# foxBMS_BMS-Extension.net
KiCad netlist of a schematic drawn in EAGLE
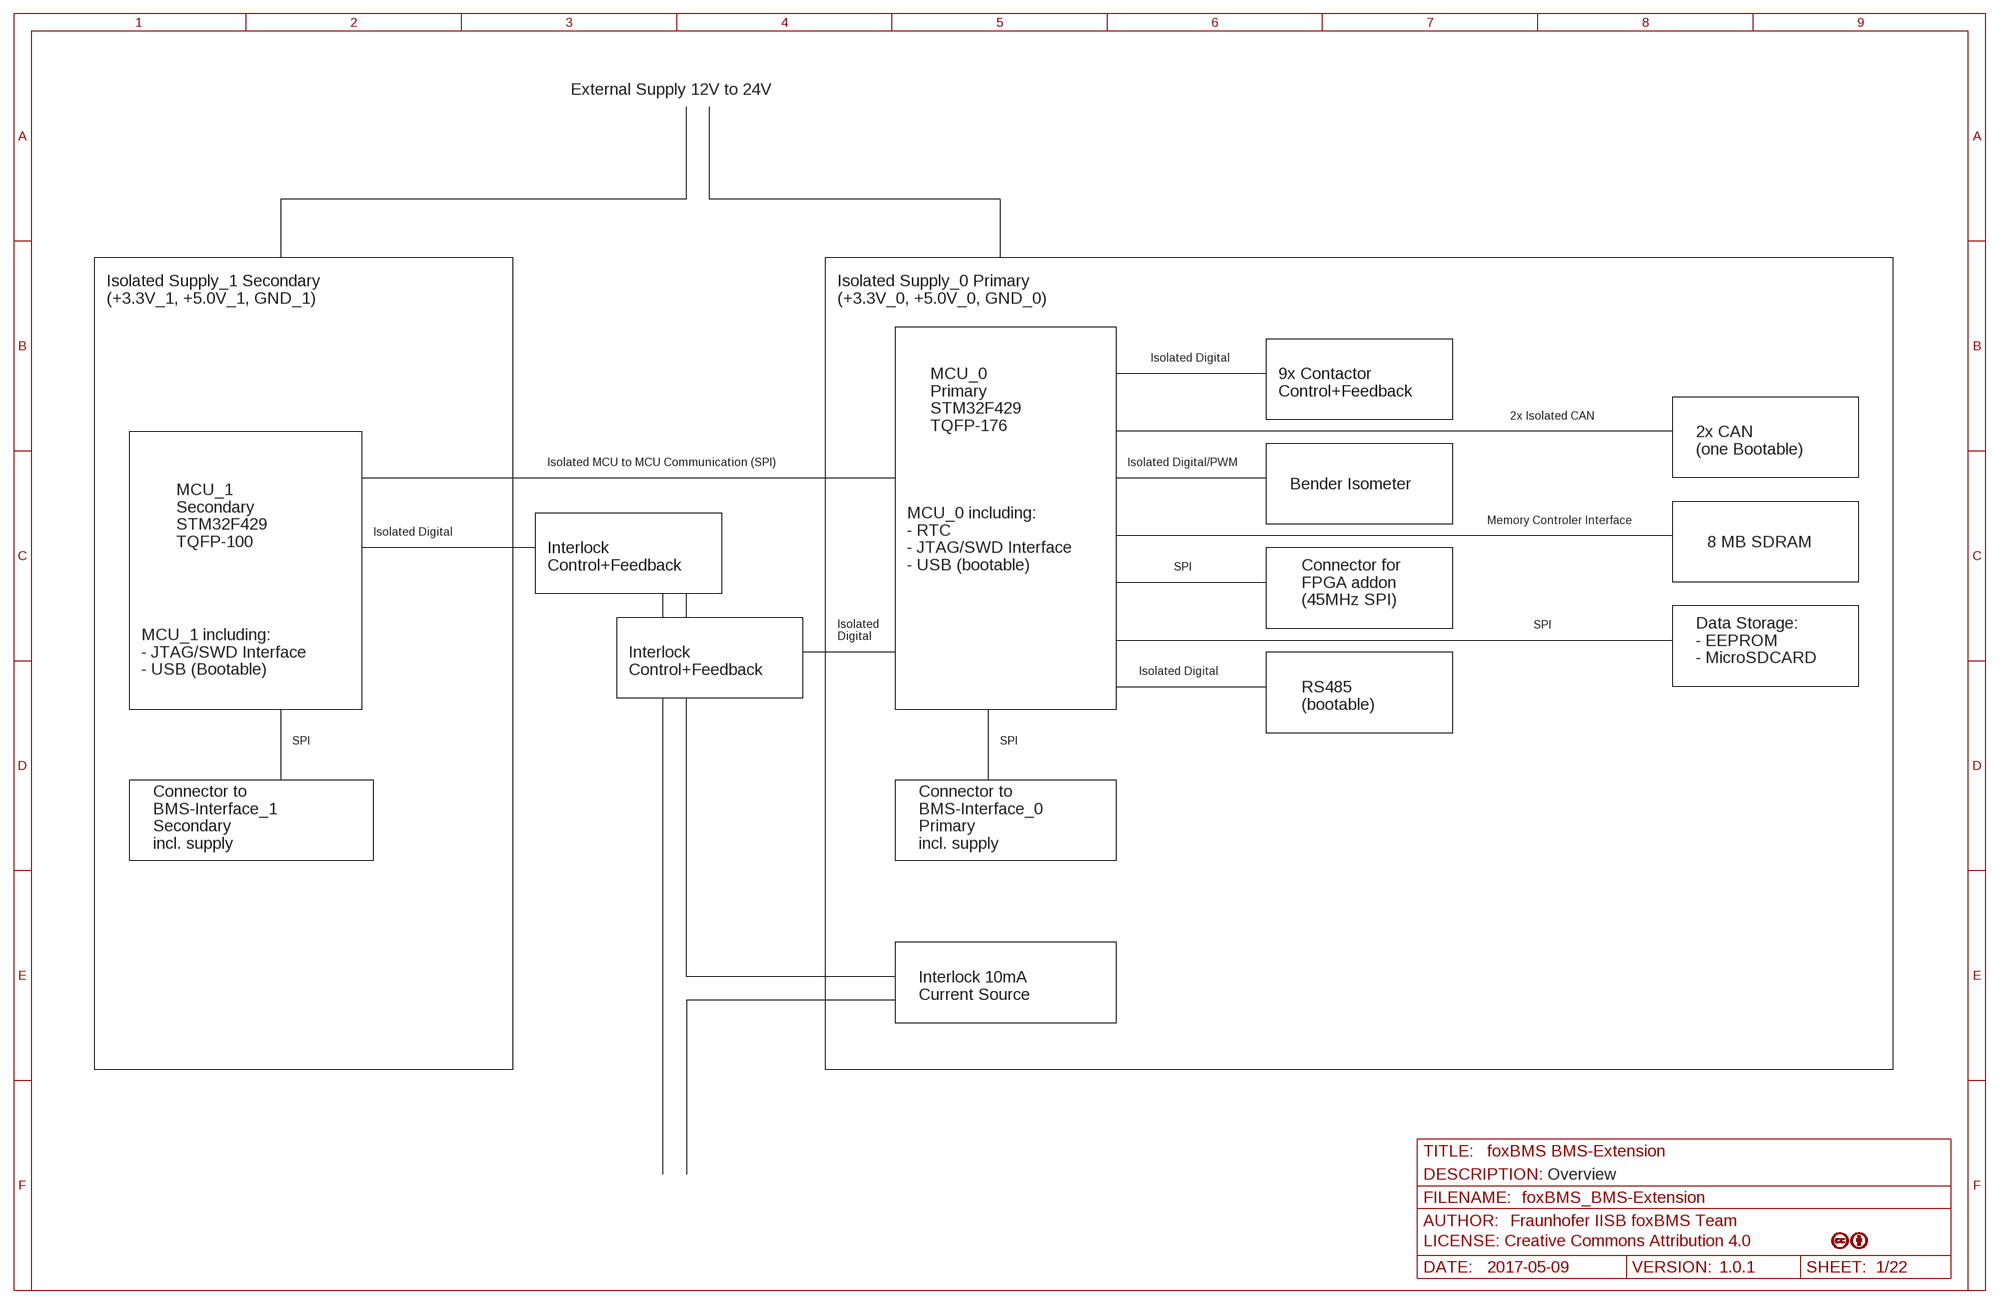
[diagram p0: schematic, sheet 1]
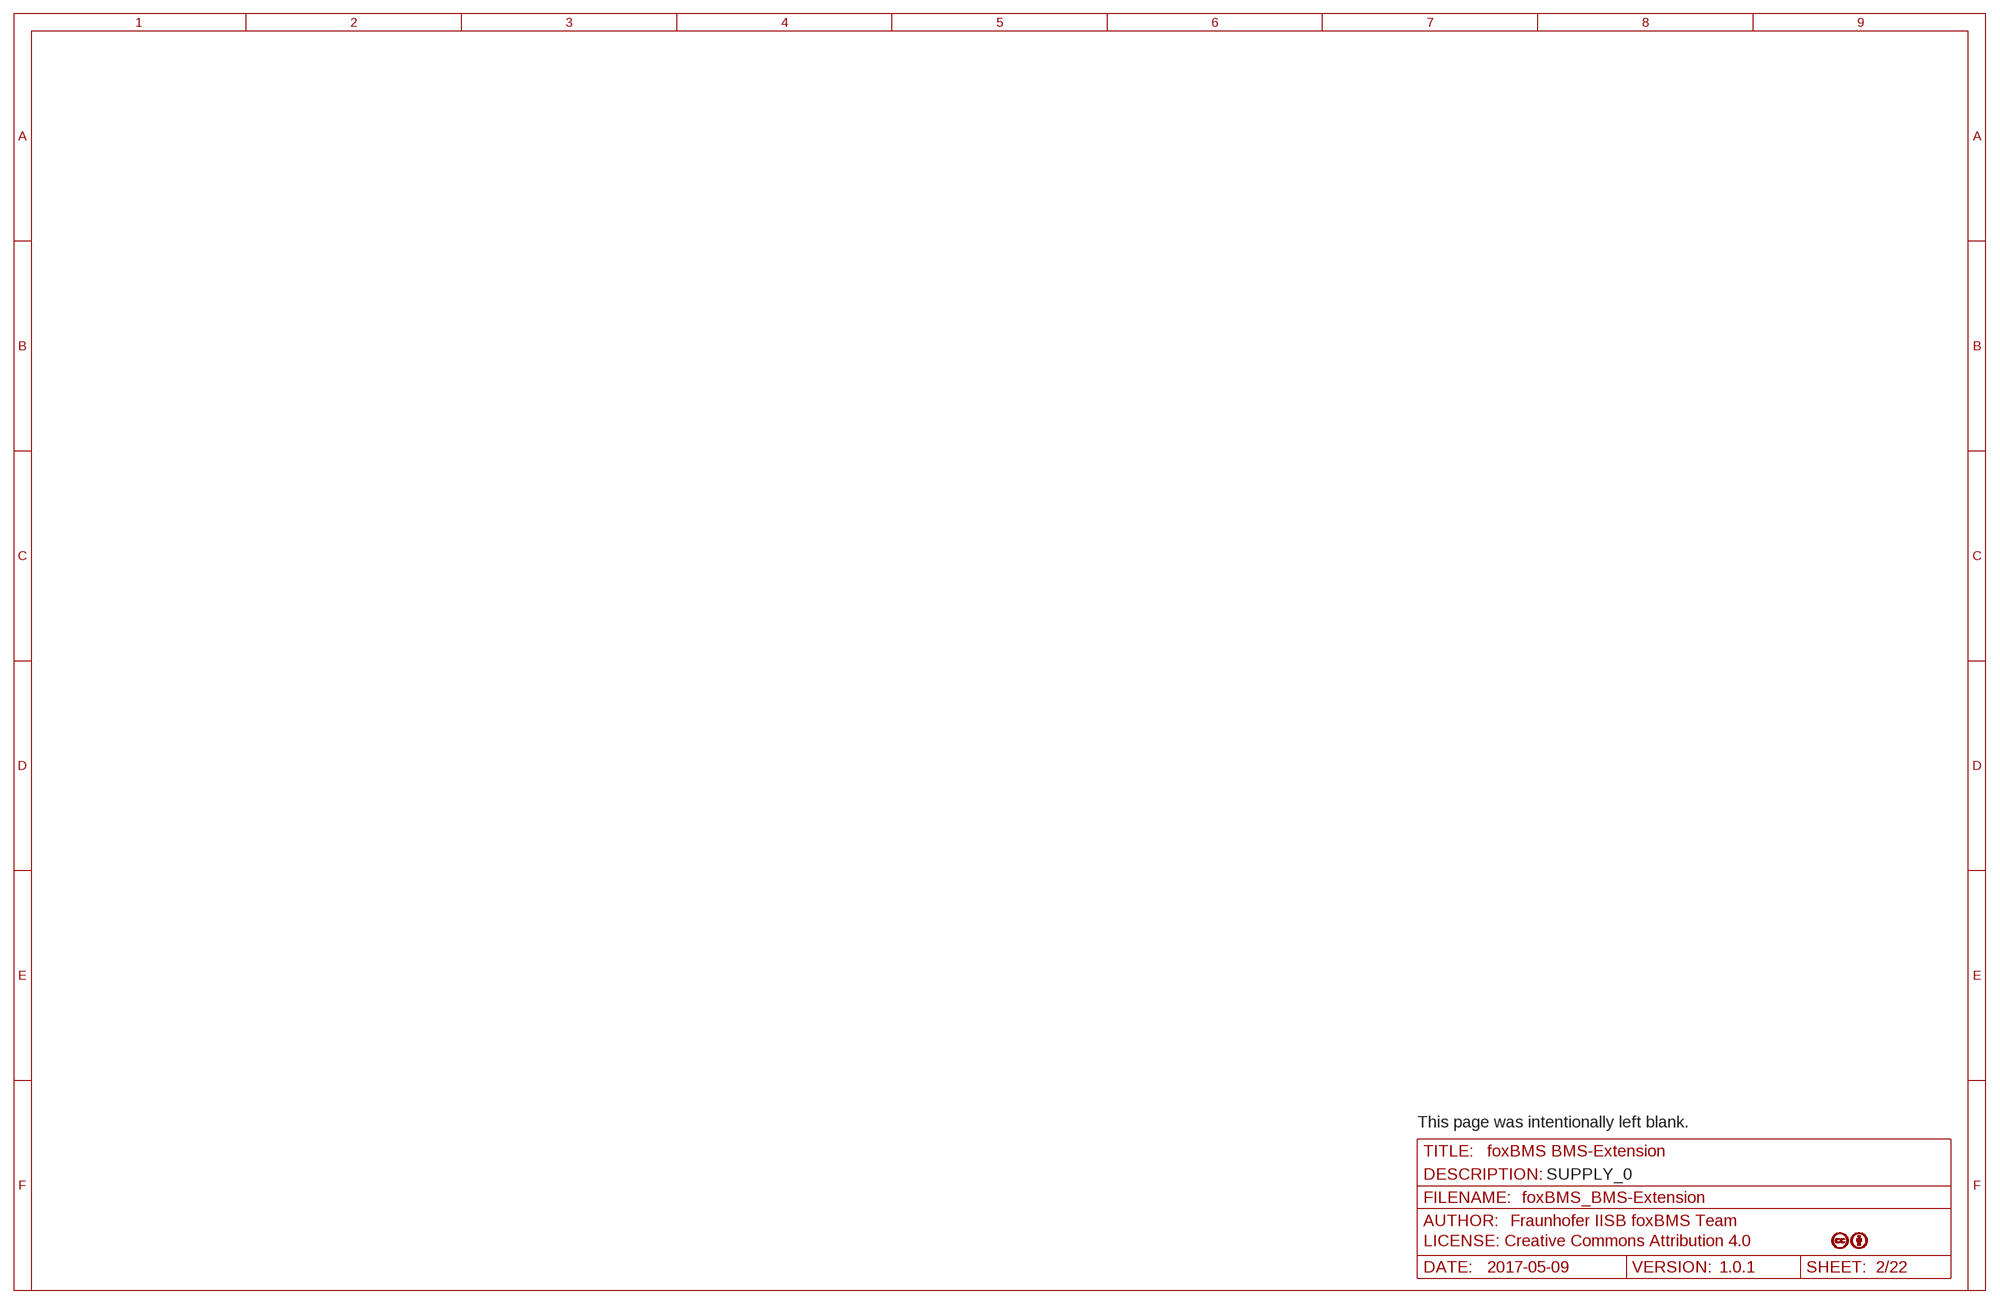
[diagram p1: schematic, sheet 2]
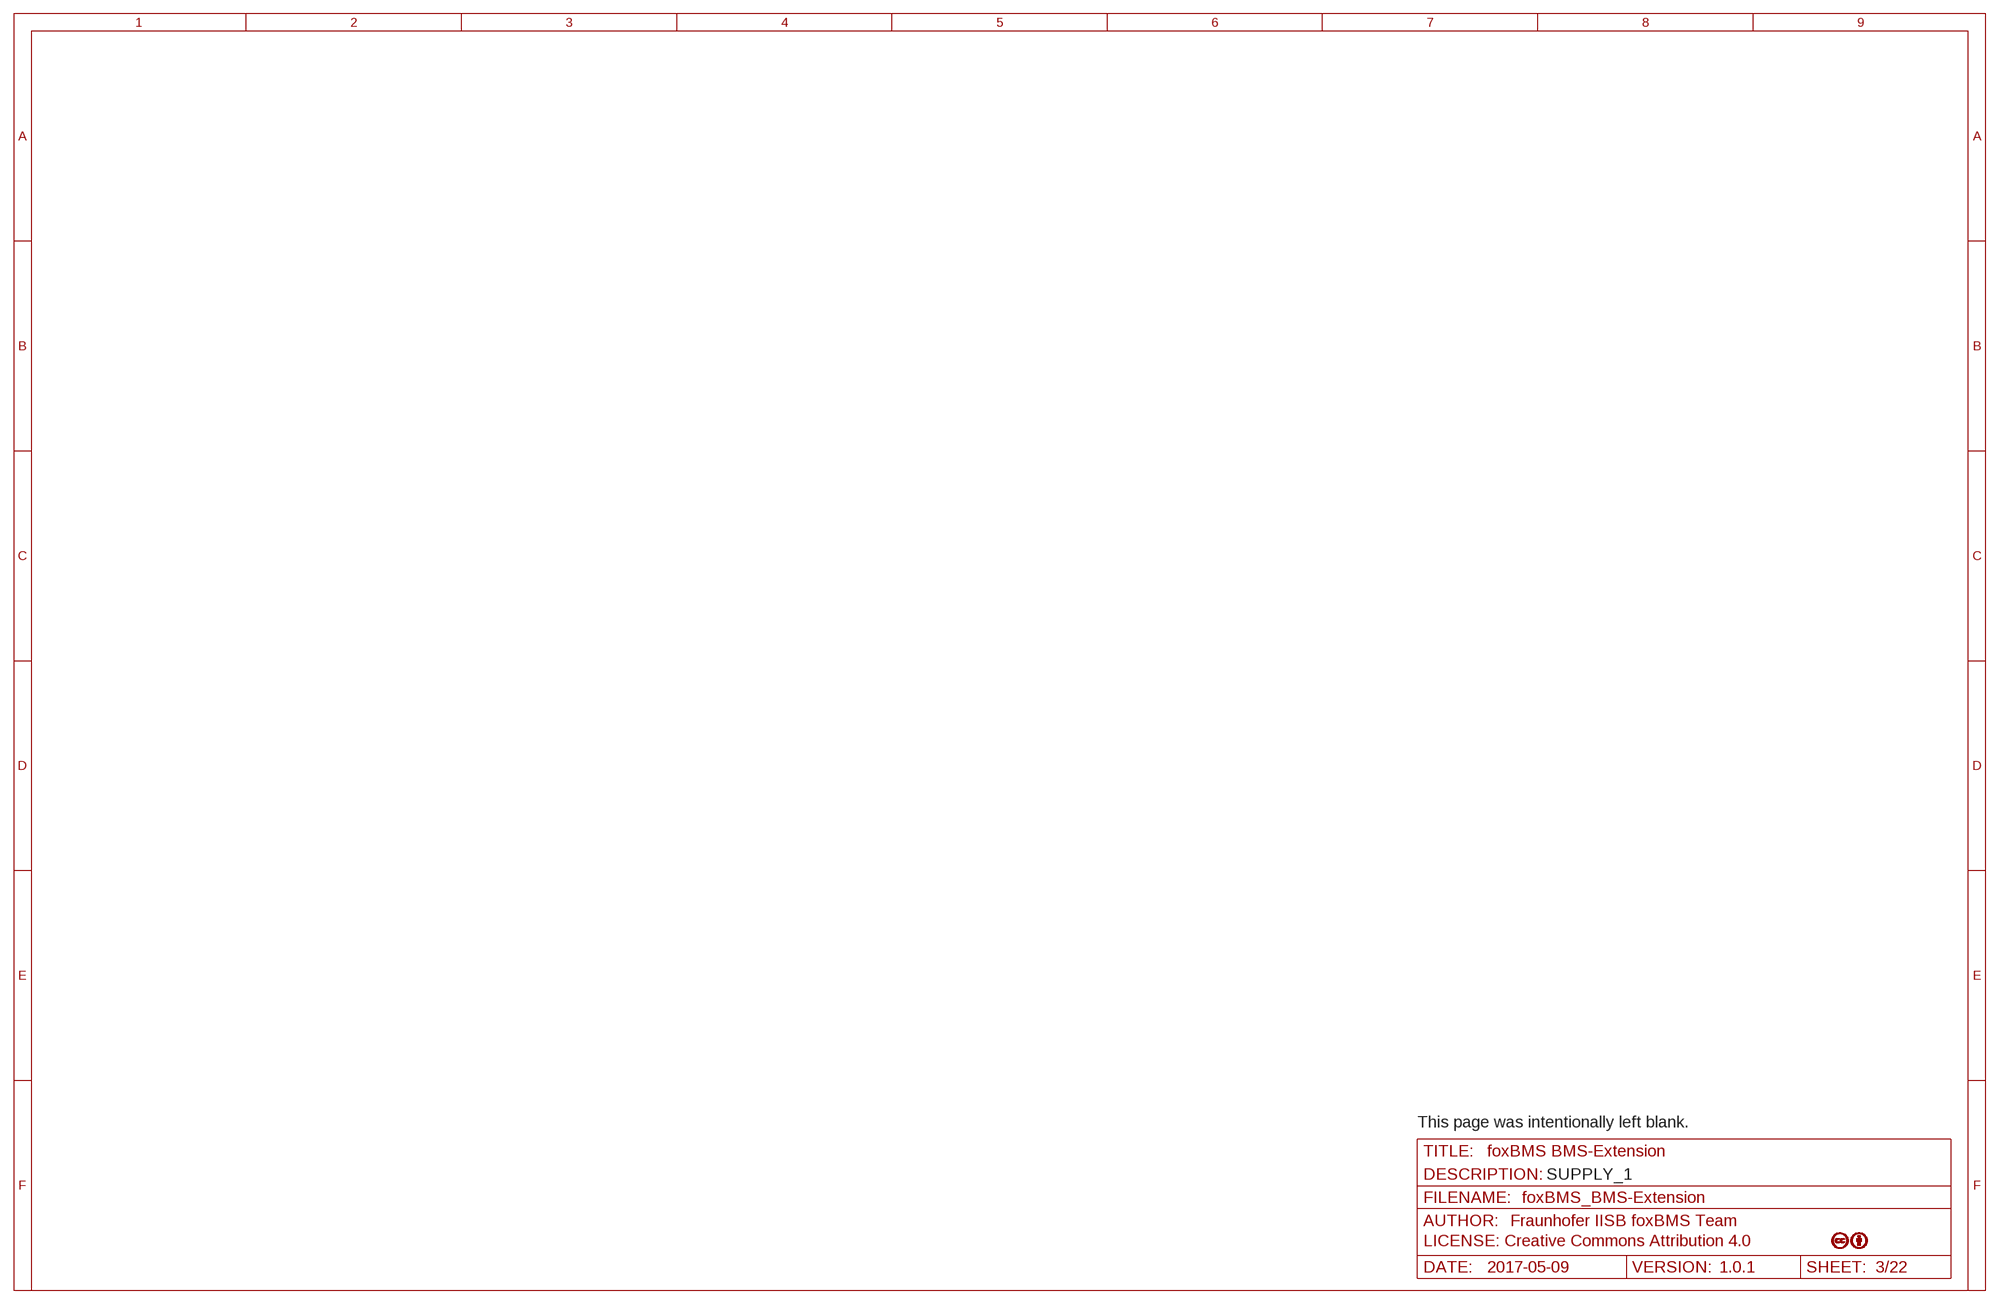
[diagram p2: schematic, sheet 3]
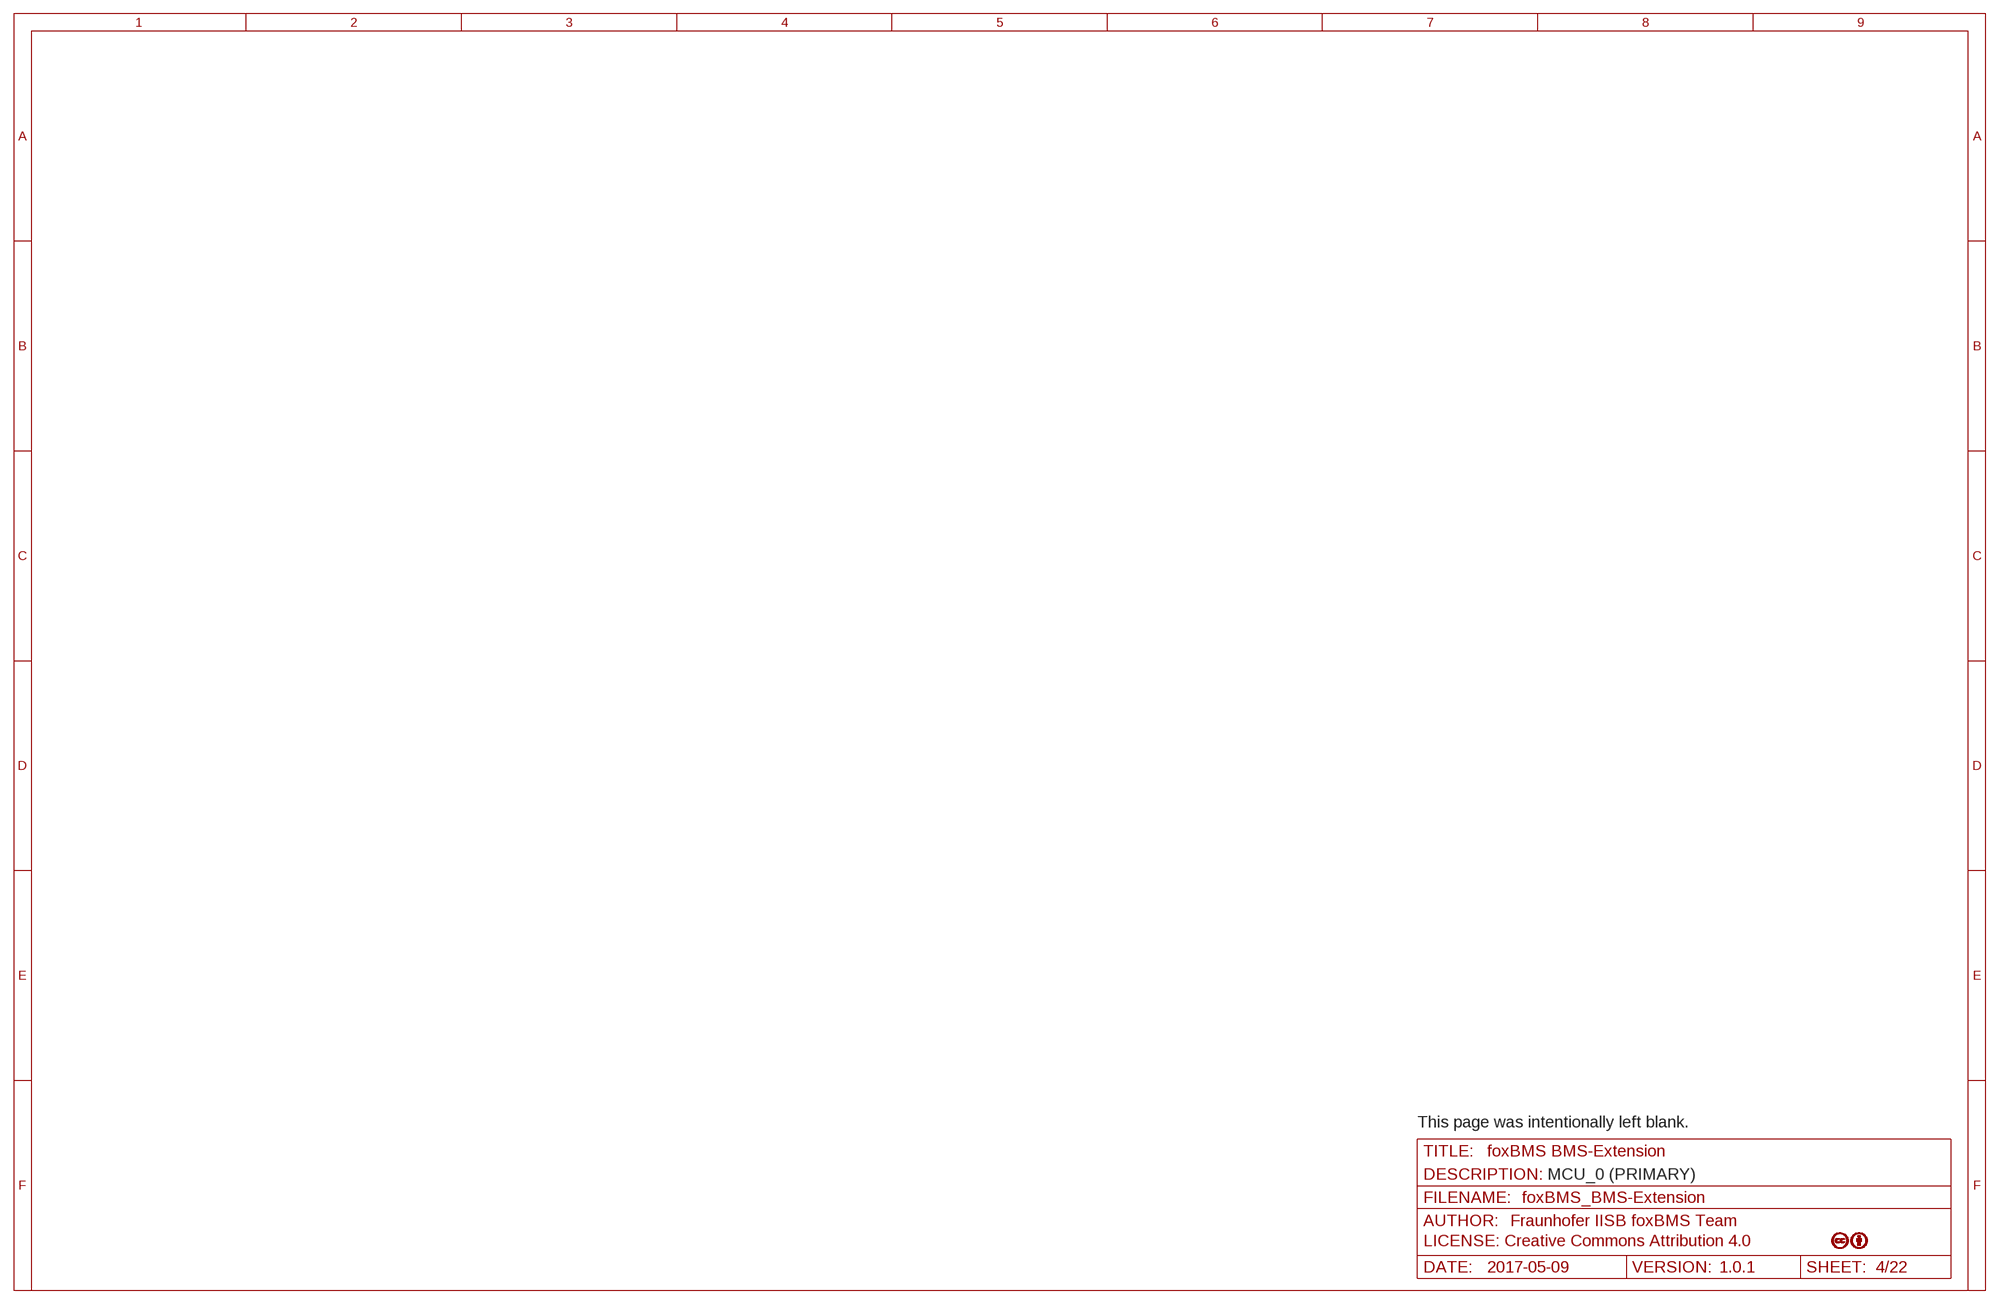
[diagram p3: schematic, sheet 4]
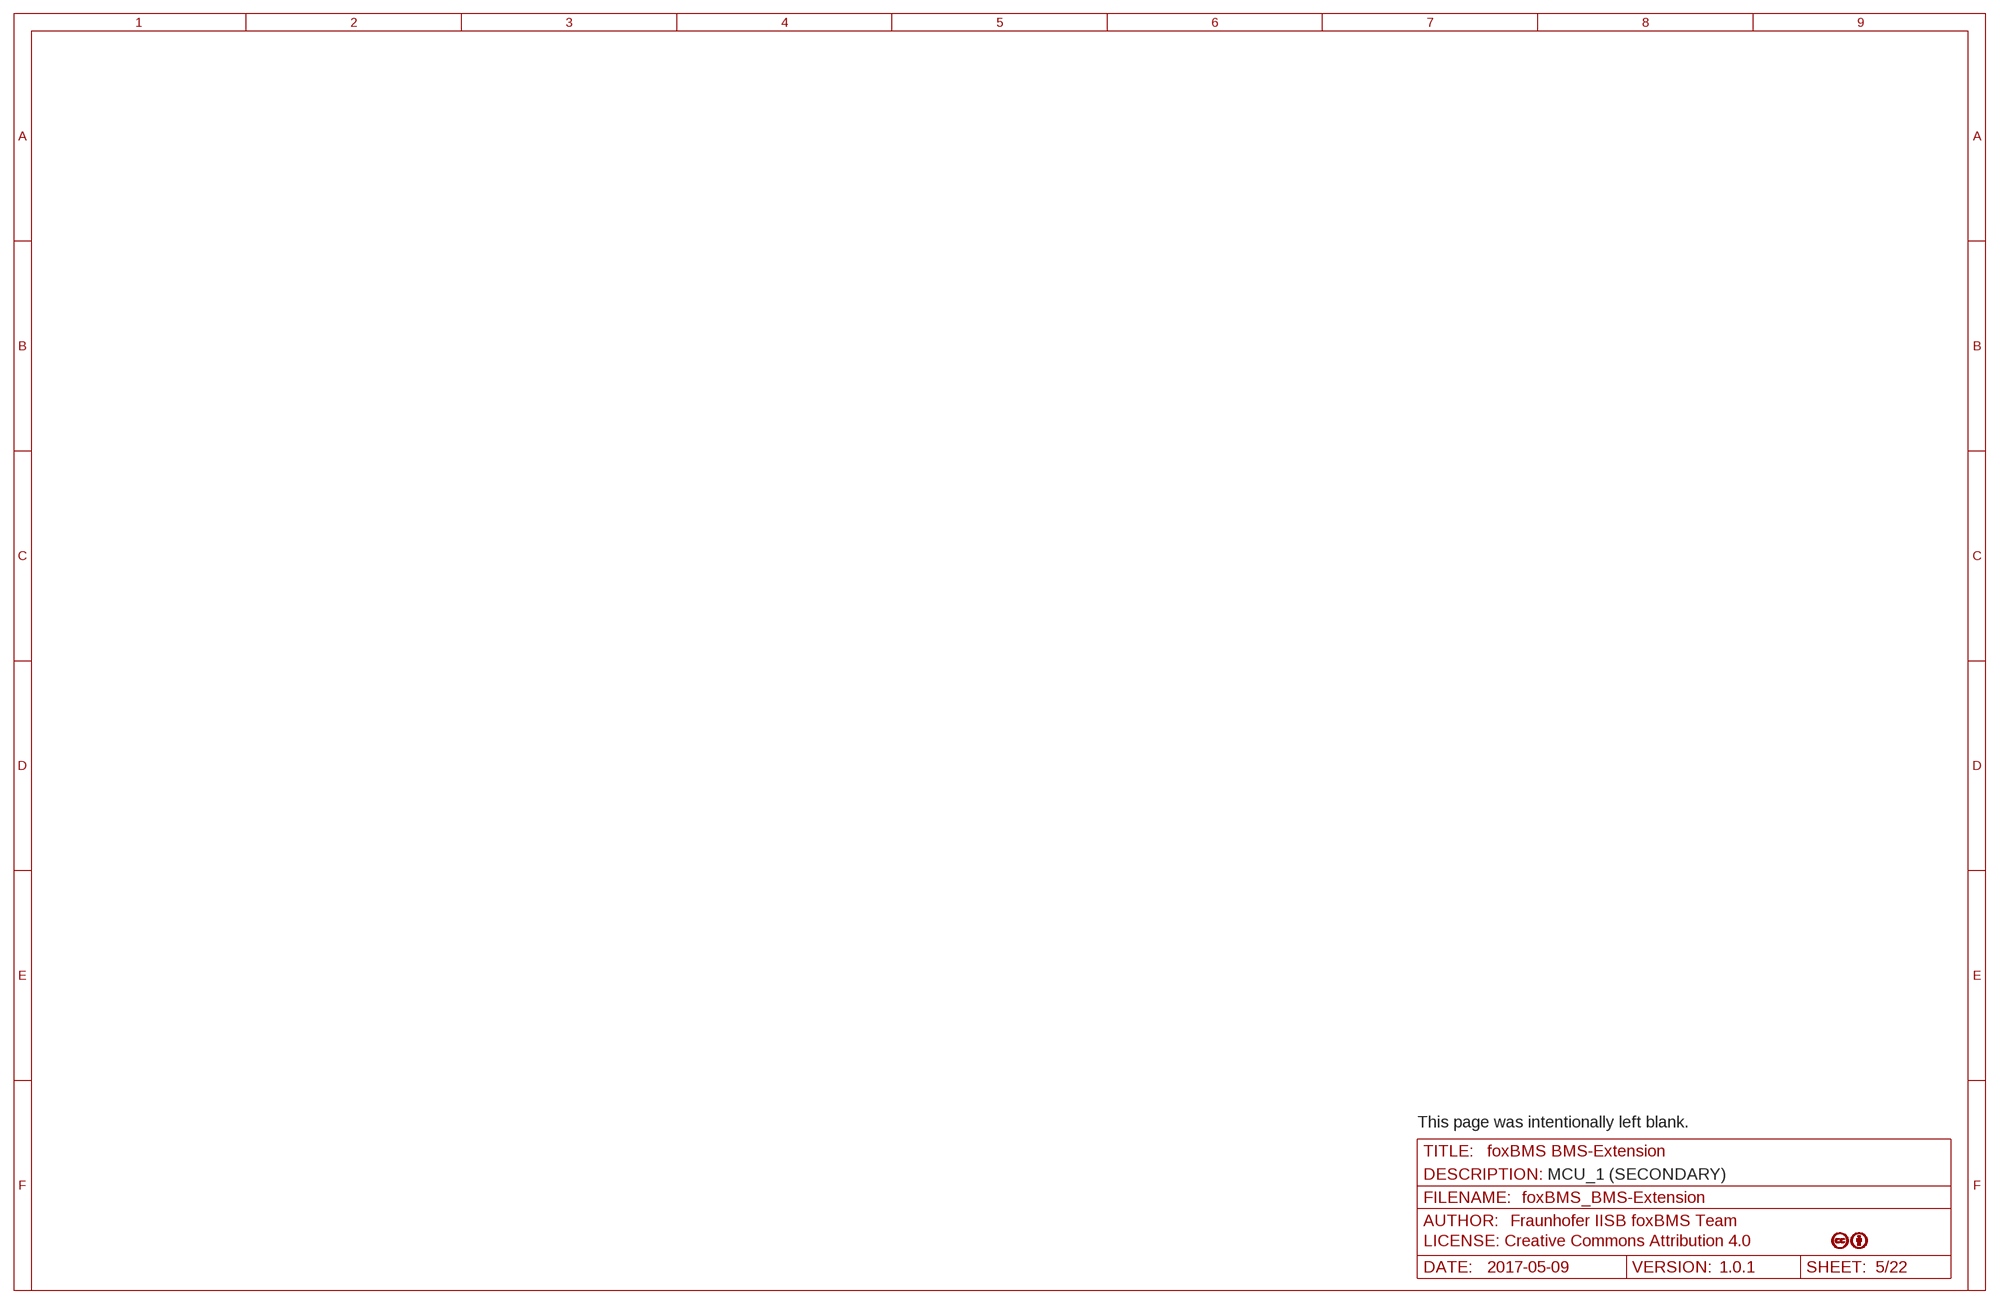
[diagram p4: schematic, sheet 5]
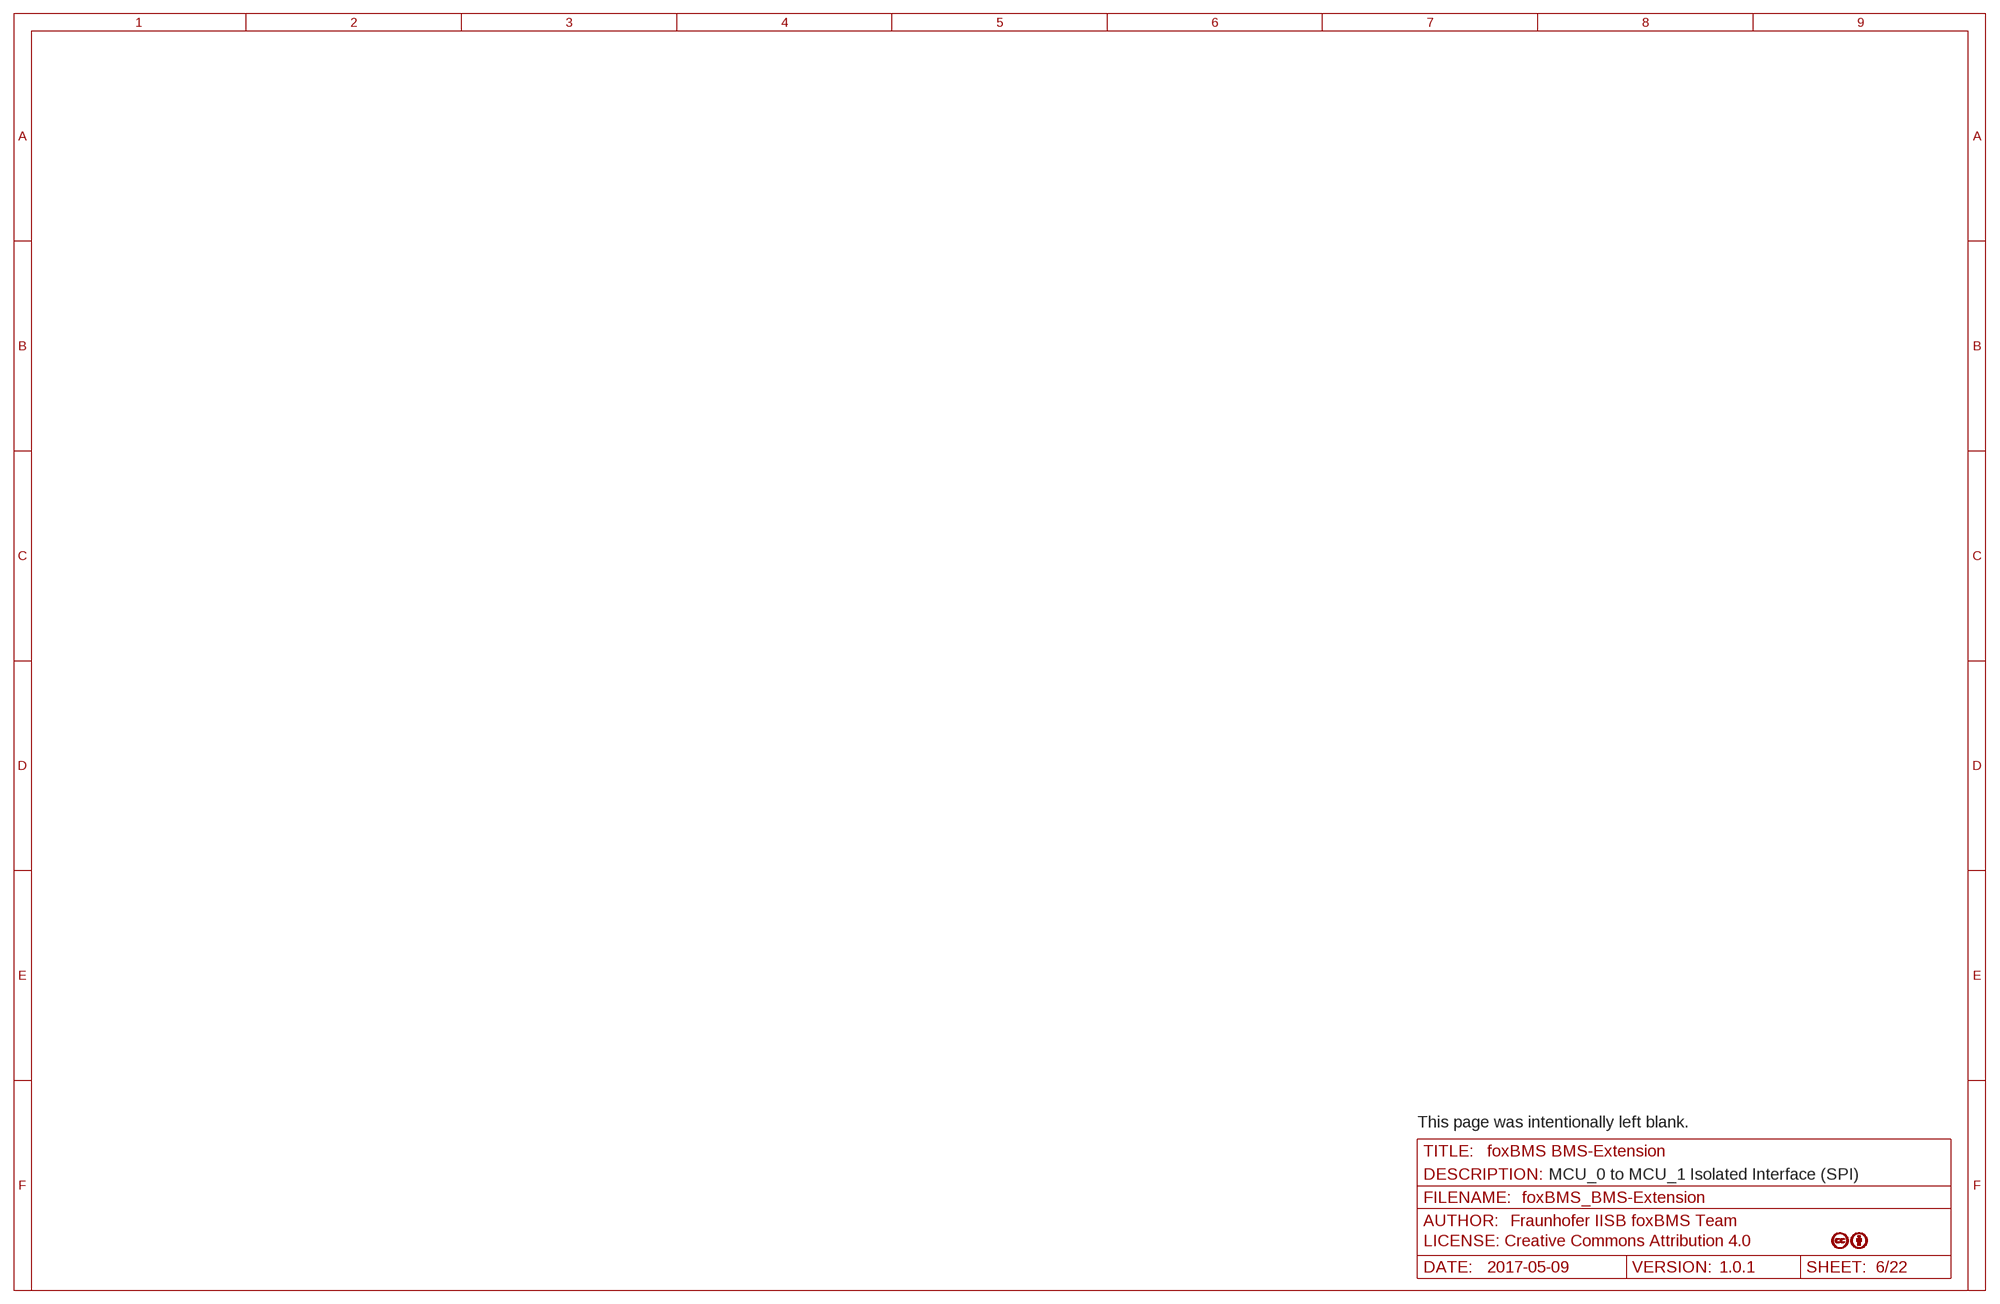
[diagram p5: schematic, sheet 6]
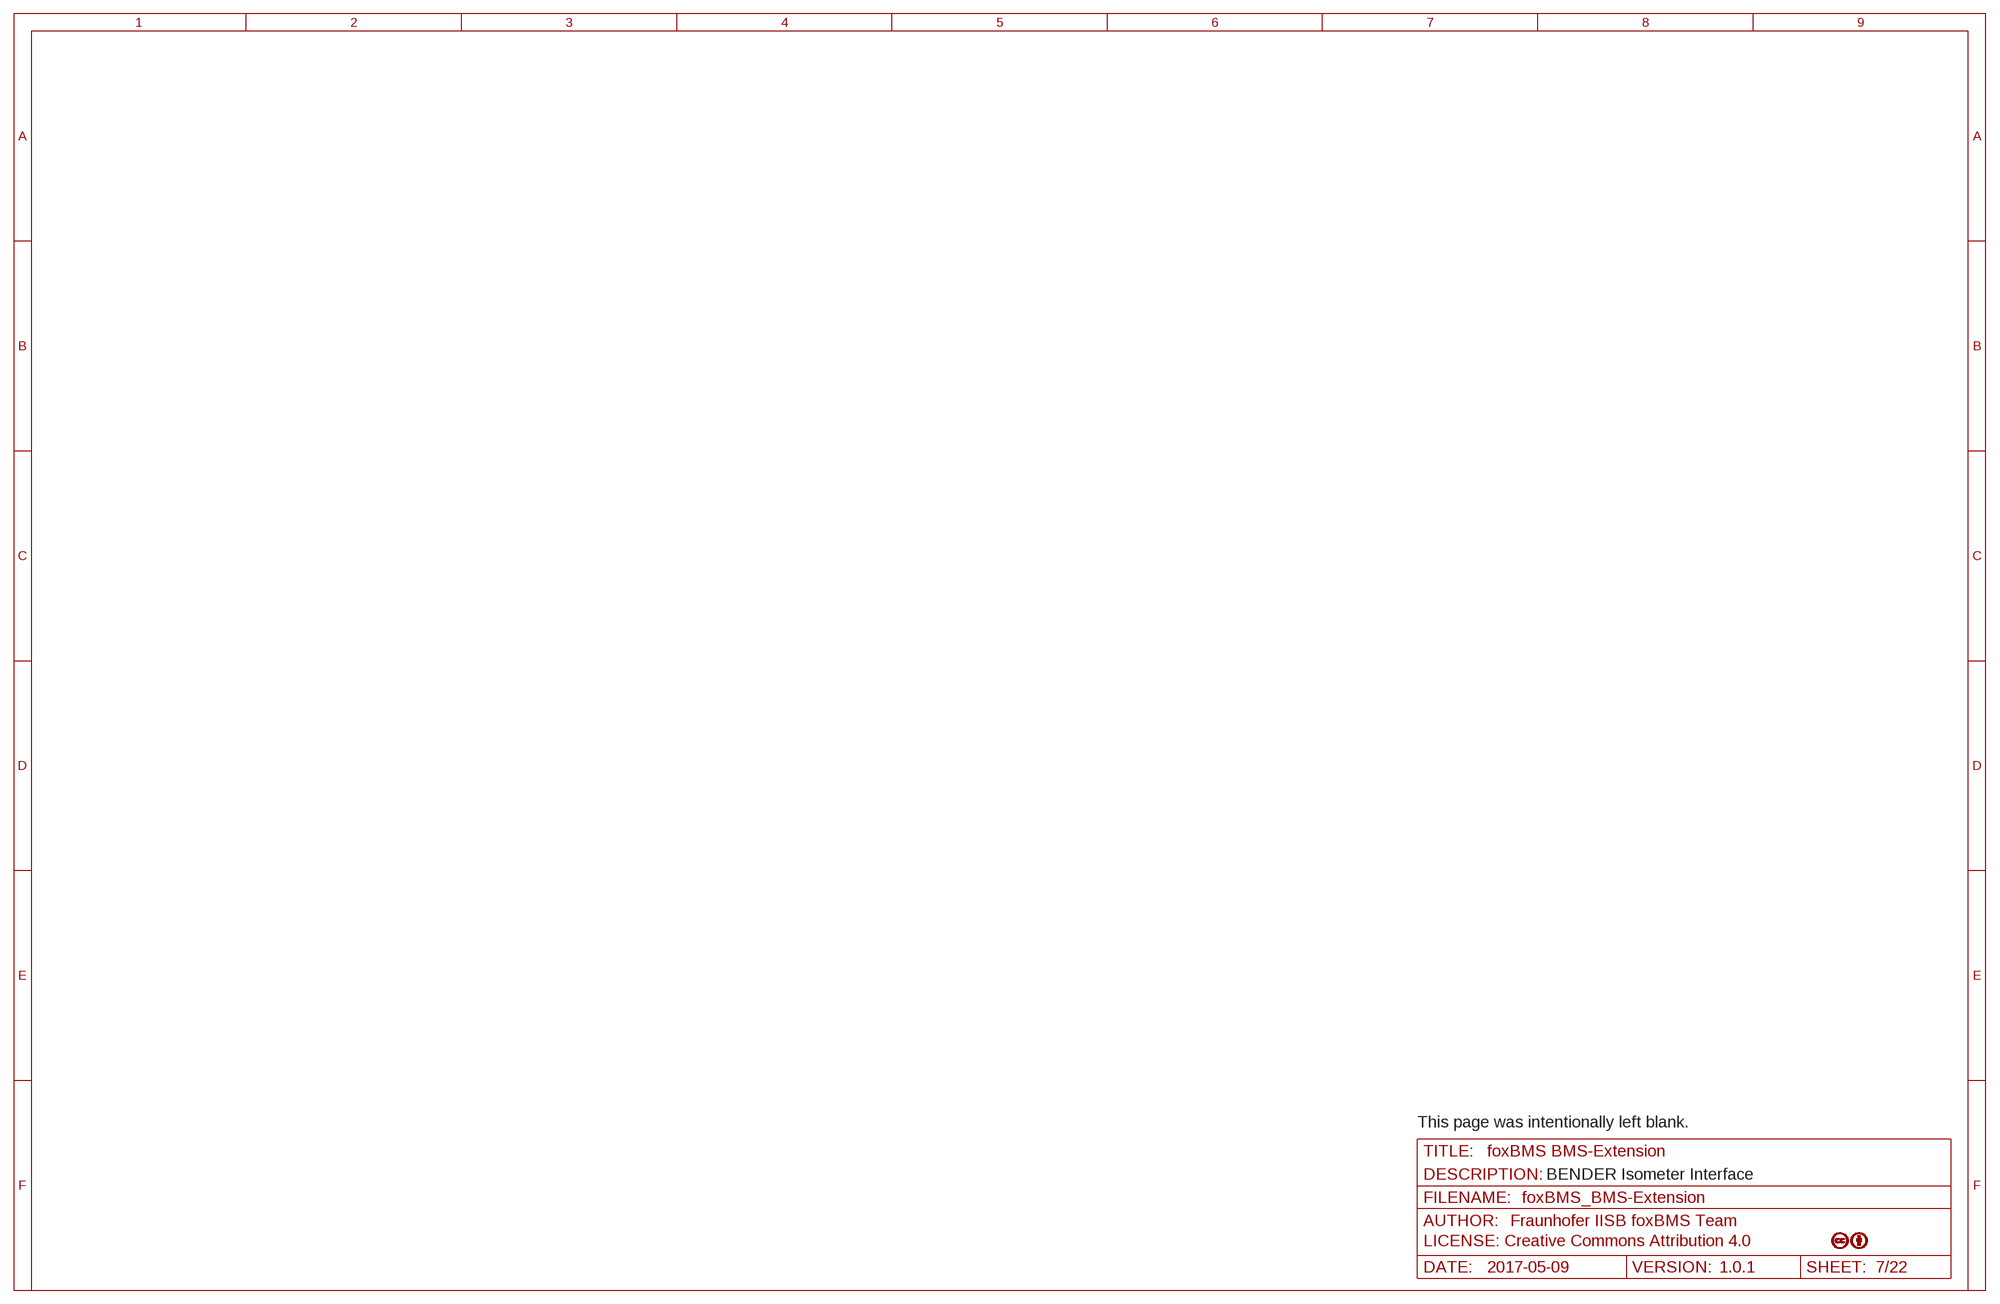
[diagram p6: schematic, sheet 7]
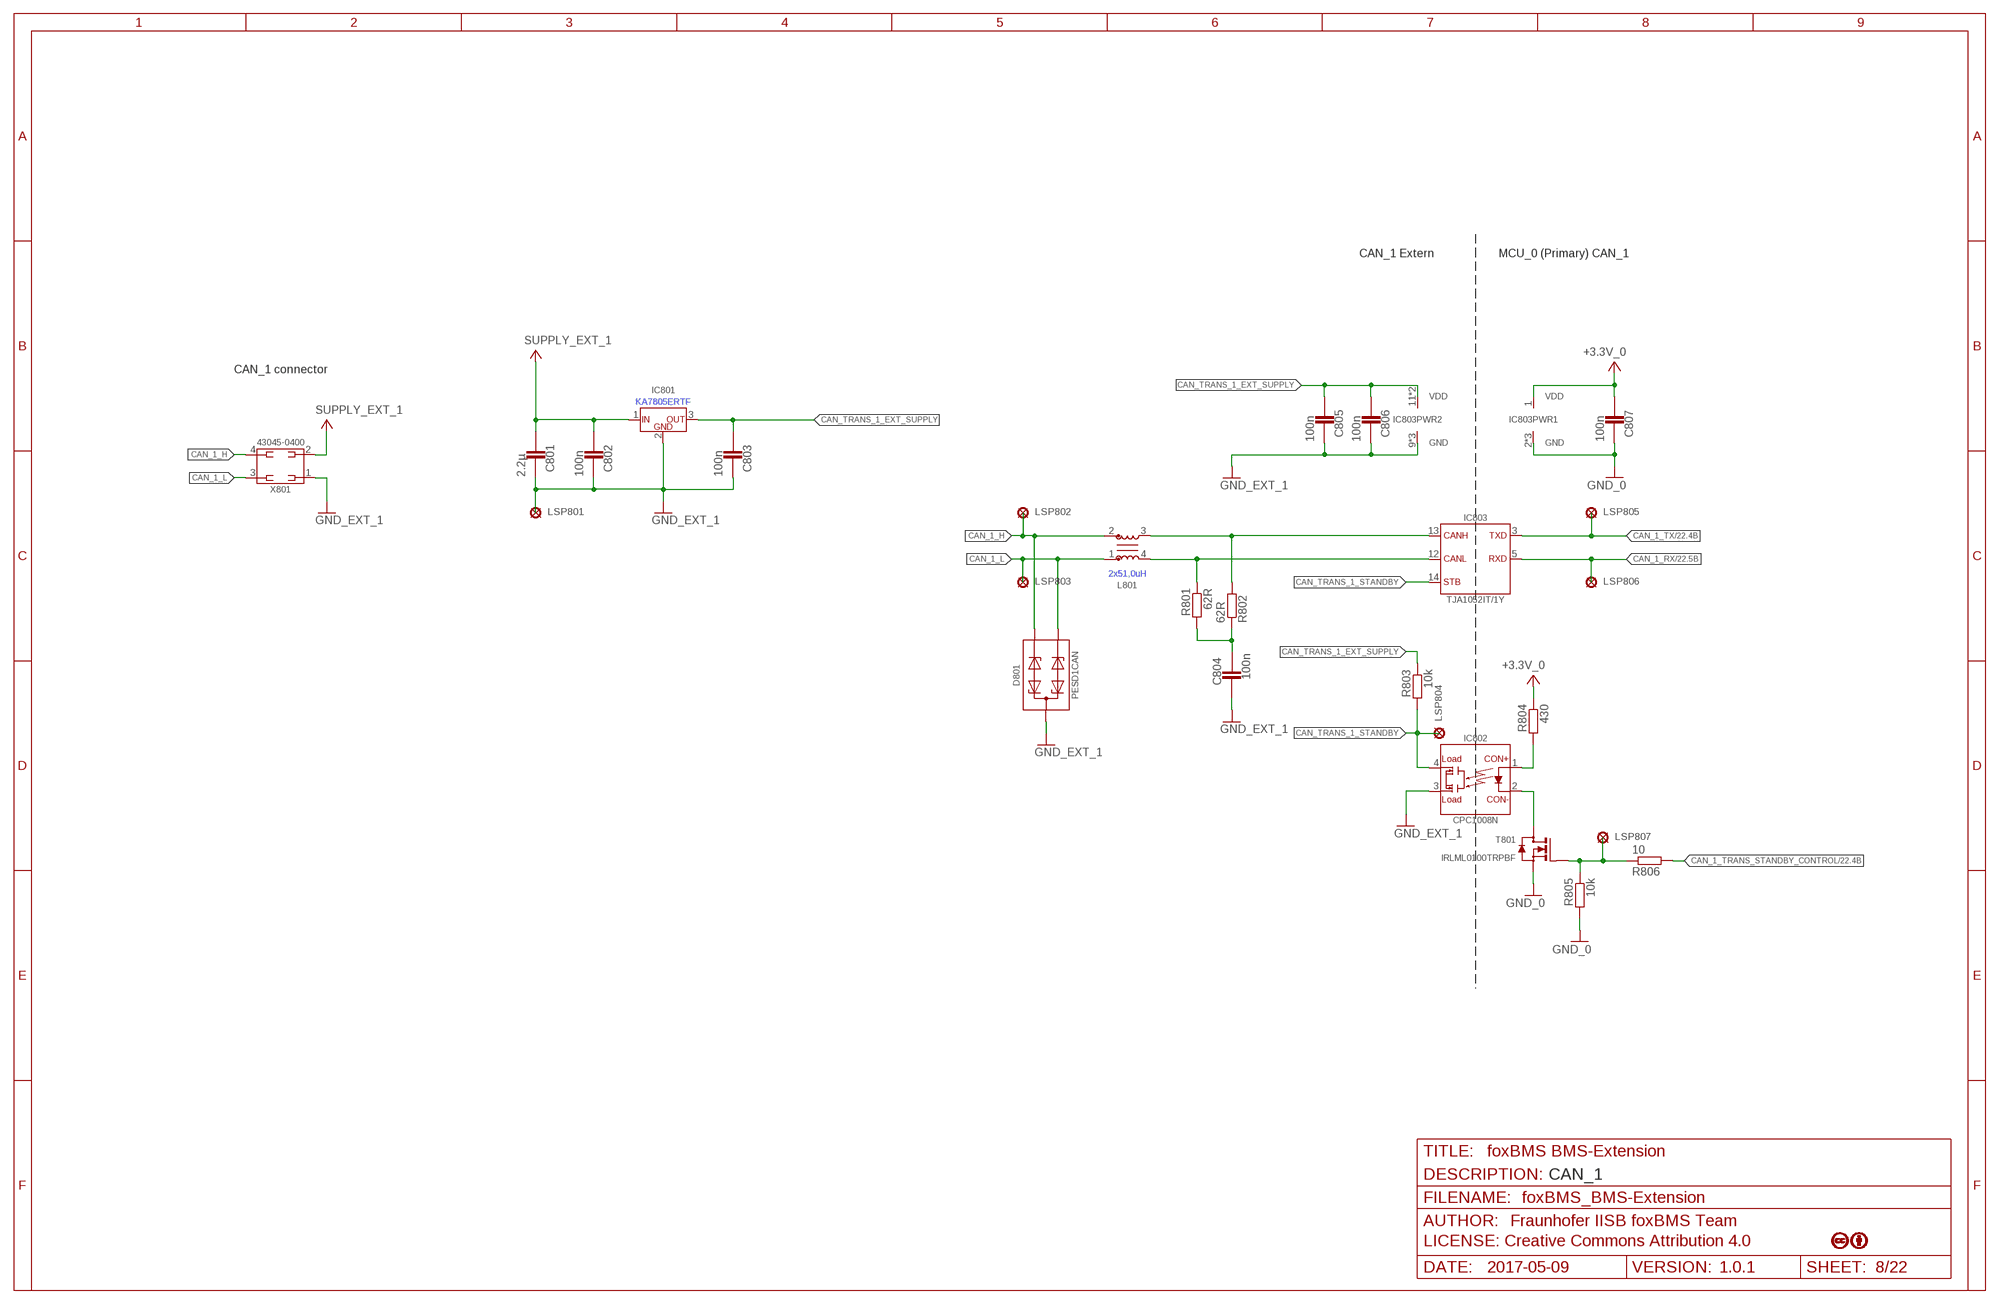
[diagram p7: schematic, sheet 8]
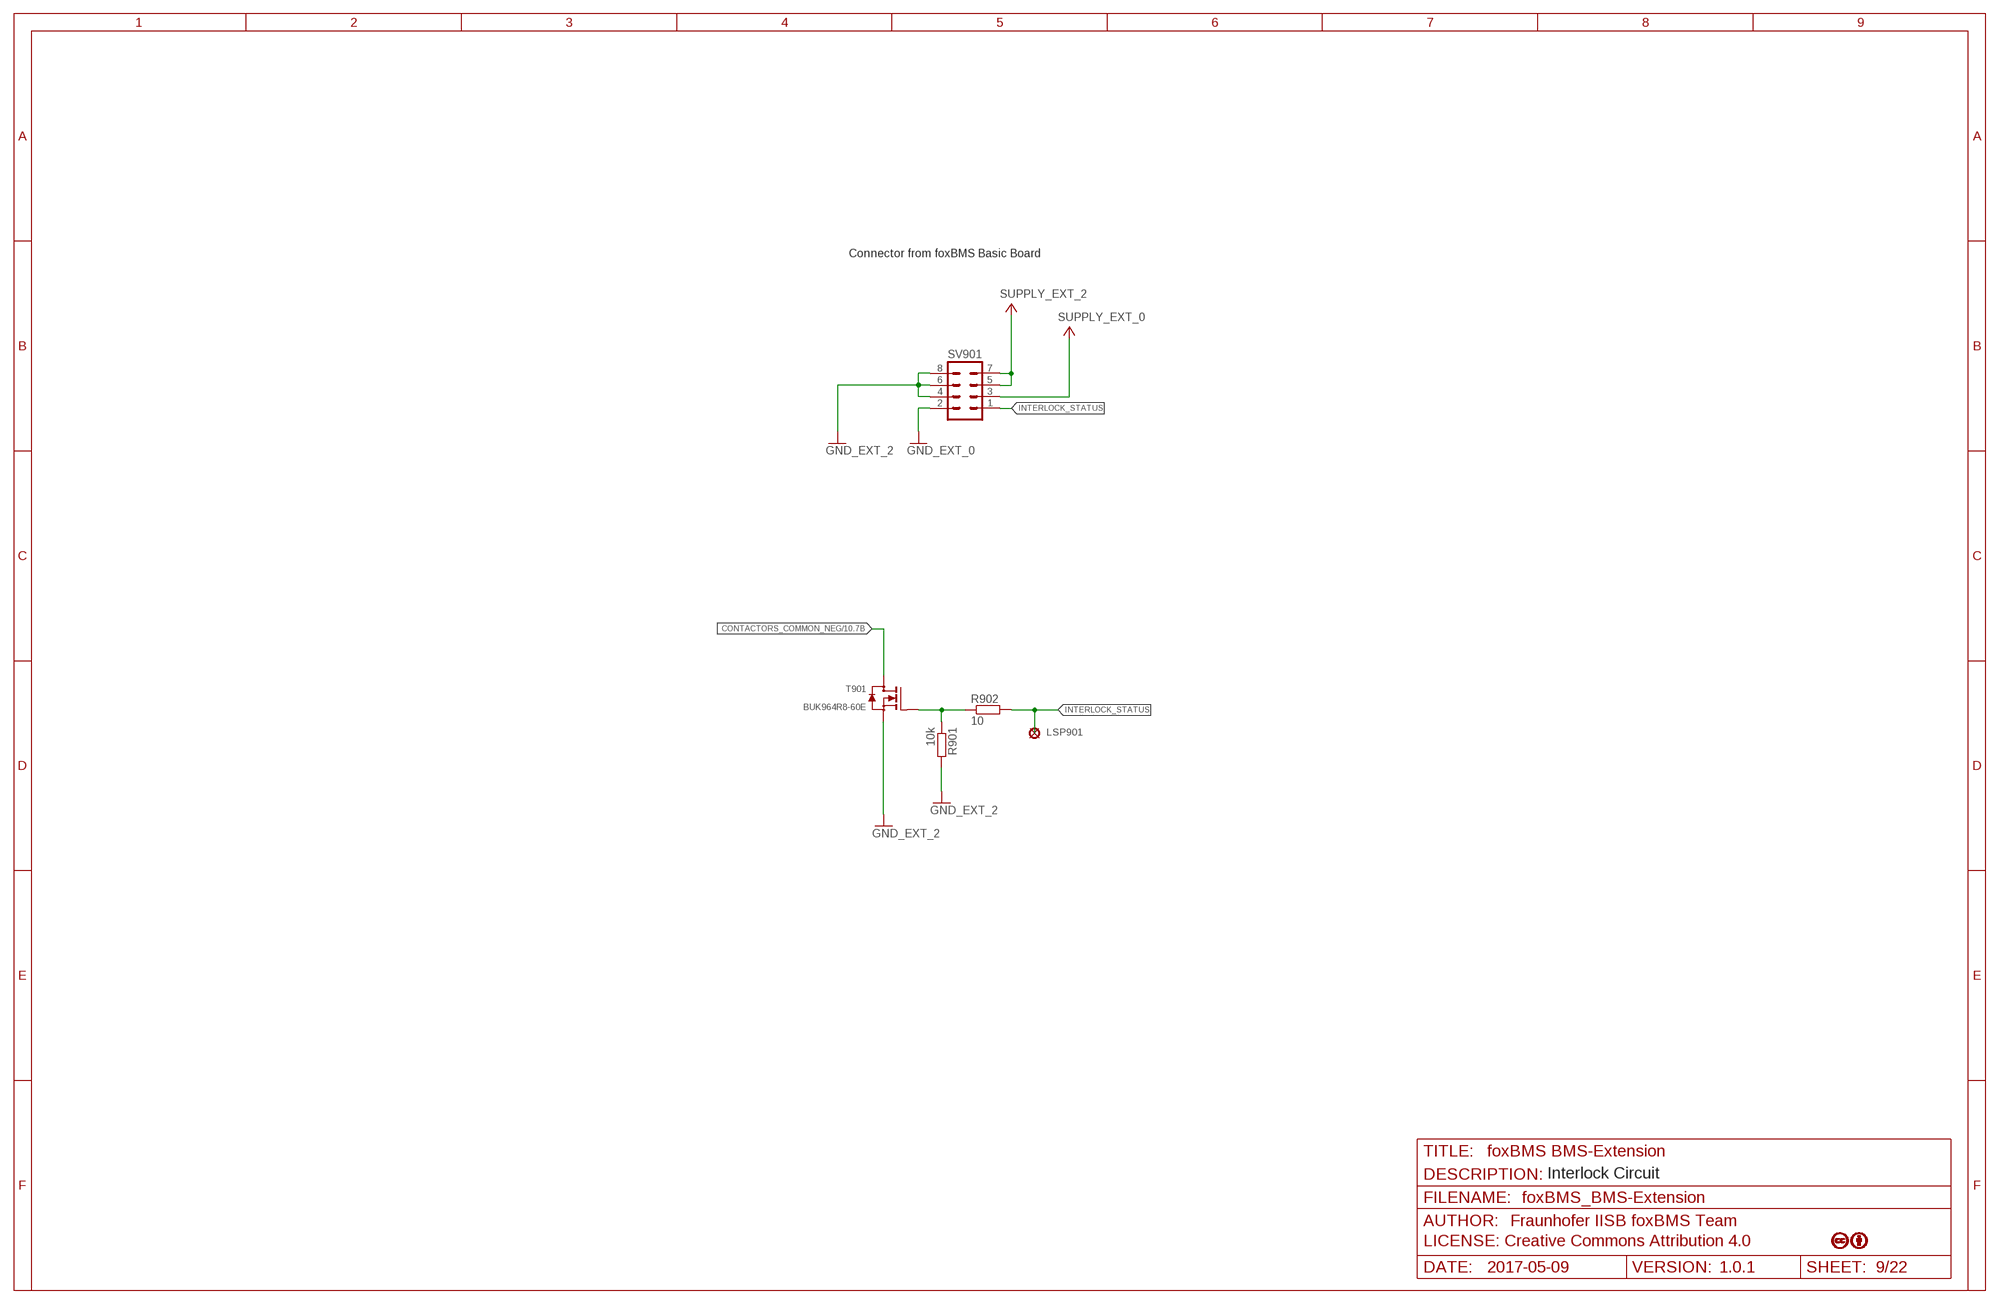
[diagram p8: schematic, sheet 9]
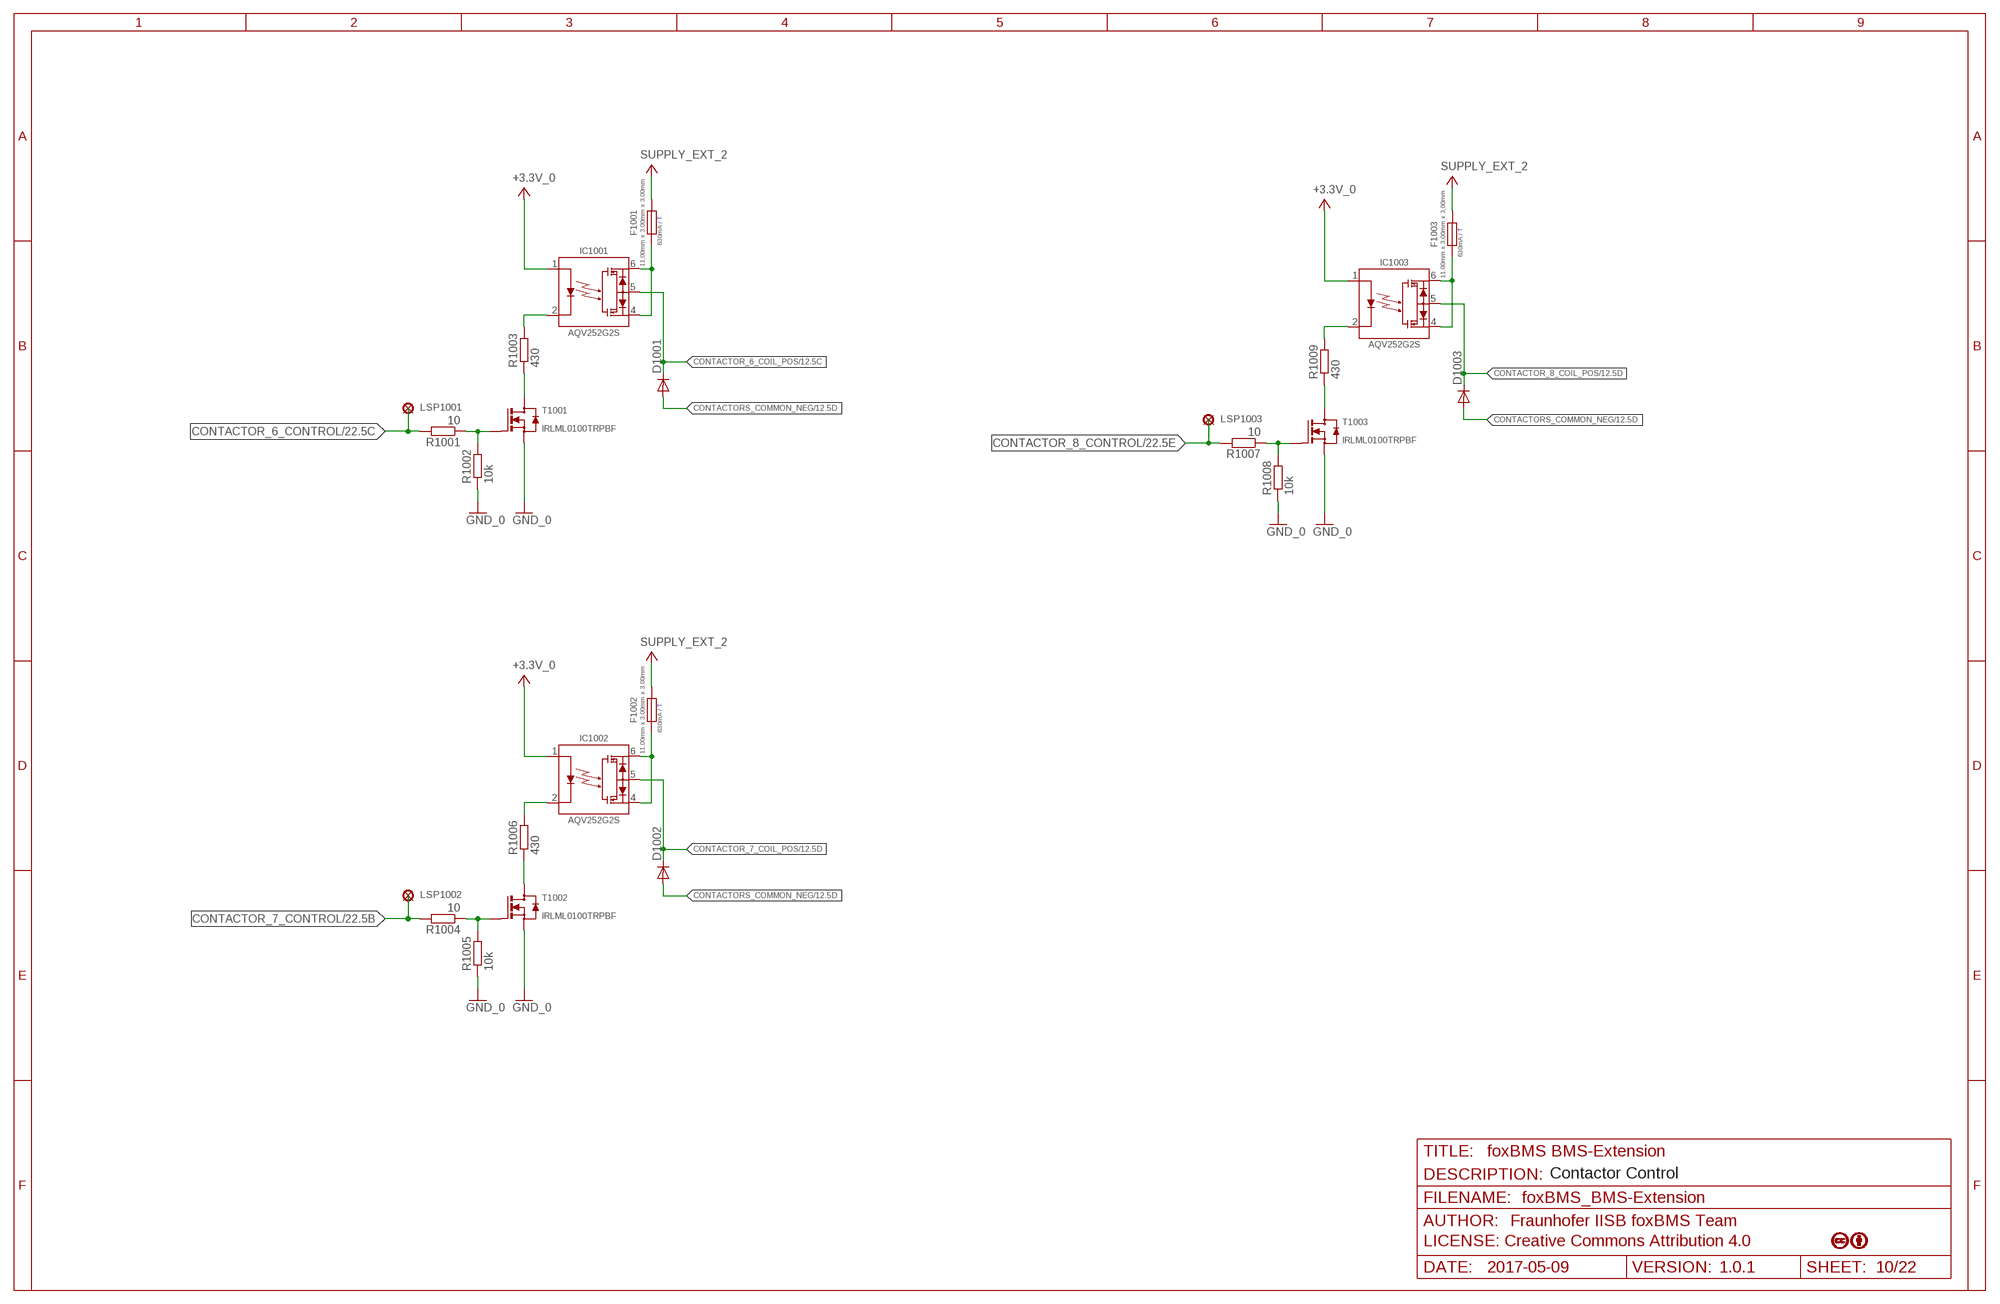
[diagram p9: schematic, sheet 10]
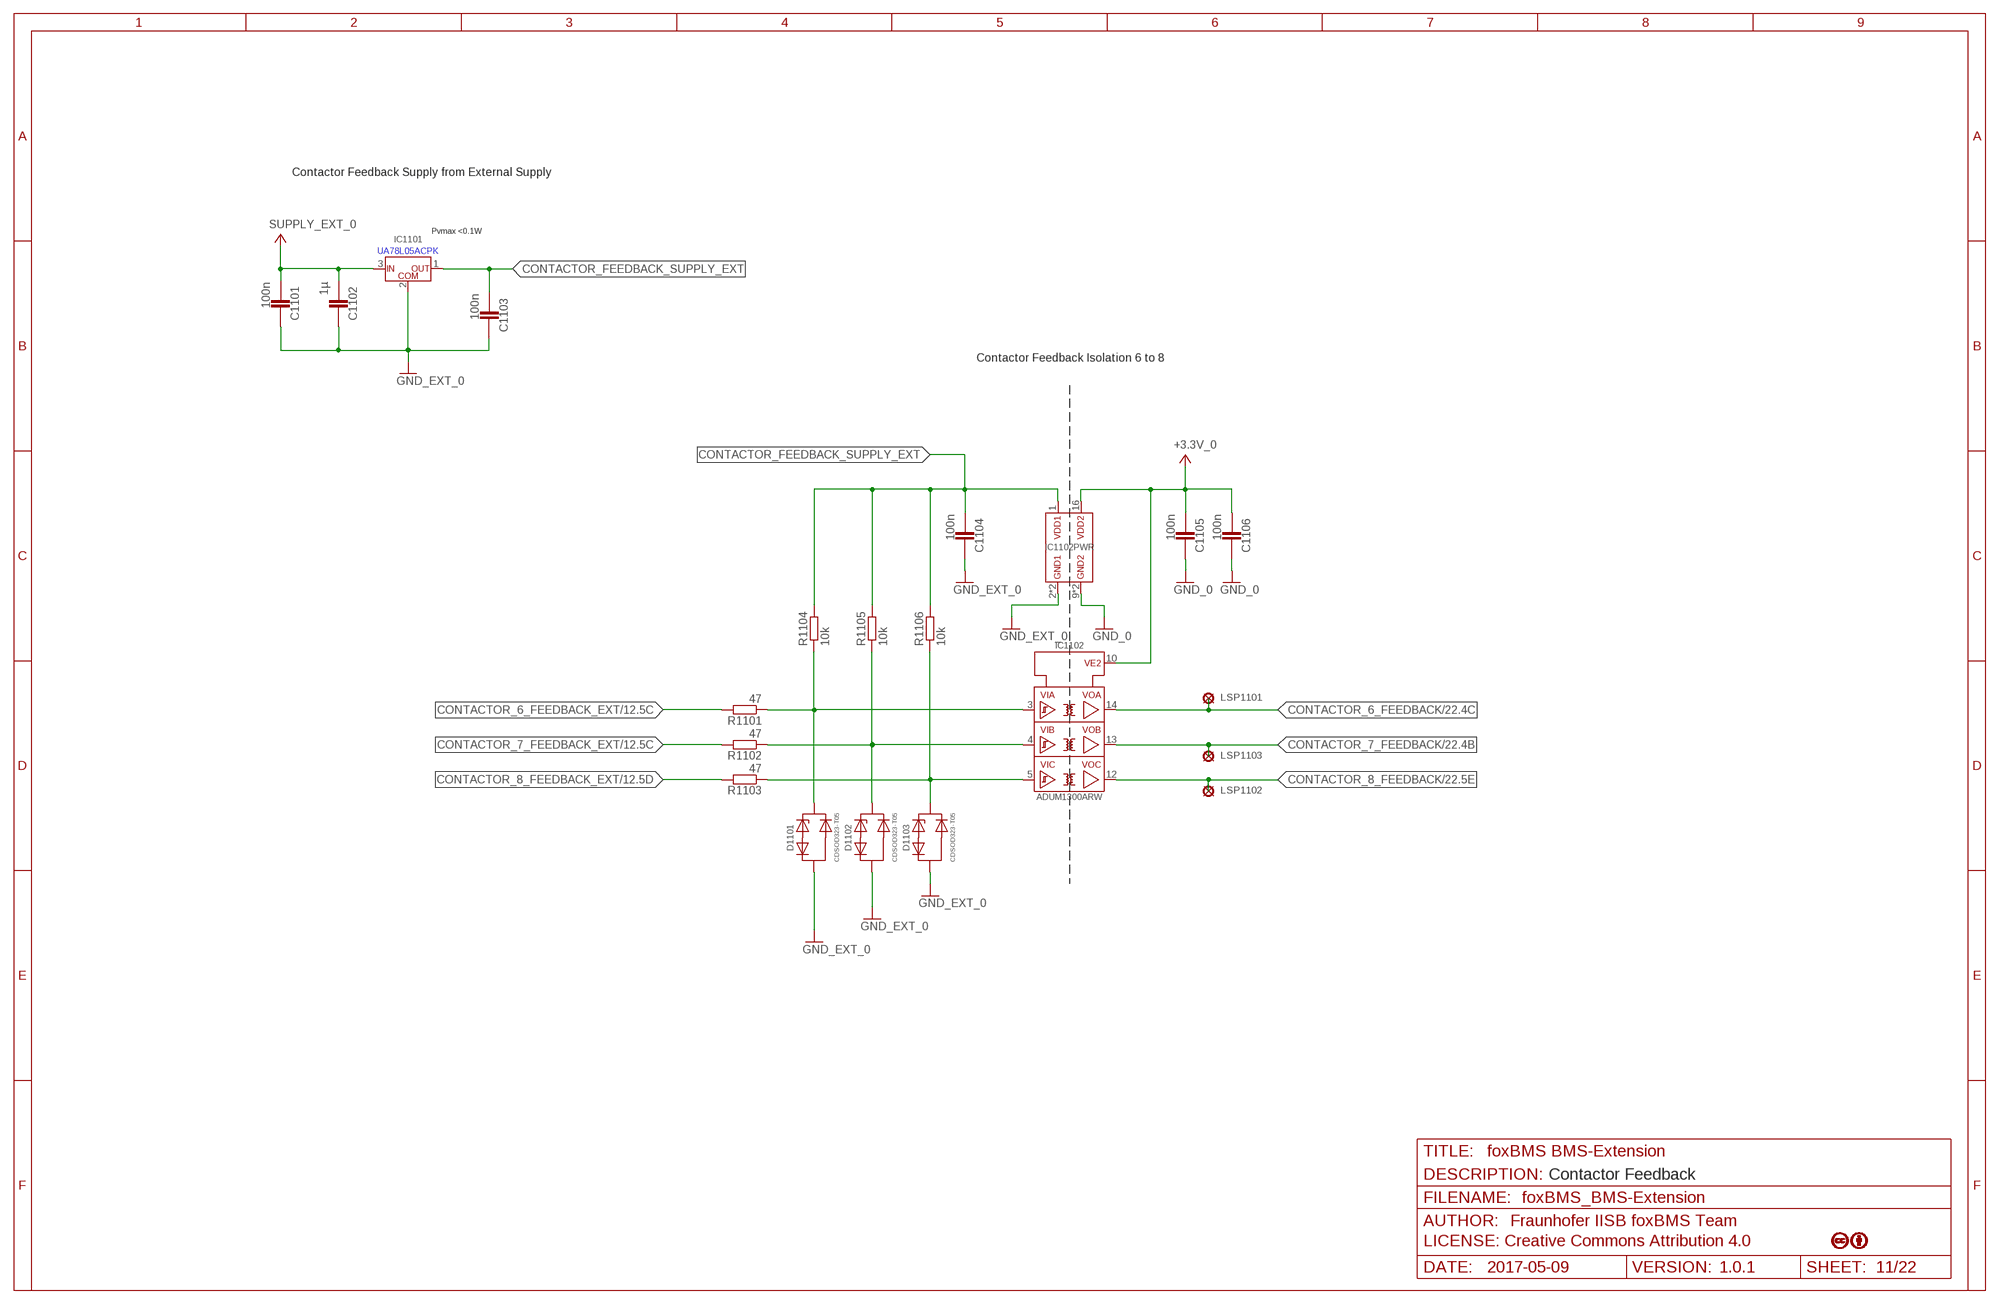
[diagram p10: schematic, sheet 11]
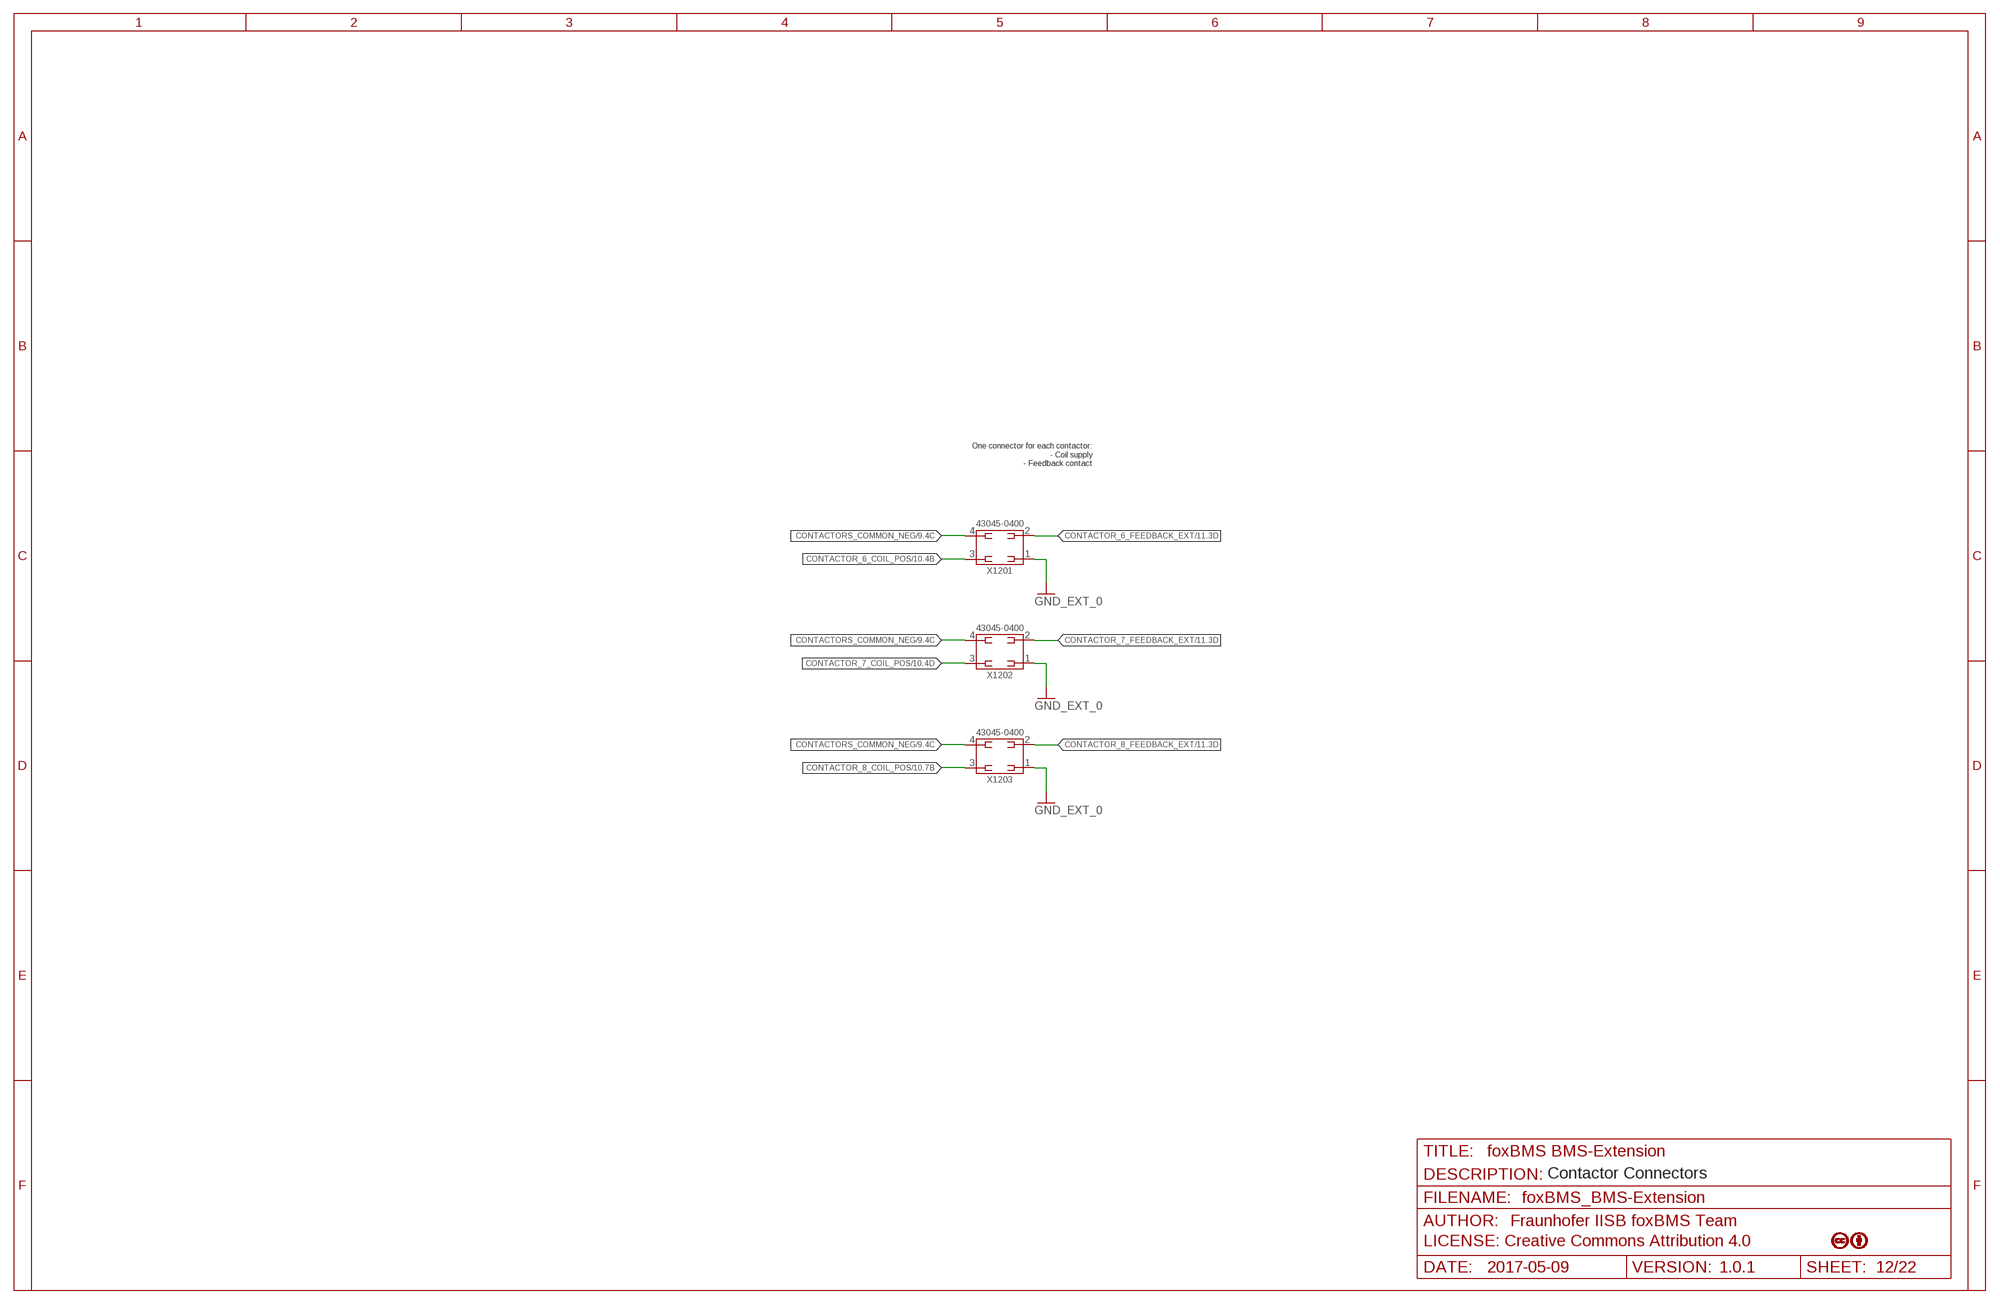
[diagram p11: schematic, sheet 12]
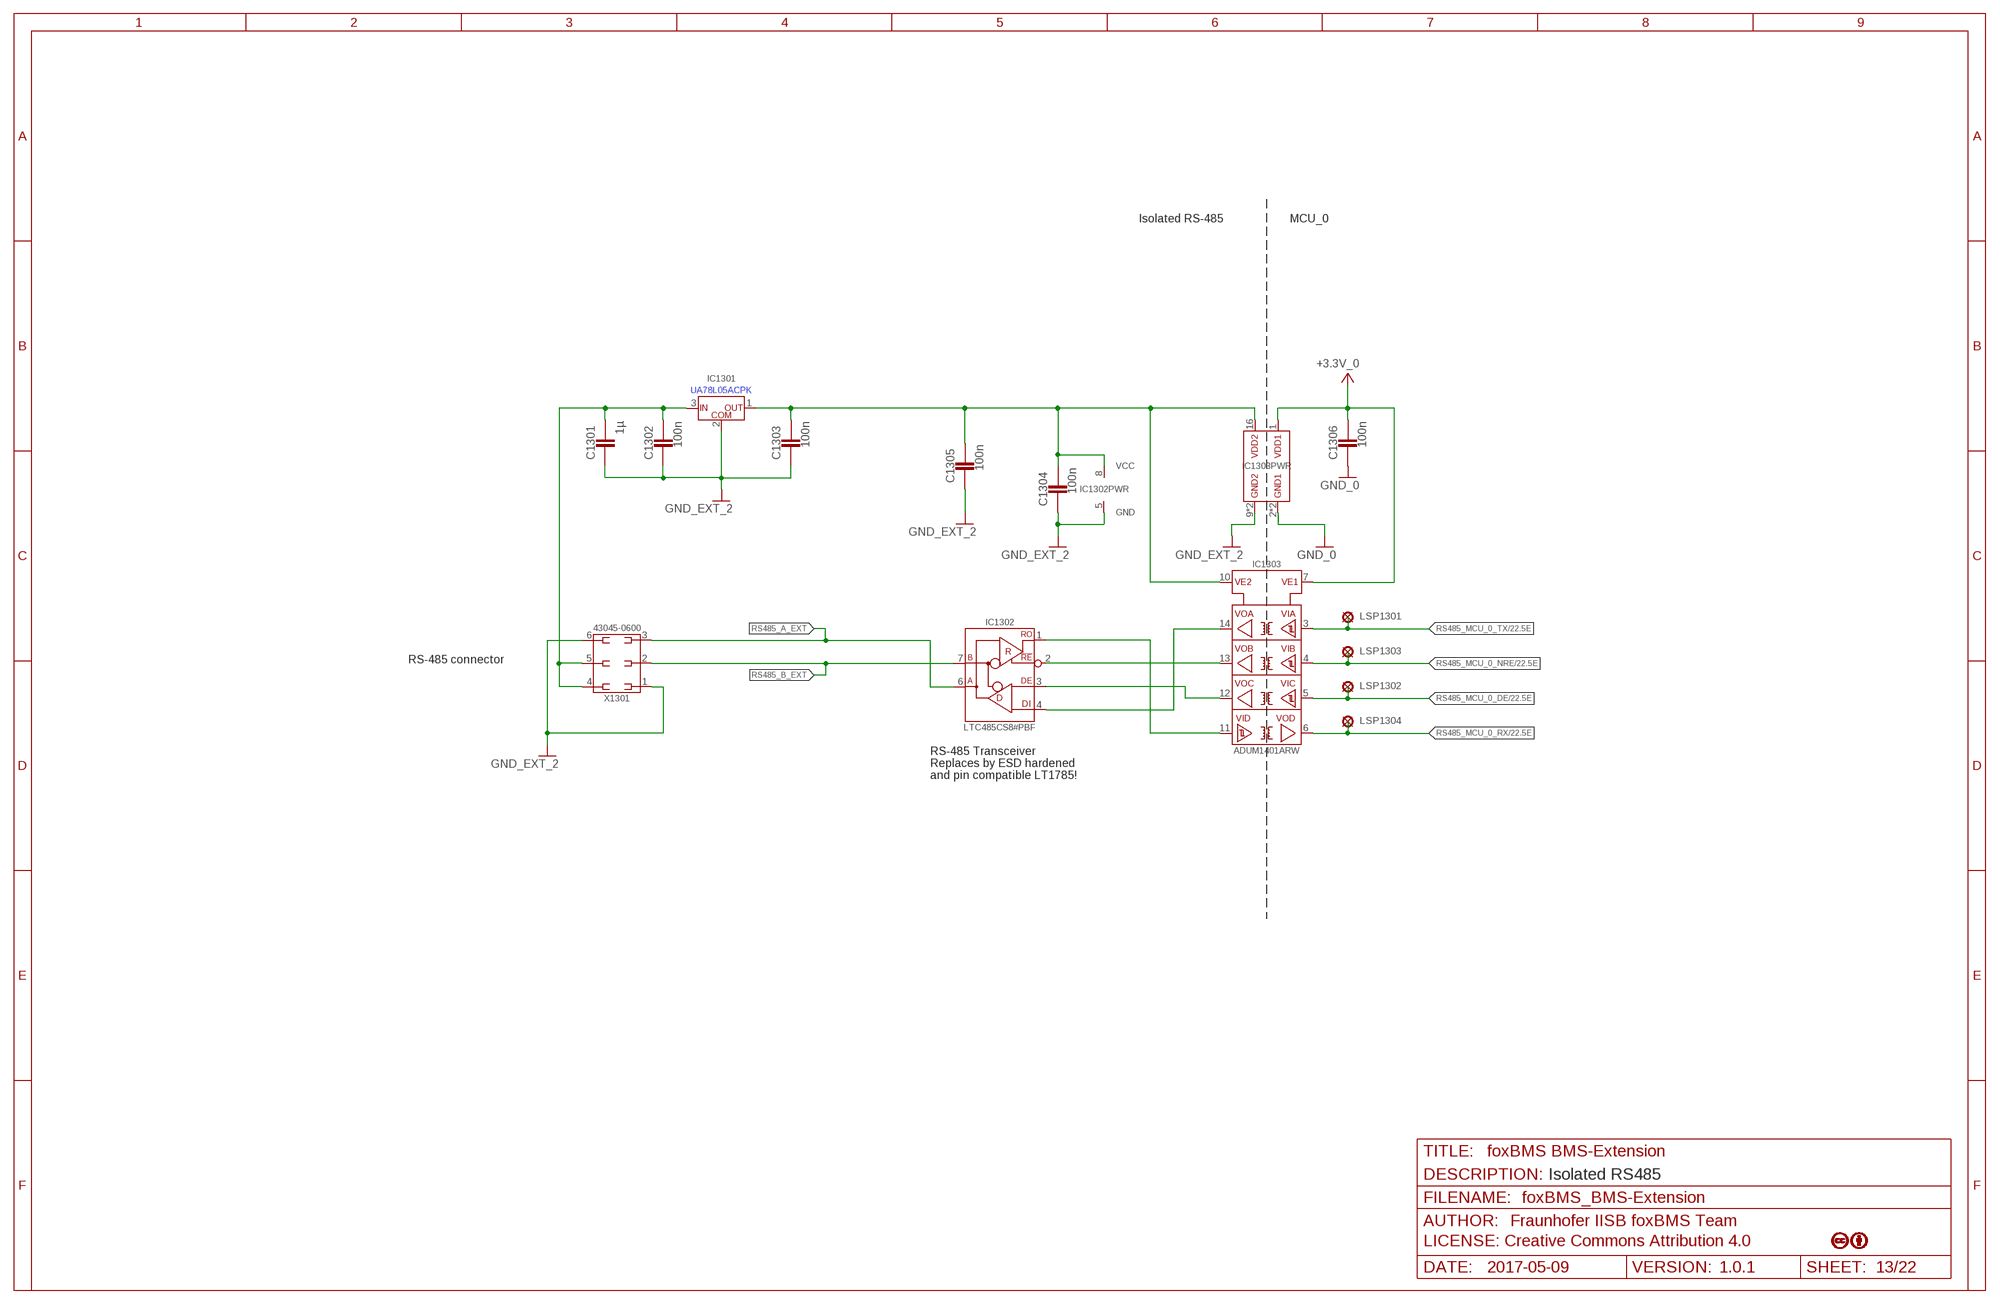
[diagram p12: schematic, sheet 13]
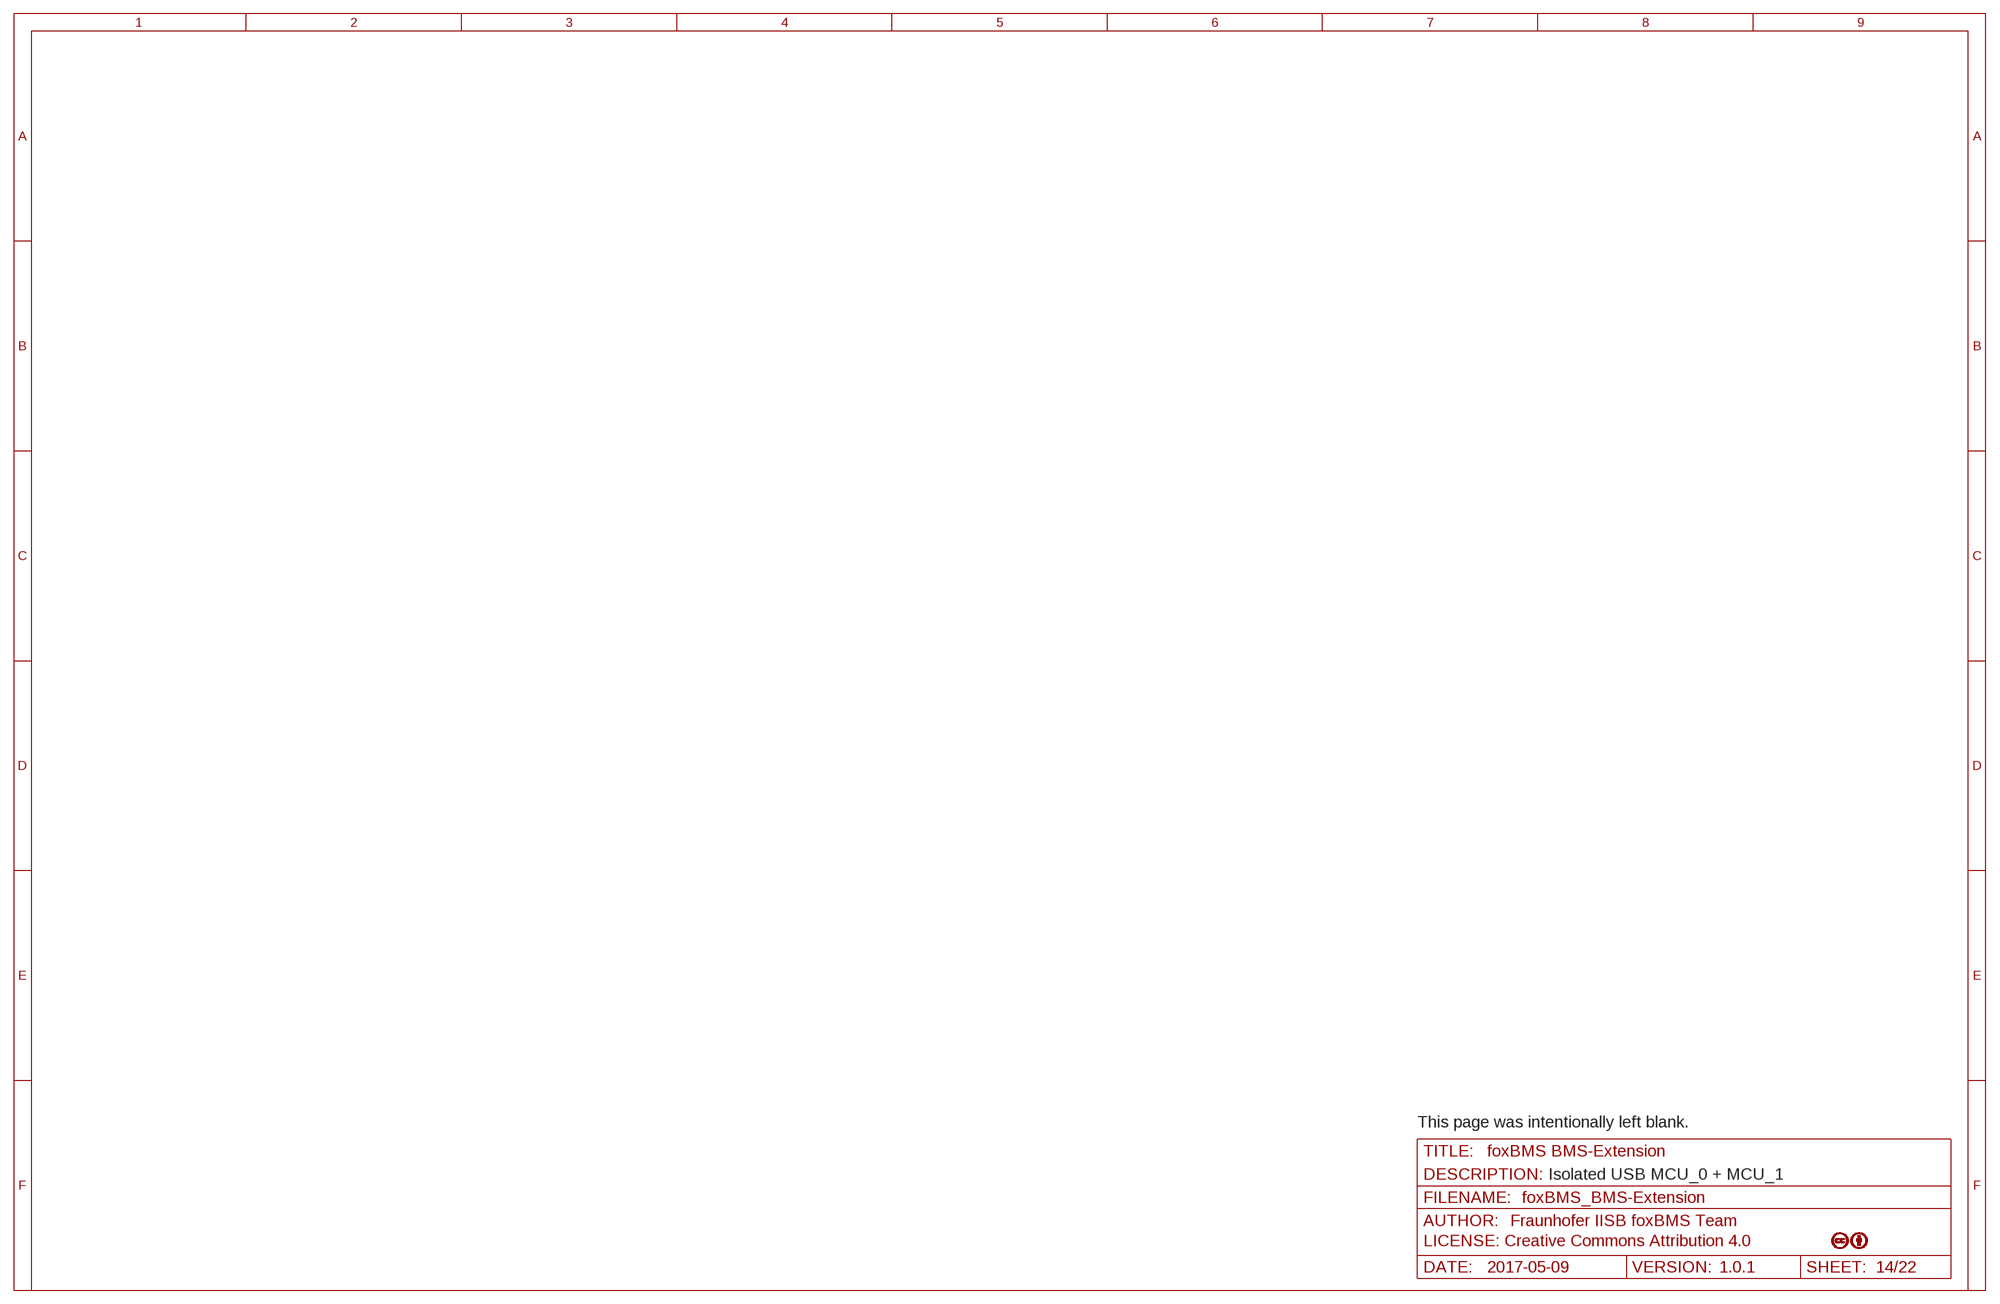
[diagram p13: schematic, sheet 14]
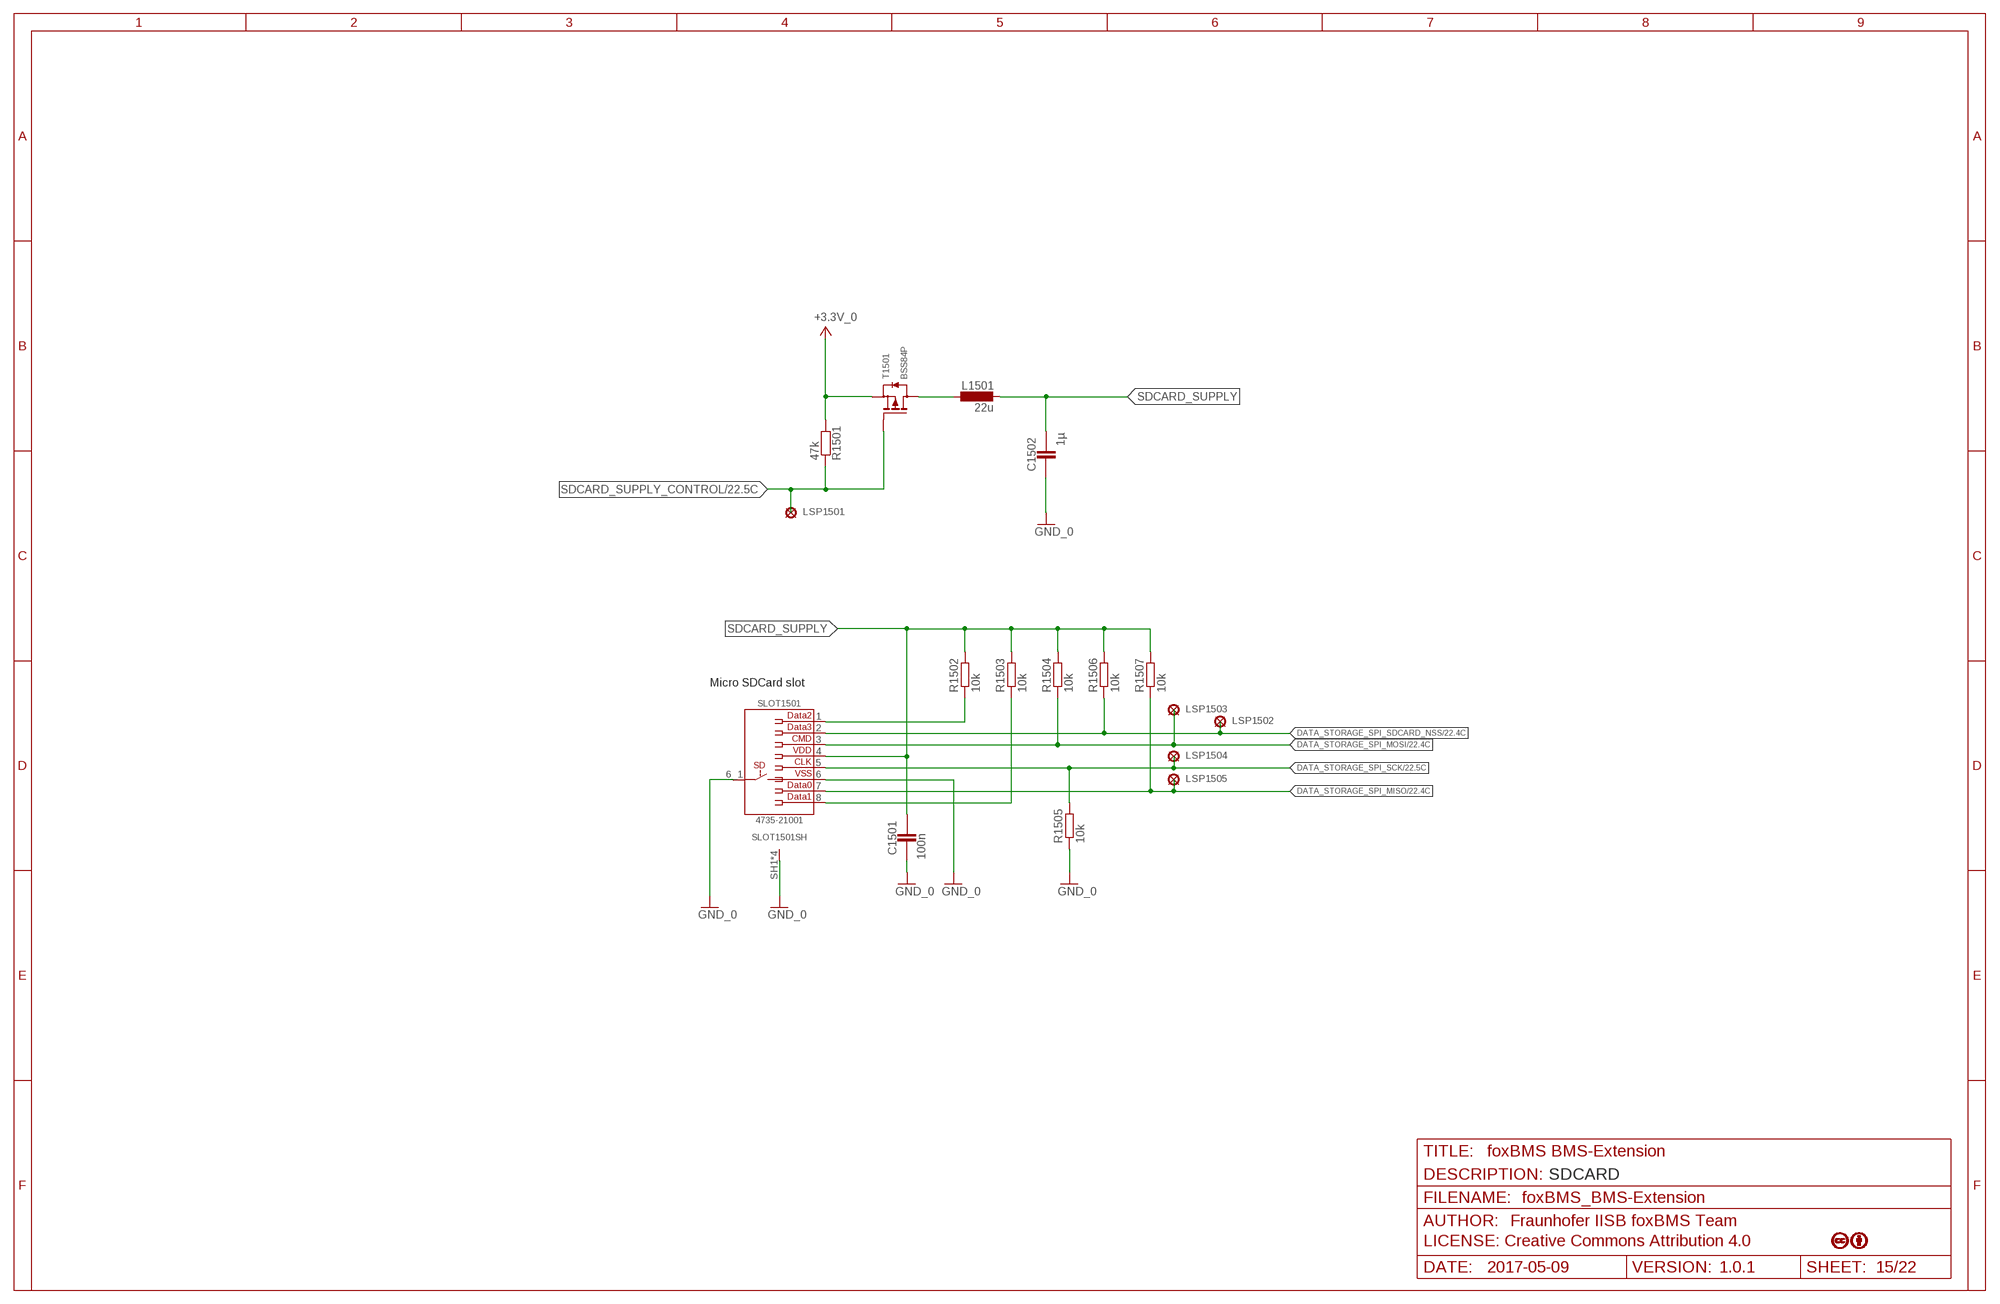
[diagram p14: schematic, sheet 15]
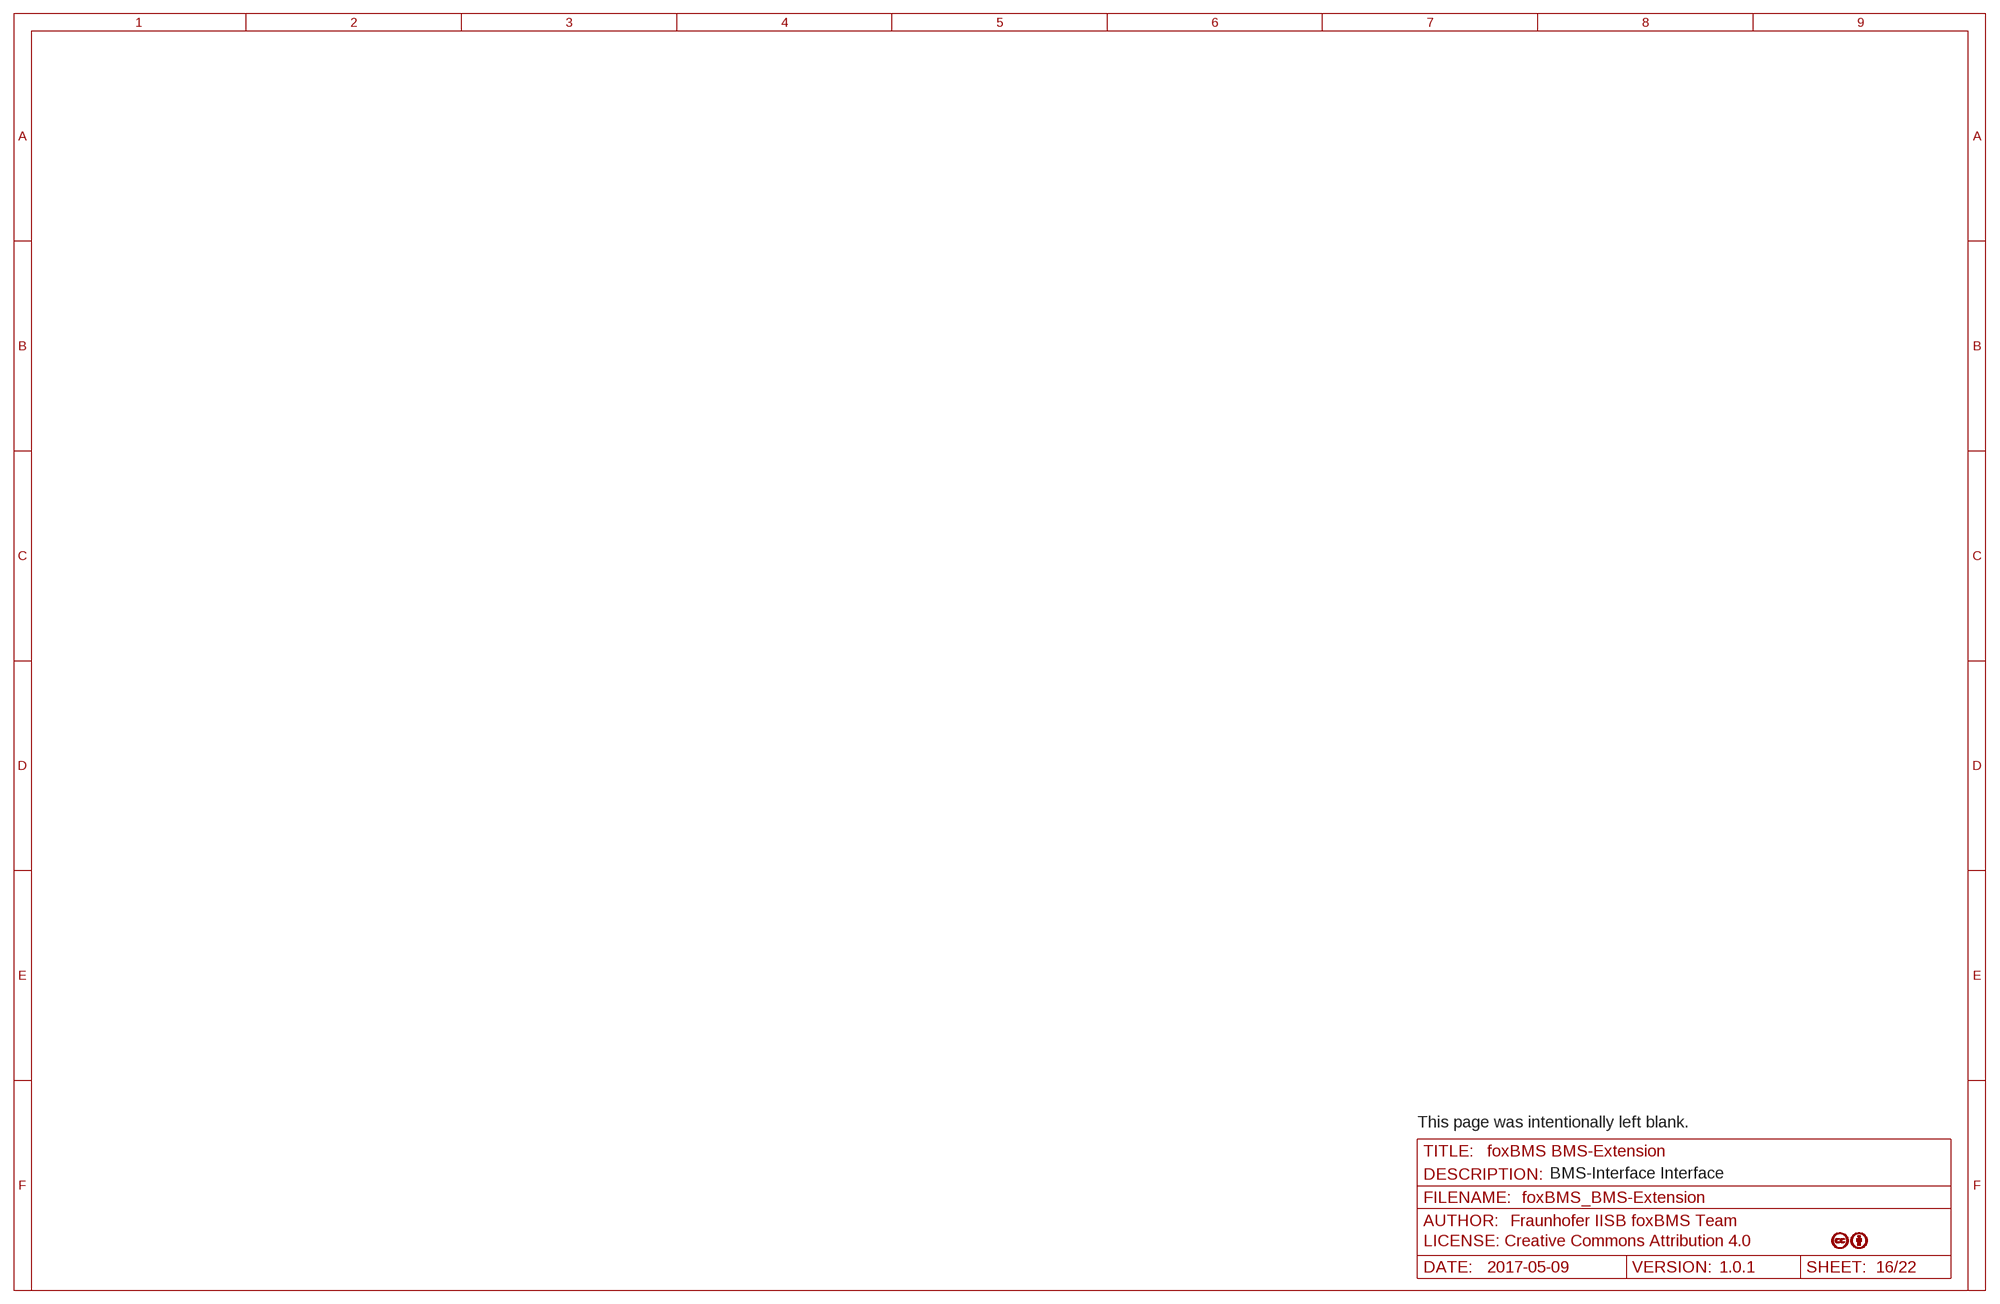
[diagram p15: schematic, sheet 16]
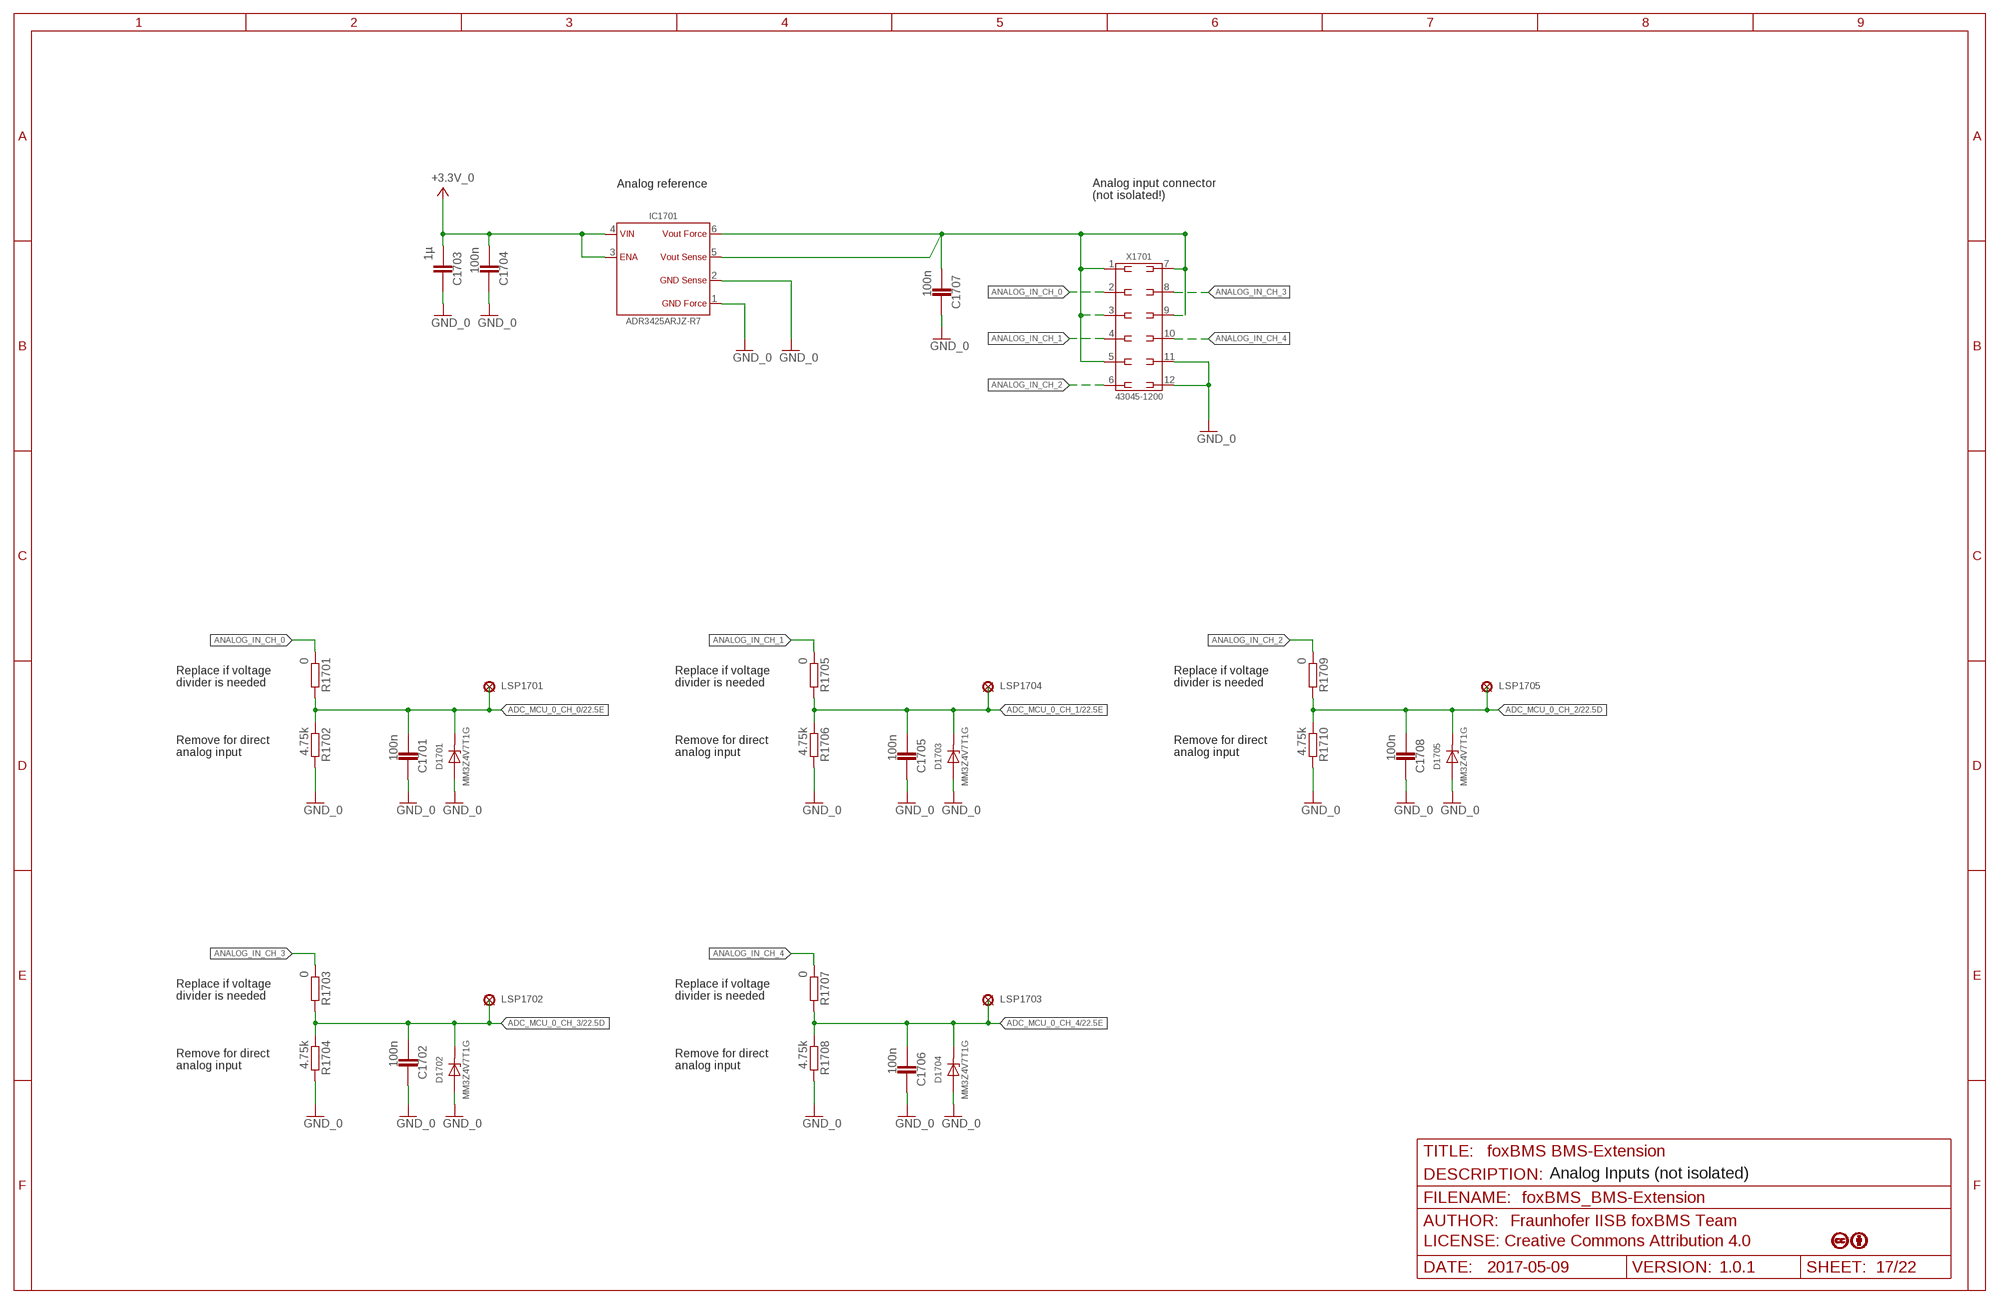
[diagram p16: schematic, sheet 17]
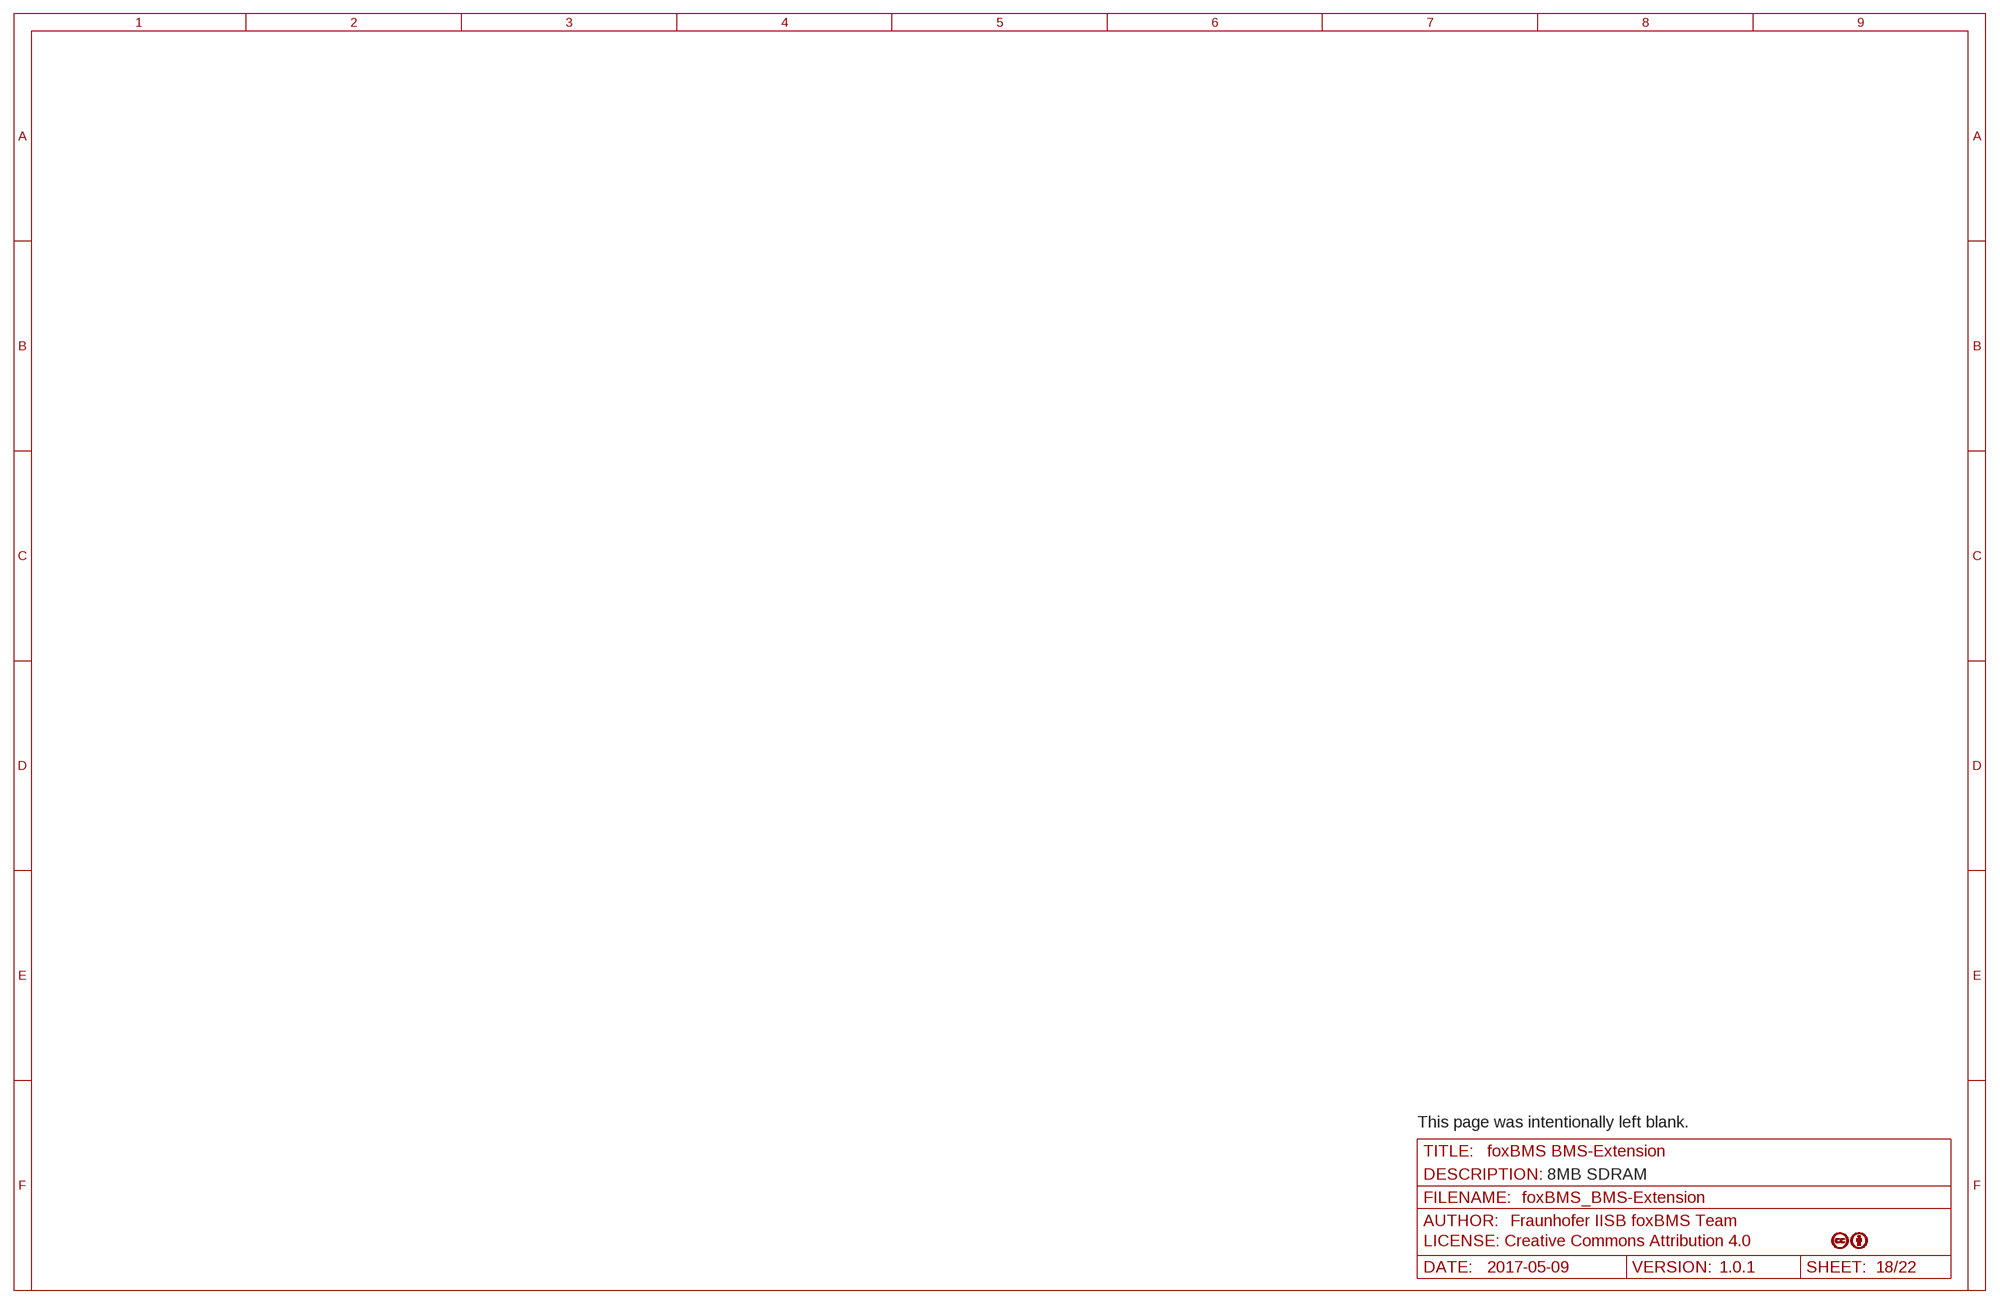
[diagram p17: schematic, sheet 18]
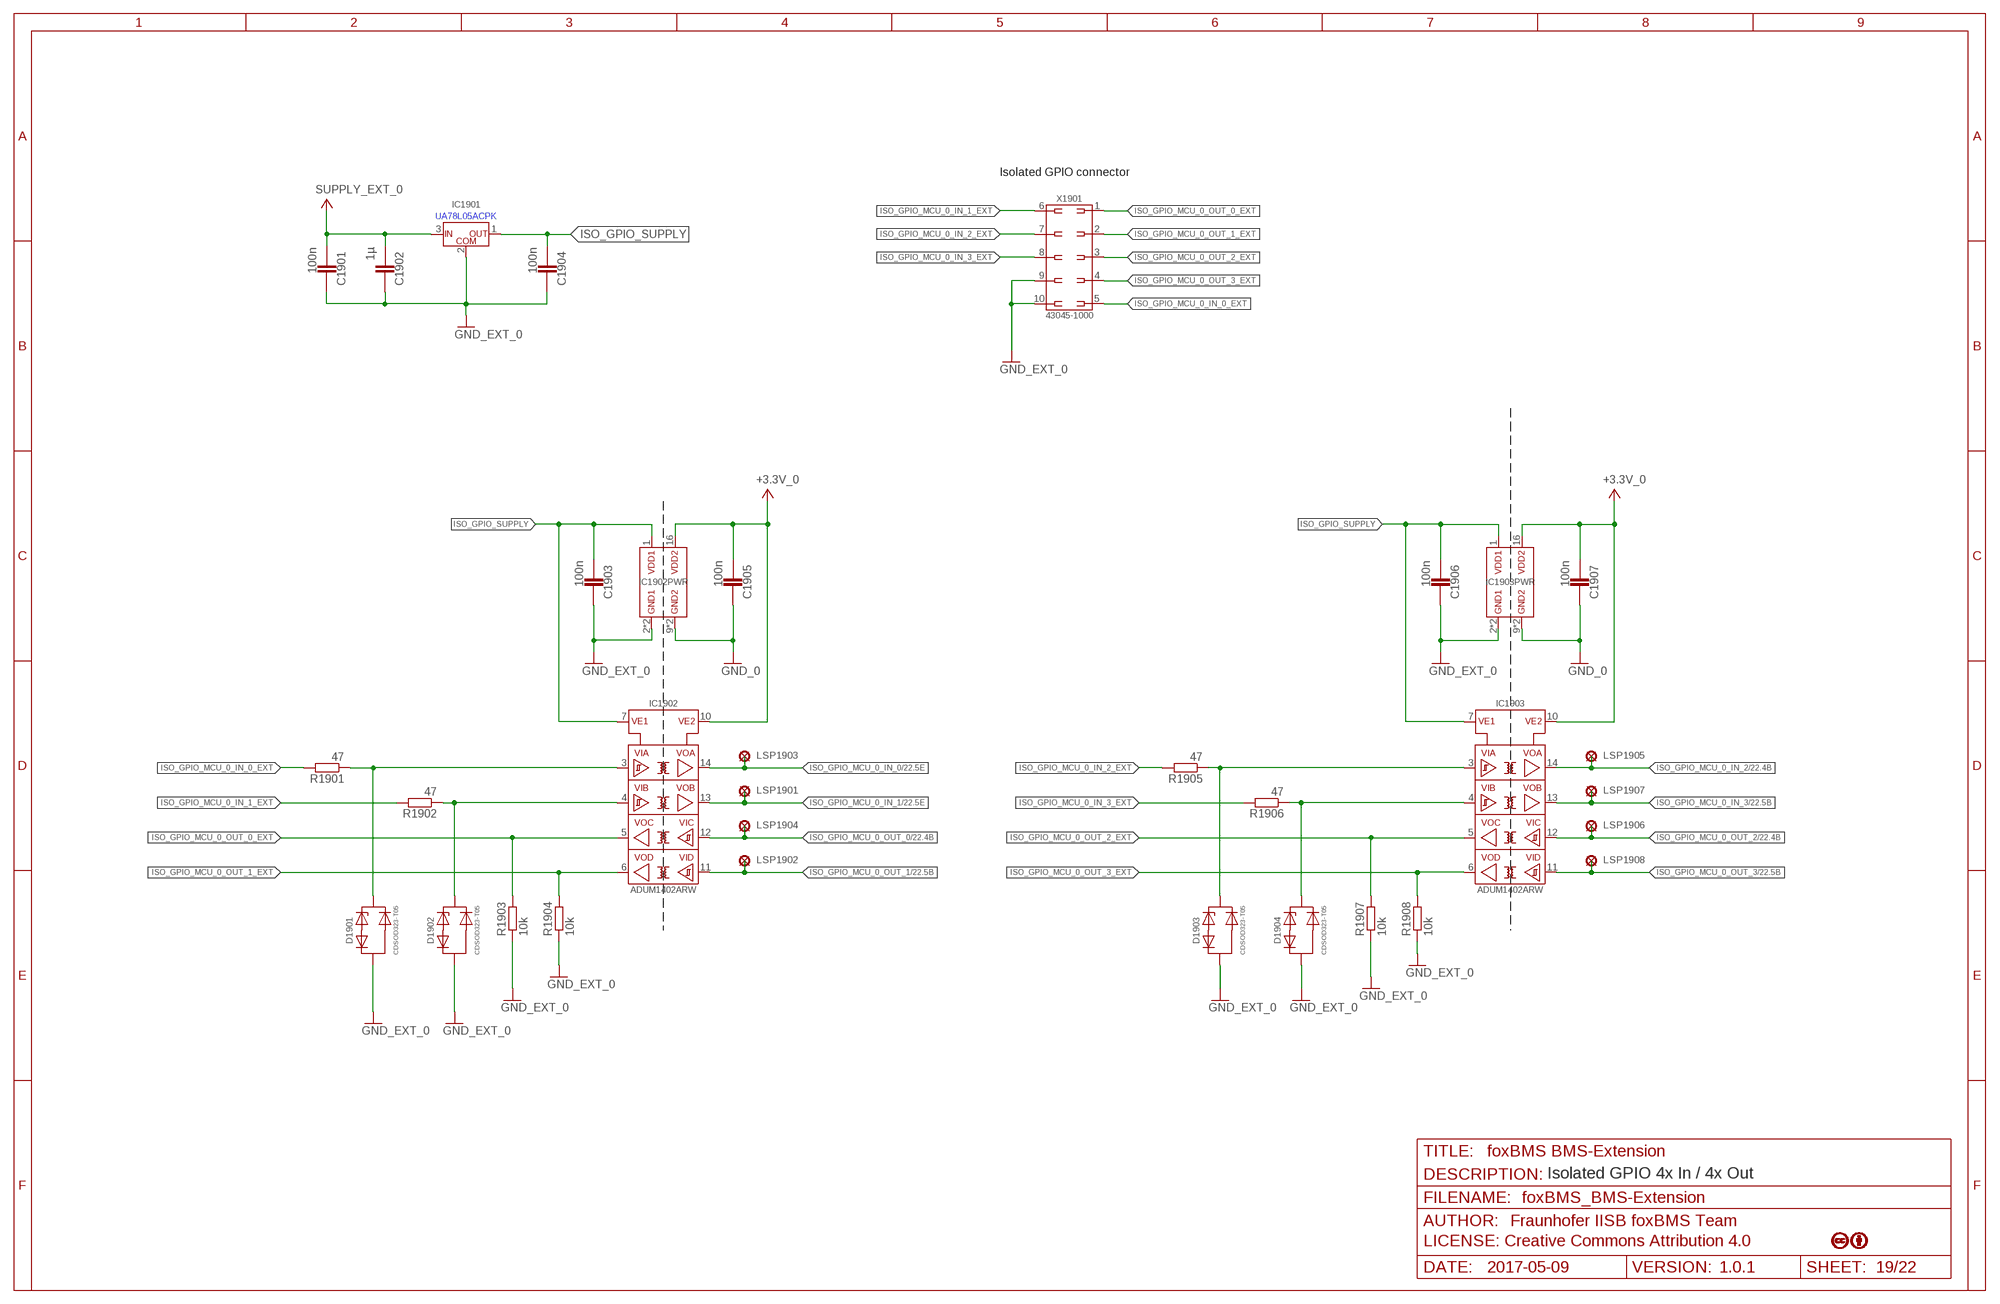
[diagram p18: schematic, sheet 19]
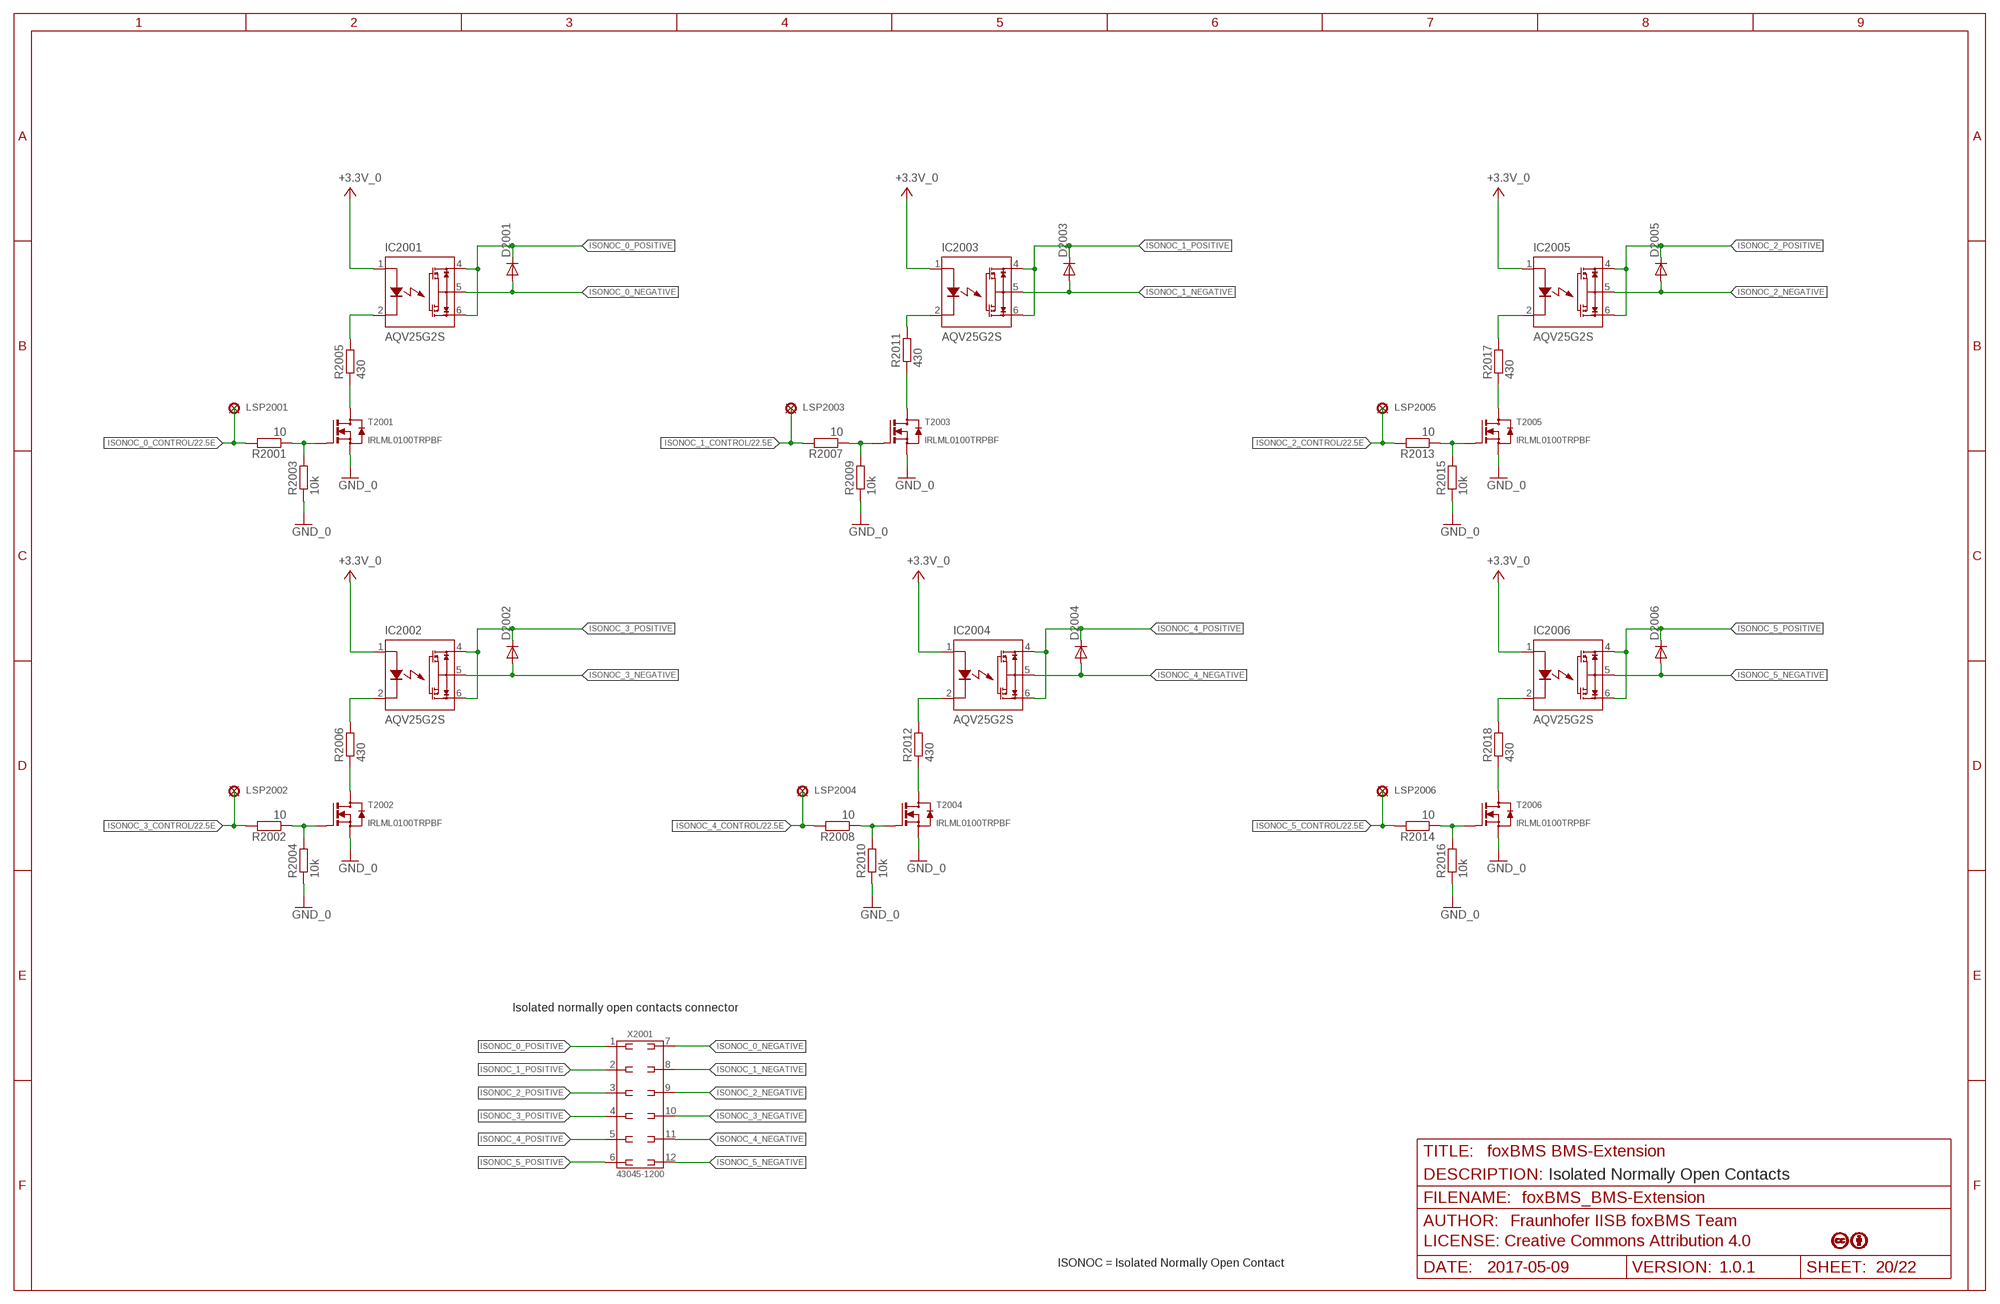
[diagram p19: schematic, sheet 20]
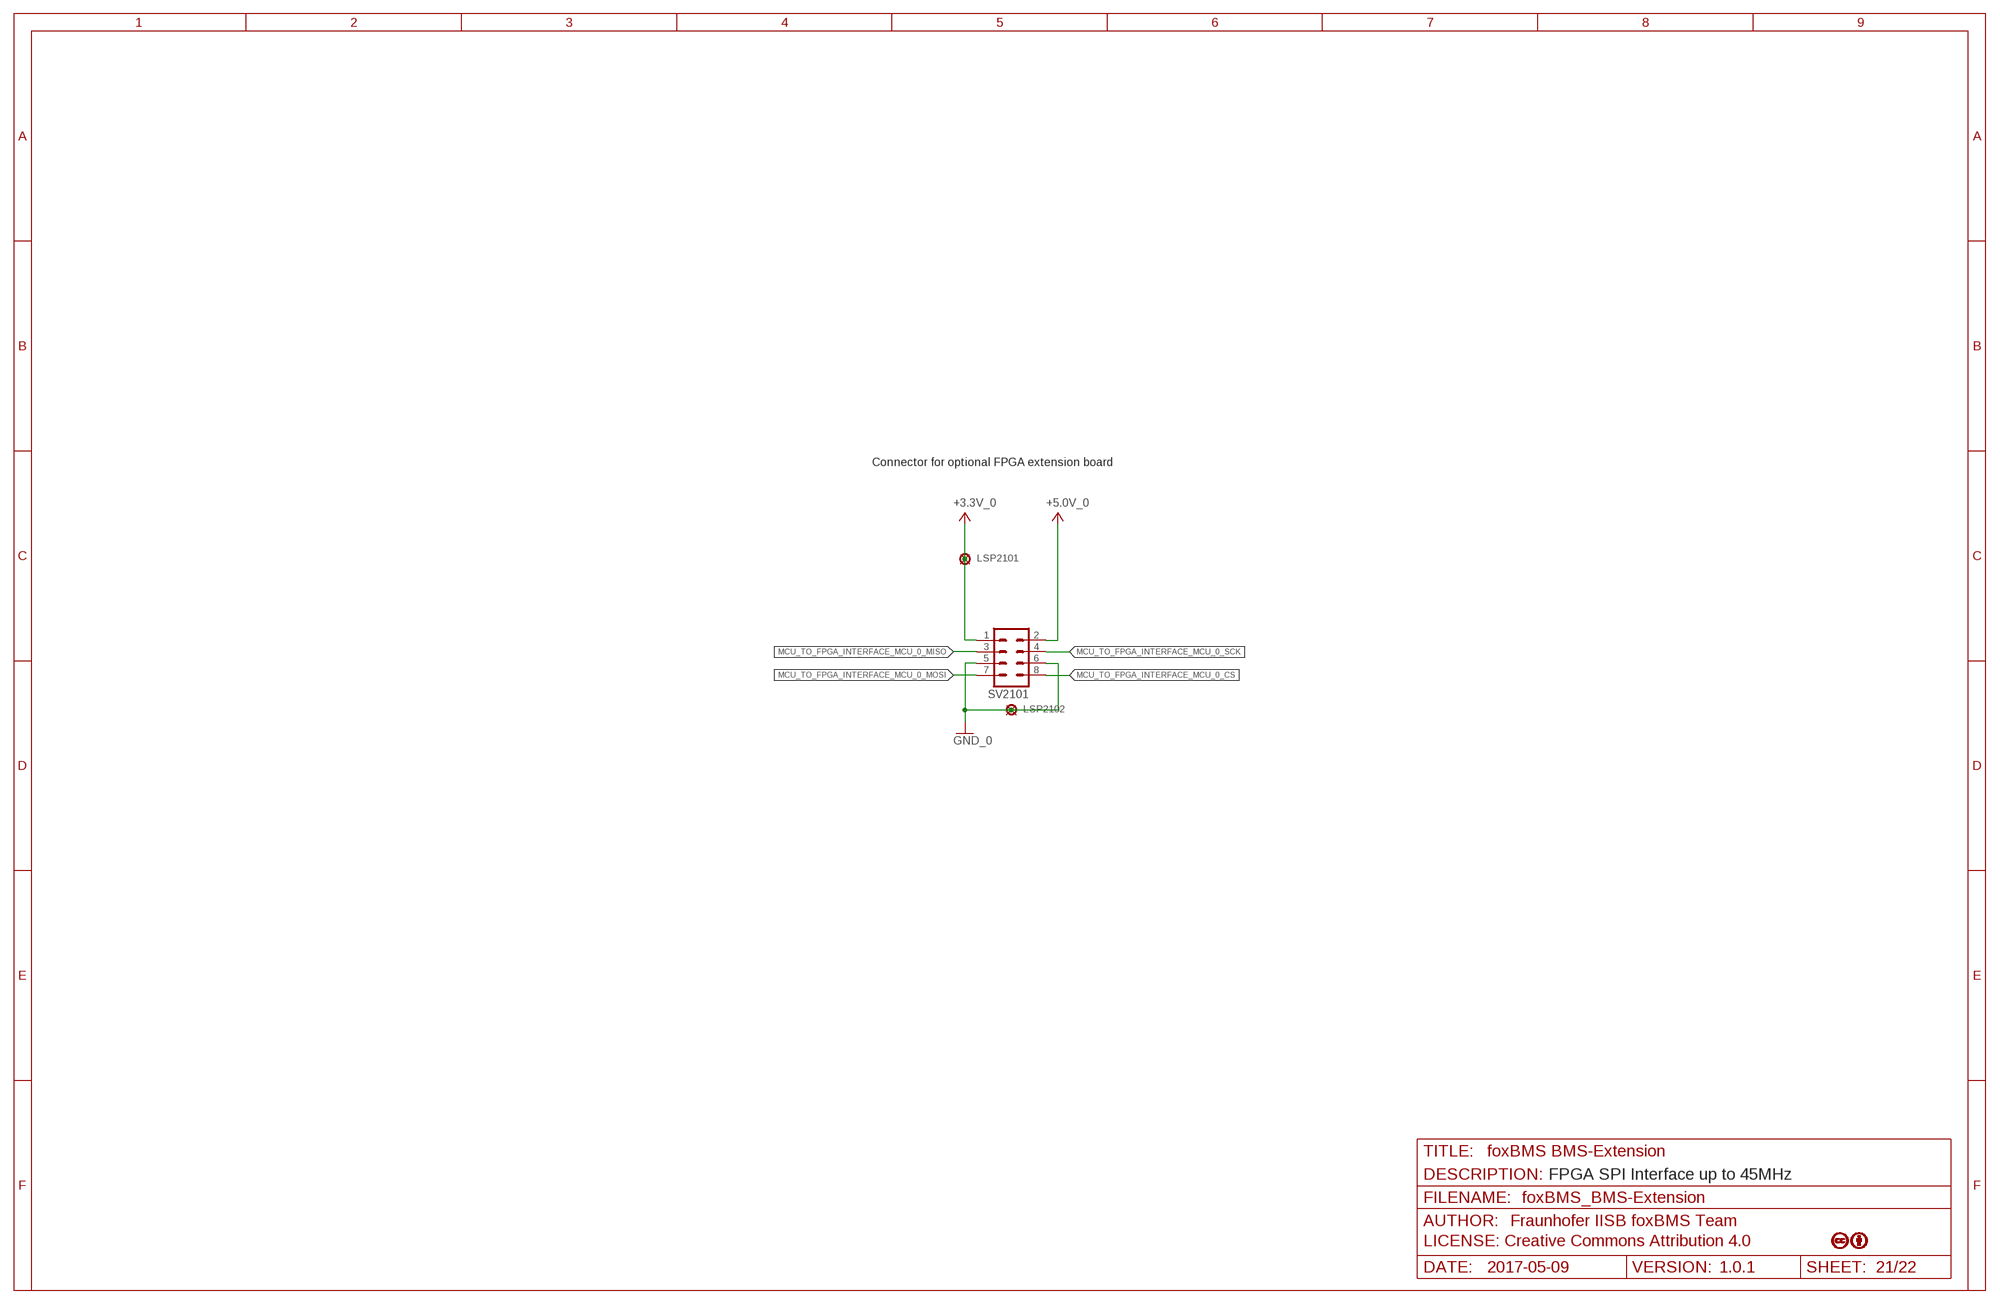
[diagram p20: schematic, sheet 21]
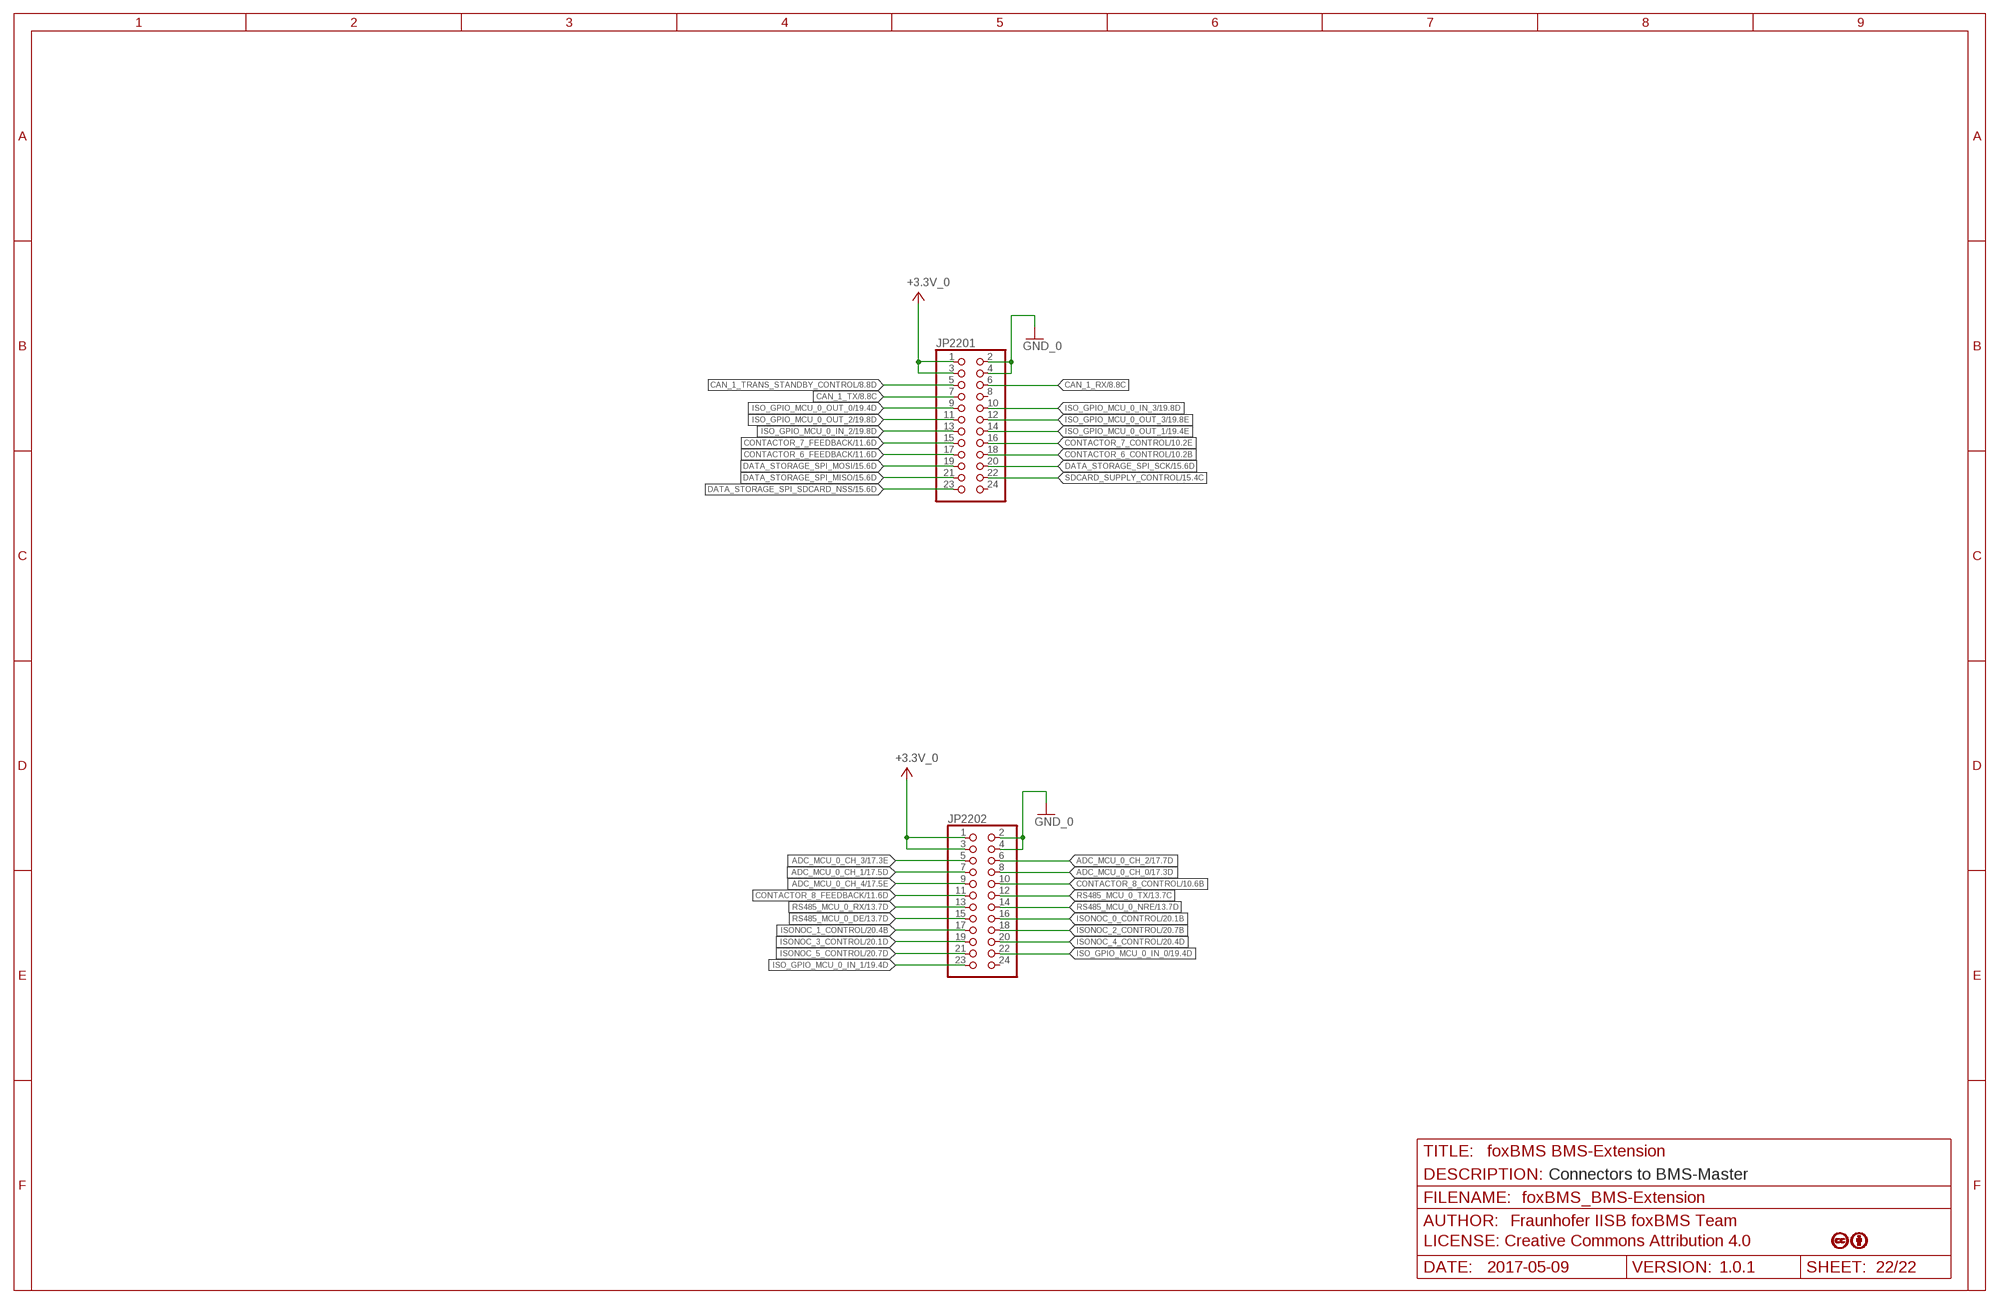
[diagram p21: schematic, sheet 22]

(export (version "E")
  (design (tool "Eeschema 10.0.6"))
  (components
    (comp (ref "C1701")
      (value "100n")
      (footprint "eagle-import:0603")
      (libsource (lib "eagle-import") (part "C0603_X7R_"))
    )
    (comp (ref "C1702")
      (value "100n")
      (footprint "eagle-import:0603")
      (libsource (lib "eagle-import") (part "C0603_X7R_"))
    )
    (comp (ref "C1703")
      (value "1µ")
      (footprint "eagle-import:0603")
      (libsource (lib "eagle-import") (part "C0603_X7R_"))
    )
    (comp (ref "C1704")
      (value "100n")
      (footprint "eagle-import:0603")
      (libsource (lib "eagle-import") (part "C0603_X7R_"))
    )
    (comp (ref "C1705")
      (value "100n")
      (footprint "eagle-import:0603")
      (libsource (lib "eagle-import") (part "C0603_X7R_"))
    )
    (comp (ref "C1706")
      (value "100n")
      (footprint "eagle-import:0603")
      (libsource (lib "eagle-import") (part "C0603_X7R_"))
    )
    (comp (ref "C1707")
      (value "100n")
      (footprint "eagle-import:0603")
      (libsource (lib "eagle-import") (part "C0603_X7R_"))
    )
    (comp (ref "C1708")
      (value "100n")
      (footprint "eagle-import:0603")
      (libsource (lib "eagle-import") (part "C0603_X7R_"))
    )
    (comp (ref "D1701")
      (value "MM3Z3V3ST1G")
      (footprint "eagle-import:D_SMD_SOD323_(SC-76)_R_ON_REV01")
      (fields
        (field (name "PDF-LOCAL") "file:///C:\\Eagle-Datasheet\\Dioden\\MM3ZxxxT1-D_OnSemiconductor.pdf")
      )
      (libsource (lib "eagle-import") (part "MM3Z?T1G4V7"))
    )
    (comp (ref "D1702")
      (value "MM3Z3V3ST1G")
      (footprint "eagle-import:D_SMD_SOD323_(SC-76)_R_ON_REV01")
      (fields
        (field (name "PDF-LOCAL") "file:///C:\\Eagle-Datasheet\\Dioden\\MM3ZxxxT1-D_OnSemiconductor.pdf")
      )
      (libsource (lib "eagle-import") (part "MM3Z?T1G4V7"))
    )
    (comp (ref "D1703")
      (value "MM3Z3V3ST1G")
      (footprint "eagle-import:D_SMD_SOD323_(SC-76)_R_ON_REV01")
      (fields
        (field (name "PDF-LOCAL") "file:///C:\\Eagle-Datasheet\\Dioden\\MM3ZxxxT1-D_OnSemiconductor.pdf")
      )
      (libsource (lib "eagle-import") (part "MM3Z?T1G4V7"))
    )
    (comp (ref "D1704")
      (value "MM3Z3V3ST1G")
      (footprint "eagle-import:D_SMD_SOD323_(SC-76)_R_ON_REV01")
      (fields
        (field (name "PDF-LOCAL") "file:///C:\\Eagle-Datasheet\\Dioden\\MM3ZxxxT1-D_OnSemiconductor.pdf")
      )
      (libsource (lib "eagle-import") (part "MM3Z?T1G4V7"))
    )
    (comp (ref "D1705")
      (value "MM3Z3V3ST1G")
      (footprint "eagle-import:D_SMD_SOD323_(SC-76)_R_ON_REV01")
      (fields
        (field (name "PDF-LOCAL") "file:///C:\\Eagle-Datasheet\\Dioden\\MM3ZxxxT1-D_OnSemiconductor.pdf")
      )
      (libsource (lib "eagle-import") (part "MM3Z?T1G4V7"))
    )
    (comp (ref "IC1701")
      (value "ADR3425ARJZ")
      (footprint "eagle-import:IC_SMD_SOT23-6_(MO-178-AB)_R_AD_REV01")
      (fields
        (field (name "PDF-LOCAL") "file:///C:\\Eagle-Datasheet\\Referenzen\\ADR3412_ADR3420_ADR3425_ADR3430_ADR3433_ADR3440_ADR3450_Analog_Devices.pdf")
      )
      (libsource (lib "eagle-import") (part "ADR3425ARJZ"))
    )
    (comp (ref "LSP1701")
      (value "PAD_2.0X1.5MM")
      (footprint "eagle-import:PAD2.0X1.5MM")
      (libsource (lib "eagle-import") (part "PAD_2.0X1.5MM"))
    )
    (comp (ref "LSP1702")
      (value "PAD_2.0X1.5MM")
      (footprint "eagle-import:PAD2.0X1.5MM")
      (libsource (lib "eagle-import") (part "PAD_2.0X1.5MM"))
    )
    (comp (ref "LSP1703")
      (value "PAD_2.0X1.5MM")
      (footprint "eagle-import:PAD2.0X1.5MM")
      (libsource (lib "eagle-import") (part "PAD_2.0X1.5MM"))
    )
    (comp (ref "LSP1704")
      (value "PAD_2.0X1.5MM")
      (footprint "eagle-import:PAD2.0X1.5MM")
      (libsource (lib "eagle-import") (part "PAD_2.0X1.5MM"))
    )
    (comp (ref "LSP1705")
      (value "PAD_2.0X1.5MM")
      (footprint "eagle-import:PAD2.0X1.5MM")
      (libsource (lib "eagle-import") (part "PAD_2.0X1.5MM"))
    )
    (comp (ref "R1701")
      (value "0")
      (footprint "eagle-import:0603")
      (libsource (lib "eagle-import") (part "R0603_MET_"))
    )
    (comp (ref "R1702")
      (value "4.75k")
      (footprint "eagle-import:0603")
      (libsource (lib "eagle-import") (part "R0603_MET_"))
    )
    (comp (ref "R1703")
      (value "0")
      (footprint "eagle-import:0603")
      (libsource (lib "eagle-import") (part "R0603_MET_"))
    )
    (comp (ref "R1704")
      (value "4.75k")
      (footprint "eagle-import:0603")
      (libsource (lib "eagle-import") (part "R0603_MET_"))
    )
    (comp (ref "R1705")
      (value "0")
      (footprint "eagle-import:0603")
      (libsource (lib "eagle-import") (part "R0603_MET_"))
    )
    (comp (ref "R1706")
      (value "4.75k")
      (footprint "eagle-import:0603")
      (libsource (lib "eagle-import") (part "R0603_MET_"))
    )
    (comp (ref "R1707")
      (value "0")
      (footprint "eagle-import:0603")
      (libsource (lib "eagle-import") (part "R0603_MET_"))
    )
    (comp (ref "R1708")
      (value "4.75k")
      (footprint "eagle-import:0603")
      (libsource (lib "eagle-import") (part "R0603_MET_"))
    )
    (comp (ref "R1709")
      (value "0")
      (footprint "eagle-import:0603")
      (libsource (lib "eagle-import") (part "R0603_MET_"))
    )
    (comp (ref "R1710")
      (value "4.75k")
      (footprint "eagle-import:0603")
      (libsource (lib "eagle-import") (part "R0603_MET_"))
    )
    (comp (ref "X1701")
      (value "43045-1200_MOLEX_12PIN")
      (footprint "eagle-import:X_TH_MOLEX_43045-1200_R_REV01")
      (fields (field (name "PDF-LOCAL") "file:///C:\\Eagle-Datasheet\\Steckverbindung\\430451200_Molex.pdf"))
      (libsource (lib "eagle-import") (part "43045-12?_MOLEX_12PIN00"))
    )
    (comp (ref "C1101")
      (value "100n")
      (footprint "eagle-import:0603")
      (libsource (lib "eagle-import") (part "C0603_X7R_"))
    )
    (comp (ref "C1102")
      (value "1µ")
      (footprint "eagle-import:0603")
      (libsource (lib "eagle-import") (part "C0603_X7R_"))
    )
    (comp (ref "C1103")
      (value "100n")
      (footprint "eagle-import:0603")
      (libsource (lib "eagle-import") (part "C0603_X7R_"))
    )
    (comp (ref "C1104")
      (value "100n")
      (footprint "eagle-import:0603")
      (libsource (lib "eagle-import") (part "C0603_X7R_"))
    )
    (comp (ref "C1105")
      (value "100n")
      (footprint "eagle-import:0603")
      (libsource (lib "eagle-import") (part "C0603_X7R_"))
    )
    (comp (ref "C1106")
      (value "100n")
      (footprint "eagle-import:0603")
      (libsource (lib "eagle-import") (part "C0603_X7R_"))
    )
    (comp (ref "D1101")
      (value "CDSOD323-T05")
      (footprint "eagle-import:D_SMD_SOD323_(SC-76)_R_BOURNS_REV01")
      (libsource (lib "eagle-import") (part "CDSOD323-T?05"))
    )
    (comp (ref "D1102")
      (value "CDSOD323-T05")
      (footprint "eagle-import:D_SMD_SOD323_(SC-76)_R_BOURNS_REV01")
      (libsource (lib "eagle-import") (part "CDSOD323-T?05"))
    )
    (comp (ref "D1103")
      (value "CDSOD323-T05")
      (footprint "eagle-import:D_SMD_SOD323_(SC-76)_R_BOURNS_REV01")
      (libsource (lib "eagle-import") (part "CDSOD323-T?05"))
    )
    (comp (ref "IC1101")
      (value "UA78L05ACPK")
      (footprint "eagle-import:IC_SMD_SOT-89_(SC-62_TO-243)_(R-PSSO-F3)_R_TI_REV01")
      (fields
        (field (name "PDF-LOCAL") "file:///C:\\Eagle-Datasheet\\Spannungsregler\\UA78L00_Texas_Instruments.pdf")
      )
      (libsource (lib "eagle-import") (part "UA78L?PK05AC"))
    )
    (comp (ref "IC1102")
      (value "ADUM1300ARW")
      (footprint "eagle-import:IC_SMD_SOIC-16_(JEDEC_MS-013-AA)_R_ANALOG_REV01")
      (fields
        (field (name "PDF-LOCAL") "file:///C:\\Eagle-Datasheet\\Schnittstellen-IC\\ADuM1300_1301_Linear.pdf")
      )
      (libsource (lib "eagle-import") (part "ADUM1300ARW"))
    )
    (comp (ref "LSP1101")
      (value "PAD_2.0X1.5MM")
      (footprint "eagle-import:PAD2.0X1.5MM")
      (libsource (lib "eagle-import") (part "PAD_2.0X1.5MM"))
    )
    (comp (ref "LSP1102")
      (value "PAD_2.0X1.5MM")
      (footprint "eagle-import:PAD2.0X1.5MM")
      (libsource (lib "eagle-import") (part "PAD_2.0X1.5MM"))
    )
    (comp (ref "LSP1103")
      (value "PAD_2.0X1.5MM")
      (footprint "eagle-import:PAD2.0X1.5MM")
      (libsource (lib "eagle-import") (part "PAD_2.0X1.5MM"))
    )
    (comp (ref "R1101")
      (value "47")
      (footprint "eagle-import:0603")
      (libsource (lib "eagle-import") (part "R0603_MET_"))
    )
    (comp (ref "R1102")
      (value "47")
      (footprint "eagle-import:0603")
      (libsource (lib "eagle-import") (part "R0603_MET_"))
    )
    (comp (ref "R1103")
      (value "47")
      (footprint "eagle-import:0603")
      (libsource (lib "eagle-import") (part "R0603_MET_"))
    )
    (comp (ref "R1104")
      (value "10k")
      (footprint "eagle-import:0603")
      (libsource (lib "eagle-import") (part "R0603_MET_"))
    )
    (comp (ref "R1105")
      (value "10k")
      (footprint "eagle-import:0603")
      (libsource (lib "eagle-import") (part "R0603_MET_"))
    )
    (comp (ref "R1106")
      (value "10k")
      (footprint "eagle-import:0603")
      (libsource (lib "eagle-import") (part "R0603_MET_"))
    )
    (comp (ref "C1301")
      (value "1µ")
      (footprint "eagle-import:0603")
      (libsource (lib "eagle-import") (part "C0603_X7R_"))
    )
    (comp (ref "C1302")
      (value "100n")
      (footprint "eagle-import:0603")
      (libsource (lib "eagle-import") (part "C0603_X7R_"))
    )
    (comp (ref "C1303")
      (value "100n")
      (footprint "eagle-import:0603")
      (libsource (lib "eagle-import") (part "C0603_X7R_"))
    )
    (comp (ref "C1304")
      (value "100n")
      (footprint "eagle-import:0603")
      (libsource (lib "eagle-import") (part "C0603_X7R_"))
    )
    (comp (ref "C1305")
      (value "100n")
      (footprint "eagle-import:0603")
      (libsource (lib "eagle-import") (part "C0603_X7R_"))
    )
    (comp (ref "C1306")
      (value "100n")
      (footprint "eagle-import:0603")
      (libsource (lib "eagle-import") (part "C0603_X7R_"))
    )
    (comp (ref "IC1301")
      (value "UA78L05ACPK")
      (footprint "eagle-import:IC_SMD_SOT-89_(SC-62_TO-243)_(R-PSSO-F3)_R_TI_REV01")
      (fields
        (field (name "PDF-LOCAL") "file:///C:\\Eagle-Datasheet\\Spannungsregler\\UA78L00_Texas_Instruments.pdf")
      )
      (libsource (lib "eagle-import") (part "UA78L?PK05AC"))
    )
    (comp (ref "IC1302")
      (value "LTC485CS8#PBF")
      (footprint "eagle-import:IC_SMD_SOIC-8_(S8_REV_G)_R_LINEAR_REV01")
      (fields (field (name "PDF-LOCAL") "file:///C:\\Eagle-Datasheet\\Schnittstellen-IC\\LTC485_Linear.pdf"))
      (libsource (lib "eagle-import") (part "LTC485S8#PBFC"))
    )
    (comp (ref "IC1303")
      (value "ADUM1401ARW")
      (footprint "eagle-import:IC_SMD_SOIC-16_(JEDEC_MS-013-AA)_R_ANALOG_REV01")
      (fields
        (field (name "PDF-LOCAL") "file:///C:\\Eagle-Datasheet\\Schnittstellen-IC\\ADuM1400_1401_1402_Linear.pdf")
      )
      (libsource (lib "eagle-import") (part "ADUM1401ARW"))
    )
    (comp (ref "LSP1301")
      (value "PAD_2.0X1.5MM")
      (footprint "eagle-import:PAD2.0X1.5MM")
      (libsource (lib "eagle-import") (part "PAD_2.0X1.5MM"))
    )
    (comp (ref "LSP1302")
      (value "PAD_2.0X1.5MM")
      (footprint "eagle-import:PAD2.0X1.5MM")
      (libsource (lib "eagle-import") (part "PAD_2.0X1.5MM"))
    )
    (comp (ref "LSP1303")
      (value "PAD_2.0X1.5MM")
      (footprint "eagle-import:PAD2.0X1.5MM")
      (libsource (lib "eagle-import") (part "PAD_2.0X1.5MM"))
    )
    (comp (ref "LSP1304")
      (value "PAD_2.0X1.5MM")
      (footprint "eagle-import:PAD2.0X1.5MM")
      (libsource (lib "eagle-import") (part "PAD_2.0X1.5MM"))
    )
    (comp (ref "X1301")
      (value "43045-0600_MOLEX_6PIN")
      (footprint "eagle-import:X_TH_MOLEX_43045-0600_R_REV01")
      (fields (field (name "PDF-LOCAL") "file:///C:\\Eagle-Datasheet\\Steckverbindung\\430450600_Molex.pdf"))
      (libsource (lib "eagle-import") (part "43045-06?_MOLEX_6PIN00"))
    )
    (comp (ref "C1901")
      (value "100n")
      (footprint "eagle-import:0603")
      (libsource (lib "eagle-import") (part "C0603_X7R_"))
    )
    (comp (ref "C1902")
      (value "1µ")
      (footprint "eagle-import:0603")
      (libsource (lib "eagle-import") (part "C0603_X7R_"))
    )
    (comp (ref "C1903")
      (value "100n")
      (footprint "eagle-import:0603")
      (libsource (lib "eagle-import") (part "C0603_X7R_"))
    )
    (comp (ref "C1904")
      (value "100n")
      (footprint "eagle-import:0603")
      (libsource (lib "eagle-import") (part "C0603_X7R_"))
    )
    (comp (ref "C1905")
      (value "100n")
      (footprint "eagle-import:0603")
      (libsource (lib "eagle-import") (part "C0603_X7R_"))
    )
    (comp (ref "C1906")
      (value "100n")
      (footprint "eagle-import:0603")
      (libsource (lib "eagle-import") (part "C0603_X7R_"))
    )
    (comp (ref "C1907")
      (value "100n")
      (footprint "eagle-import:0603")
      (libsource (lib "eagle-import") (part "C0603_X7R_"))
    )
    (comp (ref "D1901")
      (value "CDSOD323-T05")
      (footprint "eagle-import:D_SMD_SOD323_(SC-76)_R_BOURNS_REV01")
      (libsource (lib "eagle-import") (part "CDSOD323-T?05"))
    )
    (comp (ref "D1902")
      (value "CDSOD323-T05")
      (footprint "eagle-import:D_SMD_SOD323_(SC-76)_R_BOURNS_REV01")
      (libsource (lib "eagle-import") (part "CDSOD323-T?05"))
    )
    (comp (ref "D1903")
      (value "CDSOD323-T05")
      (footprint "eagle-import:D_SMD_SOD323_(SC-76)_R_BOURNS_REV01")
      (libsource (lib "eagle-import") (part "CDSOD323-T?05"))
    )
    (comp (ref "D1904")
      (value "CDSOD323-T05")
      (footprint "eagle-import:D_SMD_SOD323_(SC-76)_R_BOURNS_REV01")
      (libsource (lib "eagle-import") (part "CDSOD323-T?05"))
    )
    (comp (ref "IC1901")
      (value "UA78L05ACPK")
      (footprint "eagle-import:IC_SMD_SOT-89_(SC-62_TO-243)_(R-PSSO-F3)_R_TI_REV01")
      (fields
        (field (name "PDF-LOCAL") "file:///C:\\Eagle-Datasheet\\Spannungsregler\\UA78L00_Texas_Instruments.pdf")
      )
      (libsource (lib "eagle-import") (part "UA78L?PK05AC"))
    )
    (comp (ref "IC1902")
      (value "ADUM1402ARW")
      (footprint "eagle-import:IC_SMD_SOIC-16_(JEDEC_MS-013-AA)_R_ANALOG_REV01")
      (fields
        (field (name "PDF-LOCAL") "file:///C:\\Eagle-Datasheet\\Schnittstellen-IC\\ADuM1400_1401_1402_Linear.pdf")
      )
      (libsource (lib "eagle-import") (part "ADUM1402ARW"))
    )
    (comp (ref "IC1903")
      (value "ADUM1402ARW")
      (footprint "eagle-import:IC_SMD_SOIC-16_(JEDEC_MS-013-AA)_R_ANALOG_REV01")
      (fields
        (field (name "PDF-LOCAL") "file:///C:\\Eagle-Datasheet\\Schnittstellen-IC\\ADuM1400_1401_1402_Linear.pdf")
      )
      (libsource (lib "eagle-import") (part "ADUM1402ARW"))
    )
    (comp (ref "LSP1901")
      (value "PAD_2.0X1.5MM")
      (footprint "eagle-import:PAD2.0X1.5MM")
      (libsource (lib "eagle-import") (part "PAD_2.0X1.5MM"))
    )
    (comp (ref "LSP1902")
      (value "PAD_2.0X1.5MM")
      (footprint "eagle-import:PAD2.0X1.5MM")
      (libsource (lib "eagle-import") (part "PAD_2.0X1.5MM"))
    )
    (comp (ref "LSP1903")
      (value "PAD_2.0X1.5MM")
      (footprint "eagle-import:PAD2.0X1.5MM")
      (libsource (lib "eagle-import") (part "PAD_2.0X1.5MM"))
    )
    (comp (ref "LSP1904")
      (value "PAD_2.0X1.5MM")
      (footprint "eagle-import:PAD2.0X1.5MM")
      (libsource (lib "eagle-import") (part "PAD_2.0X1.5MM"))
    )
    (comp (ref "LSP1905")
      (value "PAD_2.0X1.5MM")
      (footprint "eagle-import:PAD2.0X1.5MM")
      (libsource (lib "eagle-import") (part "PAD_2.0X1.5MM"))
    )
    (comp (ref "LSP1906")
      (value "PAD_2.0X1.5MM")
      (footprint "eagle-import:PAD2.0X1.5MM")
      (libsource (lib "eagle-import") (part "PAD_2.0X1.5MM"))
    )
    (comp (ref "LSP1907")
      (value "PAD_2.0X1.5MM")
      (footprint "eagle-import:PAD2.0X1.5MM")
      (libsource (lib "eagle-import") (part "PAD_2.0X1.5MM"))
    )
    (comp (ref "LSP1908")
      (value "PAD_2.0X1.5MM")
      (footprint "eagle-import:PAD2.0X1.5MM")
      (libsource (lib "eagle-import") (part "PAD_2.0X1.5MM"))
    )
    (comp (ref "R1901")
      (value "47")
      (footprint "eagle-import:0603")
      (libsource (lib "eagle-import") (part "R0603_MET_"))
    )
    (comp (ref "R1902")
      (value "47")
      (footprint "eagle-import:0603")
      (libsource (lib "eagle-import") (part "R0603_MET_"))
    )
    (comp (ref "R1903")
      (value "10k")
      (footprint "eagle-import:0603")
      (libsource (lib "eagle-import") (part "R0603_MET_"))
    )
    (comp (ref "R1904")
      (value "10k")
      (footprint "eagle-import:0603")
      (libsource (lib "eagle-import") (part "R0603_MET_"))
    )
    (comp (ref "R1905")
      (value "47")
      (footprint "eagle-import:0603")
      (libsource (lib "eagle-import") (part "R0603_MET_"))
    )
    (comp (ref "R1906")
      (value "47")
      (footprint "eagle-import:0603")
      (libsource (lib "eagle-import") (part "R0603_MET_"))
    )
    (comp (ref "R1907")
      (value "10k")
      (footprint "eagle-import:0603")
      (libsource (lib "eagle-import") (part "R0603_MET_"))
    )
    (comp (ref "R1908")
      (value "10k")
      (footprint "eagle-import:0603")
      (libsource (lib "eagle-import") (part "R0603_MET_"))
    )
    (comp (ref "X1901")
      (value "43045-1000_MOLEX_10PIN")
      (footprint "eagle-import:X_TH_MOLEX_43045-1000_R_REV01")
      (fields (field (name "PDF-LOCAL") "file:///C:\\Eagle-Datasheet\\Steckverbindung\\430451000_Molex.pdf"))
      (libsource (lib "eagle-import") (part "43045-10?_MOLEX_10PIN00"))
    )
    (comp (ref "C801")
      (value "2.2µ")
      (footprint "eagle-import:0603")
      (libsource (lib "eagle-import") (part "C0603_X7R_"))
    )
    (comp (ref "C802")
      (value "100n")
      (footprint "eagle-import:0603")
      (libsource (lib "eagle-import") (part "C0603_X7R_"))
    )
    (comp (ref "C803")
      (value "100n")
      (footprint "eagle-import:0603")
      (libsource (lib "eagle-import") (part "C0603_X7R_"))
    )
    (comp (ref "C804")
      (value "100n")
      (footprint "eagle-import:0603")
      (libsource (lib "eagle-import") (part "C0603_X7R_"))
    )
    (comp (ref "C805")
      (value "100n")
      (footprint "eagle-import:0603")
      (libsource (lib "eagle-import") (part "C0603_X7R_"))
    )
    (comp (ref "C806")
      (value "100n")
      (footprint "eagle-import:0603")
      (libsource (lib "eagle-import") (part "C0603_X7R_"))
    )
    (comp (ref "C807")
      (value "100n")
      (footprint "eagle-import:0603")
      (libsource (lib "eagle-import") (part "C0603_X7R_"))
    )
    (comp (ref "D801")
      (value "PESD1CAN")
      (footprint "eagle-import:D_SMD_SOT23_(TO-236AB)_R_NXP_REV01")
      (fields (field (name "PDF-LOCAL") "file:///C:\\Eagle-Datasheet\\TVS\\PESD1CAN_NXP.pdf"))
      (libsource (lib "eagle-import") (part "PESD1CAN"))
    )
    (comp (ref "IC801")
      (value "KA7805ERTF")
      (footprint "eagle-import:IC_SMD_TO-252_(D-PAK)_R_FAIRCHILD_REV01")
      (fields
        (field (name "PDF-LOCAL") "file:///C:\\Eagle-Datasheet\\Spannungsregler\\KA7805E_Fairchild.pdf")
      )
      (libsource (lib "eagle-import") (part "KA78ERTF05"))
    )
    (comp (ref "IC802")
      (value "CPC1008N")
      (footprint "eagle-import:K_SMD_SOP-4_R_IXYS_REV01")
      (fields (field (name "PDF-LOCAL") "file:///C:\\Eagle-Datasheet\\Relais\\CPC1008N_IXYS.pdf"))
      (libsource (lib "eagle-import") (part "CPC1008N"))
    )
    (comp (ref "IC803")
      (value "TJA1052IT/1Y")
      (footprint "eagle-import:IC_SMD_SO16_(SOT162-1)_R_NXP_REV01")
      (fields (field (name "PDF-LOCAL") "file:///C:\\Eagle-Datasheet\\Schnittstellen-IC\\TJA1052I_NXP.pdf"))
      (libsource (lib "eagle-import") (part "TJA1052IT/1Y"))
    )
    (comp (ref "L801")
      (value "B82789C0513N002")
      (footprint "eagle-import:L_SMD_FILTER_HF_R_EPCOS_SIMDAD_1812_REV01")
      (fields (field (name "PDF-LOCAL") "file:///C:\\Eagle-Datasheet\\Induktivitaet\\B82789C0_EPCOS.pdf"))
      (libsource (lib "eagle-import") (part "B82789C0513N002"))
    )
    (comp (ref "LSP801")
      (value "PAD_2.0X1.5MM")
      (footprint "eagle-import:PAD2.0X1.5MM")
      (libsource (lib "eagle-import") (part "PAD_2.0X1.5MM"))
    )
    (comp (ref "LSP802")
      (value "PAD_2.0X1.5MM")
      (footprint "eagle-import:PAD2.0X1.5MM")
      (libsource (lib "eagle-import") (part "PAD_2.0X1.5MM"))
    )
    (comp (ref "LSP803")
      (value "PAD_2.0X1.5MM")
      (footprint "eagle-import:PAD2.0X1.5MM")
      (libsource (lib "eagle-import") (part "PAD_2.0X1.5MM"))
    )
    (comp (ref "LSP804")
      (value "PAD_2.0X1.5MM")
      (footprint "eagle-import:PAD2.0X1.5MM")
      (libsource (lib "eagle-import") (part "PAD_2.0X1.5MM"))
    )
    (comp (ref "LSP805")
      (value "PAD_2.0X1.5MM")
      (footprint "eagle-import:PAD2.0X1.5MM")
      (libsource (lib "eagle-import") (part "PAD_2.0X1.5MM"))
    )
    (comp (ref "LSP806")
      (value "PAD_2.0X1.5MM")
      (footprint "eagle-import:PAD2.0X1.5MM")
      (libsource (lib "eagle-import") (part "PAD_2.0X1.5MM"))
    )
    (comp (ref "LSP807")
      (value "PAD_2.0X1.5MM")
      (footprint "eagle-import:PAD2.0X1.5MM")
      (libsource (lib "eagle-import") (part "PAD_2.0X1.5MM"))
    )
    (comp (ref "R801")
      (value "62R")
      (footprint "eagle-import:0603")
      (libsource (lib "eagle-import") (part "R0603_CARB_"))
    )
    (comp (ref "R802")
      (value "62R")
      (footprint "eagle-import:0603")
      (libsource (lib "eagle-import") (part "R0603_CARB_"))
    )
    (comp (ref "R803")
      (value "10k")
      (footprint "eagle-import:0603")
      (libsource (lib "eagle-import") (part "R0603_CARB_"))
    )
    (comp (ref "R804")
      (value "430")
      (footprint "eagle-import:0603")
      (libsource (lib "eagle-import") (part "R0603_CARB_"))
    )
    (comp (ref "R805")
      (value "10k")
      (footprint "eagle-import:0603")
      (libsource (lib "eagle-import") (part "R0603_CARB_"))
    )
    (comp (ref "R806")
      (value "10")
      (footprint "eagle-import:0603")
      (libsource (lib "eagle-import") (part "R0603_CARB_"))
    )
    (comp (ref "T801")
      (value "IRLML0100TRPBF")
      (footprint "eagle-import:V_SMD_SOT-23_(TO-236AB)_R_IR_REV01")
      (fields (field (name "PDF-LOCAL") "file:///C:\\Eagle-Datasheet\\Transistoren\\IRLML0100PBF-1_IR.pdf"))
      (libsource (lib "eagle-import") (part "IR?LML0100TRPBF"))
    )
    (comp (ref "X801")
      (value "43045-0400_MOLEX_4PIN")
      (footprint "eagle-import:X_TH_MOLEX_43045-0400_R_REV01")
      (fields (field (name "PDF-LOCAL") "file:///C:\\Eagle-Datasheet\\Steckverbindung\\430450400_Molex.pdf"))
      (libsource (lib "eagle-import") (part "43045-04?_MOLEX_4PIN00"))
    )
    (comp (ref "D2001")
      (value "DIODE-DO214BA")
      (footprint "eagle-import:DO214BA")
      (libsource (lib "eagle-import") (part "DIODE-DO214BA"))
    )
    (comp (ref "D2002")
      (value "DIODE-DO214BA")
      (footprint "eagle-import:DO214BA")
      (libsource (lib "eagle-import") (part "DIODE-DO214BA"))
    )
    (comp (ref "D2003")
      (value "DIODE-DO214BA")
      (footprint "eagle-import:DO214BA")
      (libsource (lib "eagle-import") (part "DIODE-DO214BA"))
    )
    (comp (ref "D2004")
      (value "DIODE-DO214BA")
      (footprint "eagle-import:DO214BA")
      (libsource (lib "eagle-import") (part "DIODE-DO214BA"))
    )
    (comp (ref "D2005")
      (value "DIODE-DO214BA")
      (footprint "eagle-import:DO214BA")
      (libsource (lib "eagle-import") (part "DIODE-DO214BA"))
    )
    (comp (ref "D2006")
      (value "DIODE-DO214BA")
      (footprint "eagle-import:DO214BA")
      (libsource (lib "eagle-import") (part "DIODE-DO214BA"))
    )
    (comp (ref "IC2001")
      (value "AQV25G2S")
      (footprint "eagle-import:SOP06")
      (libsource (lib "eagle-import") (part "AQV25G2S"))
    )
    (comp (ref "IC2002")
      (value "AQV25G2S")
      (footprint "eagle-import:SOP06")
      (libsource (lib "eagle-import") (part "AQV25G2S"))
    )
    (comp (ref "IC2003")
      (value "AQV25G2S")
      (footprint "eagle-import:SOP06")
      (libsource (lib "eagle-import") (part "AQV25G2S"))
    )
    (comp (ref "IC2004")
      (value "AQV25G2S")
      (footprint "eagle-import:SOP06")
      (libsource (lib "eagle-import") (part "AQV25G2S"))
    )
    (comp (ref "IC2005")
      (value "AQV25G2S")
      (footprint "eagle-import:SOP06")
      (libsource (lib "eagle-import") (part "AQV25G2S"))
    )
    (comp (ref "IC2006")
      (value "AQV25G2S")
      (footprint "eagle-import:SOP06")
      (libsource (lib "eagle-import") (part "AQV25G2S"))
    )
    (comp (ref "LSP2001")
      (value "PAD_2.0X1.5MM")
      (footprint "eagle-import:PAD2.0X1.5MM")
      (libsource (lib "eagle-import") (part "PAD_2.0X1.5MM"))
    )
    (comp (ref "LSP2002")
      (value "PAD_2.0X1.5MM")
      (footprint "eagle-import:PAD2.0X1.5MM")
      (libsource (lib "eagle-import") (part "PAD_2.0X1.5MM"))
    )
    (comp (ref "LSP2003")
      (value "PAD_2.0X1.5MM")
      (footprint "eagle-import:PAD2.0X1.5MM")
      (libsource (lib "eagle-import") (part "PAD_2.0X1.5MM"))
    )
    (comp (ref "LSP2004")
      (value "PAD_2.0X1.5MM")
      (footprint "eagle-import:PAD2.0X1.5MM")
      (libsource (lib "eagle-import") (part "PAD_2.0X1.5MM"))
    )
    (comp (ref "LSP2005")
      (value "PAD_2.0X1.5MM")
      (footprint "eagle-import:PAD2.0X1.5MM")
      (libsource (lib "eagle-import") (part "PAD_2.0X1.5MM"))
    )
    (comp (ref "LSP2006")
      (value "PAD_2.0X1.5MM")
      (footprint "eagle-import:PAD2.0X1.5MM")
      (libsource (lib "eagle-import") (part "PAD_2.0X1.5MM"))
    )
    (comp (ref "R2001")
      (value "10")
      (footprint "eagle-import:0603")
      (libsource (lib "eagle-import") (part "R0603_MET_"))
    )
    (comp (ref "R2002")
      (value "10")
      (footprint "eagle-import:0603")
      (libsource (lib "eagle-import") (part "R0603_MET_"))
    )
    (comp (ref "R2003")
      (value "10k")
      (footprint "eagle-import:0603")
      (libsource (lib "eagle-import") (part "R0603_MET_"))
    )
    (comp (ref "R2004")
      (value "10k")
      (footprint "eagle-import:0603")
      (libsource (lib "eagle-import") (part "R0603_MET_"))
    )
    (comp (ref "R2005")
      (value "430")
      (footprint "eagle-import:0603")
      (libsource (lib "eagle-import") (part "R0603_MET_"))
    )
    (comp (ref "R2006")
      (value "430")
      (footprint "eagle-import:0603")
      (libsource (lib "eagle-import") (part "R0603_MET_"))
    )
    (comp (ref "R2007")
      (value "10")
      (footprint "eagle-import:0603")
      (libsource (lib "eagle-import") (part "R0603_MET_"))
    )
    (comp (ref "R2008")
      (value "10")
      (footprint "eagle-import:0603")
      (libsource (lib "eagle-import") (part "R0603_MET_"))
    )
    (comp (ref "R2009")
      (value "10k")
      (footprint "eagle-import:0603")
      (libsource (lib "eagle-import") (part "R0603_MET_"))
    )
    (comp (ref "R2010")
      (value "10k")
      (footprint "eagle-import:0603")
      (libsource (lib "eagle-import") (part "R0603_MET_"))
    )
    (comp (ref "R2011")
      (value "430")
      (footprint "eagle-import:0603")
      (libsource (lib "eagle-import") (part "R0603_MET_"))
    )
    (comp (ref "R2012")
      (value "430")
      (footprint "eagle-import:0603")
      (libsource (lib "eagle-import") (part "R0603_MET_"))
    )
    (comp (ref "R2013")
      (value "10")
      (footprint "eagle-import:0603")
      (libsource (lib "eagle-import") (part "R0603_MET_"))
    )
    (comp (ref "R2014")
      (value "10")
      (footprint "eagle-import:0603")
      (libsource (lib "eagle-import") (part "R0603_MET_"))
    )
    (comp (ref "R2015")
      (value "10k")
      (footprint "eagle-import:0603")
      (libsource (lib "eagle-import") (part "R0603_MET_"))
    )
    (comp (ref "R2016")
      (value "10k")
      (footprint "eagle-import:0603")
      (libsource (lib "eagle-import") (part "R0603_MET_"))
    )
    (comp (ref "R2017")
      (value "430")
      (footprint "eagle-import:0603")
      (libsource (lib "eagle-import") (part "R0603_MET_"))
    )
    (comp (ref "R2018")
      (value "430")
      (footprint "eagle-import:0603")
      (libsource (lib "eagle-import") (part "R0603_MET_"))
    )
    (comp (ref "T2001")
      (value "IRLML0100TRPBF")
      (footprint "eagle-import:V_SMD_SOT-23_(TO-236AB)_R_IR_REV01")
      (fields (field (name "PDF-LOCAL") "file:///C:\\Eagle-Datasheet\\Transistoren\\IRLML0100PBF-1_IR.pdf"))
      (libsource (lib "eagle-import") (part "IR?LML0100TRPBF"))
    )
    (comp (ref "T2002")
      (value "IRLML0100TRPBF")
      (footprint "eagle-import:V_SMD_SOT-23_(TO-236AB)_R_IR_REV01")
      (fields (field (name "PDF-LOCAL") "file:///C:\\Eagle-Datasheet\\Transistoren\\IRLML0100PBF-1_IR.pdf"))
      (libsource (lib "eagle-import") (part "IR?LML0100TRPBF"))
    )
    (comp (ref "T2003")
      (value "IRLML0100TRPBF")
      (footprint "eagle-import:V_SMD_SOT-23_(TO-236AB)_R_IR_REV01")
      (fields (field (name "PDF-LOCAL") "file:///C:\\Eagle-Datasheet\\Transistoren\\IRLML0100PBF-1_IR.pdf"))
      (libsource (lib "eagle-import") (part "IR?LML0100TRPBF"))
    )
    (comp (ref "T2004")
      (value "IRLML0100TRPBF")
      (footprint "eagle-import:V_SMD_SOT-23_(TO-236AB)_R_IR_REV01")
      (fields (field (name "PDF-LOCAL") "file:///C:\\Eagle-Datasheet\\Transistoren\\IRLML0100PBF-1_IR.pdf"))
      (libsource (lib "eagle-import") (part "IR?LML0100TRPBF"))
    )
    (comp (ref "T2005")
      (value "IRLML0100TRPBF")
      (footprint "eagle-import:V_SMD_SOT-23_(TO-236AB)_R_IR_REV01")
      (fields (field (name "PDF-LOCAL") "file:///C:\\Eagle-Datasheet\\Transistoren\\IRLML0100PBF-1_IR.pdf"))
      (libsource (lib "eagle-import") (part "IR?LML0100TRPBF"))
    )
    (comp (ref "T2006")
      (value "IRLML0100TRPBF")
      (footprint "eagle-import:V_SMD_SOT-23_(TO-236AB)_R_IR_REV01")
      (fields (field (name "PDF-LOCAL") "file:///C:\\Eagle-Datasheet\\Transistoren\\IRLML0100PBF-1_IR.pdf"))
      (libsource (lib "eagle-import") (part "IR?LML0100TRPBF"))
    )
    (comp (ref "X2001")
      (value "43045-1200_MOLEX_12PIN")
      (footprint "eagle-import:X_TH_MOLEX_43045-1200_R_REV01")
      (fields (field (name "PDF-LOCAL") "file:///C:\\Eagle-Datasheet\\Steckverbindung\\430451200_Molex.pdf"))
      (libsource (lib "eagle-import") (part "43045-12?_MOLEX_12PIN00"))
    )
    (comp (ref "LSP901")
      (value "PAD_2.0X1.5MM")
      (footprint "eagle-import:PAD2.0X1.5MM")
      (libsource (lib "eagle-import") (part "PAD_2.0X1.5MM"))
    )
    (comp (ref "R901")
      (value "10k")
      (footprint "eagle-import:0603")
      (libsource (lib "eagle-import") (part "R0603_MET_"))
    )
    (comp (ref "R902")
      (value "10")
      (footprint "eagle-import:0603")
      (libsource (lib "eagle-import") (part "R0603_MET_"))
    )
    (comp (ref "SV901")
      (value "MA04-2")
      (footprint "eagle-import:MA04-2")
      (libsource (lib "eagle-import") (part "MA04-2"))
    )
    (comp (ref "T901")
      (value "BUK964R8-60E")
      (footprint "eagle-import:V_SMD_TO-263_(D²PAK)_R_NXP_REV01")
      (fields (field (name "PDF-LOCAL") "file:///C:\\Eagle-Datasheet\\Transistoren\\BUK964R8-60E_NXP.pdf"))
      (libsource (lib "eagle-import") (part "BUK?964R8-60E"))
    )
    (comp (ref "C1501")
      (value "100n")
      (footprint "eagle-import:0603")
      (libsource (lib "eagle-import") (part "C0603_NP0_"))
    )
    (comp (ref "C1502")
      (value "1µ")
      (footprint "eagle-import:0603")
      (libsource (lib "eagle-import") (part "C0603_NP0_"))
    )
    (comp (ref "L1501")
      (value "22u")
      (footprint "eagle-import:0805")
      (libsource (lib "eagle-import") (part "L0805"))
    )
    (comp (ref "LSP1501")
      (value "PAD_2.0X1.5MM")
      (footprint "eagle-import:PAD2.0X1.5MM")
      (libsource (lib "eagle-import") (part "PAD_2.0X1.5MM"))
    )
    (comp (ref "LSP1502")
      (value "PAD_2.0X1.5MM")
      (footprint "eagle-import:PAD2.0X1.5MM")
      (libsource (lib "eagle-import") (part "PAD_2.0X1.5MM"))
    )
    (comp (ref "LSP1503")
      (value "PAD_2.0X1.5MM")
      (footprint "eagle-import:PAD2.0X1.5MM")
      (libsource (lib "eagle-import") (part "PAD_2.0X1.5MM"))
    )
    (comp (ref "LSP1504")
      (value "PAD_2.0X1.5MM")
      (footprint "eagle-import:PAD2.0X1.5MM")
      (libsource (lib "eagle-import") (part "PAD_2.0X1.5MM"))
    )
    (comp (ref "LSP1505")
      (value "PAD_2.0X1.5MM")
      (footprint "eagle-import:PAD2.0X1.5MM")
      (libsource (lib "eagle-import") (part "PAD_2.0X1.5MM"))
    )
    (comp (ref "R1501")
      (value "47k")
      (footprint "eagle-import:0603")
      (libsource (lib "eagle-import") (part "R0603_MET_"))
    )
    (comp (ref "R1502")
      (value "10k")
      (footprint "eagle-import:0603")
      (libsource (lib "eagle-import") (part "R0603_MET_"))
    )
    (comp (ref "R1503")
      (value "10k")
      (footprint "eagle-import:0603")
      (libsource (lib "eagle-import") (part "R0603_MET_"))
    )
    (comp (ref "R1504")
      (value "10k")
      (footprint "eagle-import:0603")
      (libsource (lib "eagle-import") (part "R0603_MET_"))
    )
    (comp (ref "R1505")
      (value "10k")
      (footprint "eagle-import:0603")
      (libsource (lib "eagle-import") (part "R0603_MET_"))
    )
    (comp (ref "R1506")
      (value "10k")
      (footprint "eagle-import:0603")
      (libsource (lib "eagle-import") (part "R0603_MET_"))
    )
    (comp (ref "R1507")
      (value "10k")
      (footprint "eagle-import:0603")
      (libsource (lib "eagle-import") (part "R0603_MET_"))
    )
    (comp (ref "SLOT1501")
      (value "MICRO_SD")
      (footprint "eagle-import:X_SMD_MICRO-SD-4735-21001_R_MOLEX_REV01")
      (fields
        (field (name "PDF-LOCAL") "file:///C:\\Eagle-Datasheet\\Steckverbindung\\473521001_SD_Molex.pdf")
      )
      (libsource (lib "eagle-import") (part "MICRO_SD"))
    )
    (comp (ref "T1501")
      (value "BSS84P")
      (footprint "eagle-import:V_SMD_SOT23_(TO-236AB)_R_INFINEON_REV01")
      (fields (field (name "PDF-LOCAL") "file:///C:\\Eagle-Datasheet\\Transistoren\\BSS84P_Infineon.pdf"))
      (libsource (lib "eagle-import") (part "BSS84P"))
    )
    (comp (ref "JP2201")
      (value "PINHD-2X12")
      (footprint "eagle-import:2X12")
      (libsource (lib "eagle-import") (part "PINHD-2X12"))
    )
    (comp (ref "JP2202")
      (value "PINHD-2X12")
      (footprint "eagle-import:2X12")
      (libsource (lib "eagle-import") (part "PINHD-2X12"))
    )
    (comp (ref "X1201")
      (value "43045-0400_MOLEX_4PIN")
      (footprint "eagle-import:X_TH_MOLEX_43045-0400_R_REV01")
      (fields (field (name "PDF-LOCAL") "file:///C:\\Eagle-Datasheet\\Steckverbindung\\430450400_Molex.pdf"))
      (libsource (lib "eagle-import") (part "43045-04?_MOLEX_4PIN00"))
    )
    (comp (ref "X1202")
      (value "43045-0400_MOLEX_4PIN")
      (footprint "eagle-import:X_TH_MOLEX_43045-0400_R_REV01")
      (fields (field (name "PDF-LOCAL") "file:///C:\\Eagle-Datasheet\\Steckverbindung\\430450400_Molex.pdf"))
      (libsource (lib "eagle-import") (part "43045-04?_MOLEX_4PIN00"))
    )
    (comp (ref "X1203")
      (value "43045-0400_MOLEX_4PIN")
      (footprint "eagle-import:X_TH_MOLEX_43045-0400_R_REV01")
      (fields (field (name "PDF-LOCAL") "file:///C:\\Eagle-Datasheet\\Steckverbindung\\430450400_Molex.pdf"))
      (libsource (lib "eagle-import") (part "43045-04?_MOLEX_4PIN00"))
    )
    (comp (ref "LSP2101")
      (value "PAD_2.0X1.5MM")
      (footprint "eagle-import:PAD2.0X1.5MM")
      (libsource (lib "eagle-import") (part "PAD_2.0X1.5MM"))
    )
    (comp (ref "LSP2102")
      (value "PAD_2.0X1.5MM")
      (footprint "eagle-import:PAD2.0X1.5MM")
      (libsource (lib "eagle-import") (part "PAD_2.0X1.5MM"))
    )
    (comp (ref "SV2101")
      (value "MA04-2")
      (footprint "eagle-import:MA04-2")
      (libsource (lib "eagle-import") (part "MA04-2"))
    )
    (comp (ref "D1001")
      (value "DIODE-DO214BA")
      (footprint "eagle-import:DO214BA")
      (libsource (lib "eagle-import") (part "DIODE-DO214BA"))
    )
    (comp (ref "D1002")
      (value "DIODE-DO214BA")
      (footprint "eagle-import:DO214BA")
      (libsource (lib "eagle-import") (part "DIODE-DO214BA"))
    )
    (comp (ref "D1003")
      (value "DIODE-DO214BA")
      (footprint "eagle-import:DO214BA")
      (libsource (lib "eagle-import") (part "DIODE-DO214BA"))
    )
    (comp (ref "F1001")
      (value "630MA_UMT")
      (footprint "eagle-import:F_SMD_11,00MMX3,00MMX3,00MM_(UMT)_R_SCHURTER_REV01")
      (fields (field (name "PDF-LOCAL") "file:///C:\\Eagle-Datasheet\\Sicherungen\\UMT_250_Schurter.pdf"))
      (libsource (lib "eagle-import") (part "_UMT630MA"))
    )
    (comp (ref "F1002")
      (value "630MA_UMT")
      (footprint "eagle-import:F_SMD_11,00MMX3,00MMX3,00MM_(UMT)_R_SCHURTER_REV01")
      (fields (field (name "PDF-LOCAL") "file:///C:\\Eagle-Datasheet\\Sicherungen\\UMT_250_Schurter.pdf"))
      (libsource (lib "eagle-import") (part "_UMT630MA"))
    )
    (comp (ref "F1003")
      (value "630MA_UMT")
      (footprint "eagle-import:F_SMD_11,00MMX3,00MMX3,00MM_(UMT)_R_SCHURTER_REV01")
      (fields (field (name "PDF-LOCAL") "file:///C:\\Eagle-Datasheet\\Sicherungen\\UMT_250_Schurter.pdf"))
      (libsource (lib "eagle-import") (part "_UMT630MA"))
    )
    (comp (ref "IC1001")
      (value "AQV252G2S")
      (footprint "eagle-import:K_SMD_SOP-6_R_PANASONIC_REV01")
      (fields (field (name "PDF-LOCAL") "file:///C:\\Eagle-Datasheet\\Relais\\AQV252G2_Panasonic.pdf"))
      (libsource (lib "eagle-import") (part "AQV25?S2G2"))
    )
    (comp (ref "IC1002")
      (value "AQV252G2S")
      (footprint "eagle-import:K_SMD_SOP-6_R_PANASONIC_REV01")
      (fields (field (name "PDF-LOCAL") "file:///C:\\Eagle-Datasheet\\Relais\\AQV252G2_Panasonic.pdf"))
      (libsource (lib "eagle-import") (part "AQV25?S2G2"))
    )
    (comp (ref "IC1003")
      (value "AQV252G2S")
      (footprint "eagle-import:K_SMD_SOP-6_R_PANASONIC_REV01")
      (fields (field (name "PDF-LOCAL") "file:///C:\\Eagle-Datasheet\\Relais\\AQV252G2_Panasonic.pdf"))
      (libsource (lib "eagle-import") (part "AQV25?S2G2"))
    )
    (comp (ref "LSP1001")
      (value "PAD_2.0X1.5MM")
      (footprint "eagle-import:PAD2.0X1.5MM")
      (libsource (lib "eagle-import") (part "PAD_2.0X1.5MM"))
    )
    (comp (ref "LSP1002")
      (value "PAD_2.0X1.5MM")
      (footprint "eagle-import:PAD2.0X1.5MM")
      (libsource (lib "eagle-import") (part "PAD_2.0X1.5MM"))
    )
    (comp (ref "LSP1003")
      (value "PAD_2.0X1.5MM")
      (footprint "eagle-import:PAD2.0X1.5MM")
      (libsource (lib "eagle-import") (part "PAD_2.0X1.5MM"))
    )
    (comp (ref "R1001")
      (value "10")
      (footprint "eagle-import:0603")
      (libsource (lib "eagle-import") (part "R0603_MET_"))
    )
    (comp (ref "R1002")
      (value "10k")
      (footprint "eagle-import:0603")
      (libsource (lib "eagle-import") (part "R0603_MET_"))
    )
    (comp (ref "R1003")
      (value "430")
      (footprint "eagle-import:0603")
      (libsource (lib "eagle-import") (part "R0603_MET_"))
    )
    (comp (ref "R1004")
      (value "10")
      (footprint "eagle-import:0603")
      (libsource (lib "eagle-import") (part "R0603_MET_"))
    )
    (comp (ref "R1005")
      (value "10k")
      (footprint "eagle-import:0603")
      (libsource (lib "eagle-import") (part "R0603_MET_"))
    )
    (comp (ref "R1006")
      (value "430")
      (footprint "eagle-import:0603")
      (libsource (lib "eagle-import") (part "R0603_MET_"))
    )
    (comp (ref "R1007")
      (value "10")
      (footprint "eagle-import:0603")
      (libsource (lib "eagle-import") (part "R0603_MET_"))
    )
    (comp (ref "R1008")
      (value "10k")
      (footprint "eagle-import:0603")
      (libsource (lib "eagle-import") (part "R0603_MET_"))
    )
    (comp (ref "R1009")
      (value "430")
      (footprint "eagle-import:0603")
      (libsource (lib "eagle-import") (part "R0603_MET_"))
    )
    (comp (ref "T1001")
      (value "IRLML0100TRPBF")
      (footprint "eagle-import:V_SMD_SOT-23_(TO-236AB)_R_IR_REV01")
      (fields (field (name "PDF-LOCAL") "file:///C:\\Eagle-Datasheet\\Transistoren\\IRLML0100PBF-1_IR.pdf"))
      (libsource (lib "eagle-import") (part "IR?LML0100TRPBF"))
    )
    (comp (ref "T1002")
      (value "IRLML0100TRPBF")
      (footprint "eagle-import:V_SMD_SOT-23_(TO-236AB)_R_IR_REV01")
      (fields (field (name "PDF-LOCAL") "file:///C:\\Eagle-Datasheet\\Transistoren\\IRLML0100PBF-1_IR.pdf"))
      (libsource (lib "eagle-import") (part "IR?LML0100TRPBF"))
    )
    (comp (ref "T1003")
      (value "IRLML0100TRPBF")
      (footprint "eagle-import:V_SMD_SOT-23_(TO-236AB)_R_IR_REV01")
      (fields (field (name "PDF-LOCAL") "file:///C:\\Eagle-Datasheet\\Transistoren\\IRLML0100PBF-1_IR.pdf"))
      (libsource (lib "eagle-import") (part "IR?LML0100TRPBF"))
    )
  )
  (nets
    (net (code "1") (name "+3.3V_0") (class "Default")
      (node (ref "C1105") (pin "1") (pinfunction "1_1") (pintype "passive"))
      (node (ref "C1106") (pin "1") (pinfunction "1_1") (pintype "passive"))
      (node (ref "C1306") (pin "1") (pinfunction "1_1") (pintype "passive"))
      (node (ref "C1703") (pin "1") (pinfunction "1_1") (pintype "passive"))
      (node (ref "C1704") (pin "1") (pinfunction "1_1") (pintype "passive"))
      (node (ref "C1905") (pin "1") (pinfunction "1_1") (pintype "passive"))
      (node (ref "C1907") (pin "1") (pinfunction "1_1") (pintype "passive"))
      (node (ref "C807") (pin "2") (pinfunction "2_2") (pintype "passive"))
      (node (ref "IC1001") (pin "1") (pinfunction "1_1") (pintype "bidirectional"))
      (node (ref "IC1002") (pin "1") (pinfunction "1_1") (pintype "bidirectional"))
      (node (ref "IC1003") (pin "1") (pinfunction "1_1") (pintype "bidirectional"))
      (node (ref "IC1102") (pin "10") (pinfunction "VE2_10") (pintype "bidirectional"))
      (node (ref "IC1102") (pin "16") (pinfunction "VDD2_16") (pintype "power_in"))
      (node (ref "IC1303") (pin "1") (pinfunction "VDD1_1") (pintype "power_in"))
      (node (ref "IC1303") (pin "7") (pinfunction "VE1_7") (pintype "bidirectional"))
      (node (ref "IC1701") (pin "3") (pinfunction "ENABLE_3") (pintype "bidirectional"))
      (node (ref "IC1701") (pin "4") (pinfunction "VIN_4") (pintype "input"))
      (node (ref "IC1902") (pin "10") (pinfunction "VE2_10") (pintype "bidirectional"))
      (node (ref "IC1902") (pin "16") (pinfunction "VDD2_16") (pintype "power_in"))
      (node (ref "IC1903") (pin "10") (pinfunction "VE2_10") (pintype "bidirectional"))
      (node (ref "IC1903") (pin "16") (pinfunction "VDD2_16") (pintype "power_in"))
      (node (ref "IC2001") (pin "1") (pinfunction "A_1") (pintype "passive"))
      (node (ref "IC2002") (pin "1") (pinfunction "A_1") (pintype "passive"))
      (node (ref "IC2003") (pin "1") (pinfunction "A_1") (pintype "passive"))
      (node (ref "IC2004") (pin "1") (pinfunction "A_1") (pintype "passive"))
      (node (ref "IC2005") (pin "1") (pinfunction "A_1") (pintype "passive"))
      (node (ref "IC2006") (pin "1") (pinfunction "A_1") (pintype "passive"))
      (node (ref "IC803") (pin "1") (pinfunction "VDD_1") (pintype "power_in"))
      (node (ref "JP2201") (pin "1") (pinfunction "1_1") (pintype "passive"))
      (node (ref "JP2201") (pin "3") (pinfunction "3_3") (pintype "passive"))
      (node (ref "JP2202") (pin "1") (pinfunction "1_1") (pintype "passive"))
      (node (ref "JP2202") (pin "3") (pinfunction "3_3") (pintype "passive"))
      (node (ref "LSP2101") (pin "P$1") (pinfunction "MP_P$1") (pintype "passive"))
      (node (ref "R1501") (pin "2") (pinfunction "2_2") (pintype "passive"))
      (node (ref "R804") (pin "1") (pinfunction "1_1") (pintype "passive"))
      (node (ref "SV2101") (pin "1") (pinfunction "1_1") (pintype "passive"))
      (node (ref "T1501") (pin "2") (pinfunction "S_2") (pintype "passive"))
    )
    (net (code "2") (name "+5.0V_0") (class "Default")
      (node (ref "SV2101") (pin "2") (pinfunction "2_2") (pintype "passive"))
    )
    (net (code "3") (name "ADC_MCU_0_CH_0") (class "Default")
      (node (ref "C1701") (pin "1") (pinfunction "1_1") (pintype "passive"))
      (node (ref "D1701") (pin "C") (pinfunction "C_C") (pintype "bidirectional"))
      (node (ref "JP2202") (pin "8") (pinfunction "8_8") (pintype "passive"))
      (node (ref "LSP1701") (pin "P$1") (pinfunction "MP_P$1") (pintype "passive"))
      (node (ref "R1701") (pin "2") (pinfunction "2_2") (pintype "passive"))
      (node (ref "R1702") (pin "1") (pinfunction "1_1") (pintype "passive"))
    )
    (net (code "4") (name "ADC_MCU_0_CH_1") (class "Default")
      (node (ref "C1705") (pin "1") (pinfunction "1_1") (pintype "passive"))
      (node (ref "D1703") (pin "C") (pinfunction "C_C") (pintype "bidirectional"))
      (node (ref "JP2202") (pin "7") (pinfunction "7_7") (pintype "passive"))
      (node (ref "LSP1704") (pin "P$1") (pinfunction "MP_P$1") (pintype "passive"))
      (node (ref "R1705") (pin "2") (pinfunction "2_2") (pintype "passive"))
      (node (ref "R1706") (pin "1") (pinfunction "1_1") (pintype "passive"))
    )
    (net (code "5") (name "ADC_MCU_0_CH_2") (class "Default")
      (node (ref "C1708") (pin "1") (pinfunction "1_1") (pintype "passive"))
      (node (ref "D1705") (pin "C") (pinfunction "C_C") (pintype "bidirectional"))
      (node (ref "JP2202") (pin "6") (pinfunction "6_6") (pintype "passive"))
      (node (ref "LSP1705") (pin "P$1") (pinfunction "MP_P$1") (pintype "passive"))
      (node (ref "R1709") (pin "2") (pinfunction "2_2") (pintype "passive"))
      (node (ref "R1710") (pin "1") (pinfunction "1_1") (pintype "passive"))
    )
    (net (code "6") (name "ADC_MCU_0_CH_3") (class "Default")
      (node (ref "C1702") (pin "1") (pinfunction "1_1") (pintype "passive"))
      (node (ref "D1702") (pin "C") (pinfunction "C_C") (pintype "bidirectional"))
      (node (ref "JP2202") (pin "5") (pinfunction "5_5") (pintype "passive"))
      (node (ref "LSP1702") (pin "P$1") (pinfunction "MP_P$1") (pintype "passive"))
      (node (ref "R1703") (pin "2") (pinfunction "2_2") (pintype "passive"))
      (node (ref "R1704") (pin "1") (pinfunction "1_1") (pintype "passive"))
    )
    (net (code "7") (name "ADC_MCU_0_CH_4") (class "Default")
      (node (ref "C1706") (pin "1") (pinfunction "1_1") (pintype "passive"))
      (node (ref "D1704") (pin "C") (pinfunction "C_C") (pintype "bidirectional"))
      (node (ref "JP2202") (pin "9") (pinfunction "9_9") (pintype "passive"))
      (node (ref "LSP1703") (pin "P$1") (pinfunction "MP_P$1") (pintype "passive"))
      (node (ref "R1707") (pin "2") (pinfunction "2_2") (pintype "passive"))
      (node (ref "R1708") (pin "1") (pinfunction "1_1") (pintype "passive"))
    )
    (net (code "8") (name "ANALOG_IN_CH_0") (class "Default")
      (node (ref "R1701") (pin "1") (pinfunction "1_1") (pintype "passive"))
      (node (ref "X1701") (pin "2") (pinfunction "2_2") (pintype "passive"))
    )
    (net (code "9") (name "ANALOG_IN_CH_1") (class "Default")
      (node (ref "R1705") (pin "1") (pinfunction "1_1") (pintype "passive"))
      (node (ref "X1701") (pin "4") (pinfunction "4_4") (pintype "passive"))
    )
    (net (code "10") (name "ANALOG_IN_CH_2") (class "Default")
      (node (ref "R1709") (pin "1") (pinfunction "1_1") (pintype "passive"))
      (node (ref "X1701") (pin "6") (pinfunction "6_6") (pintype "passive"))
    )
    (net (code "11") (name "ANALOG_IN_CH_3") (class "Default")
      (node (ref "R1703") (pin "1") (pinfunction "1_1") (pintype "passive"))
      (node (ref "X1701") (pin "8") (pinfunction "8_8") (pintype "passive"))
    )
    (net (code "12") (name "ANALOG_IN_CH_4") (class "Default")
      (node (ref "R1707") (pin "1") (pinfunction "1_1") (pintype "passive"))
      (node (ref "X1701") (pin "10") (pinfunction "10_10") (pintype "passive"))
    )
    (net (code "13") (name "CAN_1_H") (class "Default")
      (node (ref "D801") (pin "1") (pinfunction "1_1") (pintype "passive"))
      (node (ref "L801") (pin "2") (pinfunction "2_2") (pintype "passive"))
      (node (ref "LSP802") (pin "P$1") (pinfunction "MP_P$1") (pintype "passive"))
      (node (ref "X801") (pin "4") (pinfunction "4_4") (pintype "passive"))
    )
    (net (code "14") (name "CAN_1_L") (class "Default")
      (node (ref "D801") (pin "2") (pinfunction "2_2") (pintype "passive"))
      (node (ref "L801") (pin "1") (pinfunction "1_1") (pintype "passive"))
      (node (ref "LSP803") (pin "P$1") (pinfunction "MP_P$1") (pintype "passive"))
      (node (ref "X801") (pin "3") (pinfunction "3_3") (pintype "passive"))
    )
    (net (code "15") (name "CAN_1_RX") (class "Default")
      (node (ref "IC803") (pin "5") (pinfunction "RXD_5") (pintype "bidirectional"))
      (node (ref "JP2201") (pin "6") (pinfunction "6_6") (pintype "passive"))
      (node (ref "LSP806") (pin "P$1") (pinfunction "MP_P$1") (pintype "passive"))
    )
    (net (code "16") (name "CAN_1_TRANS_STANDBY_CONTROL") (class "Default")
      (node (ref "JP2201") (pin "5") (pinfunction "5_5") (pintype "passive"))
      (node (ref "R806") (pin "2") (pinfunction "2_2") (pintype "passive"))
    )
    (net (code "17") (name "CAN_1_TX") (class "Default")
      (node (ref "IC803") (pin "3") (pinfunction "TXD_3") (pintype "bidirectional"))
      (node (ref "JP2201") (pin "7") (pinfunction "7_7") (pintype "passive"))
      (node (ref "LSP805") (pin "P$1") (pinfunction "MP_P$1") (pintype "passive"))
    )
    (net (code "18") (name "CAN_TRANS_1_EXT_SUPPLY") (class "Default")
      (node (ref "C803") (pin "2") (pinfunction "2_2") (pintype "passive"))
      (node (ref "C805") (pin "2") (pinfunction "2_2") (pintype "passive"))
      (node (ref "C806") (pin "2") (pinfunction "2_2") (pintype "passive"))
      (node (ref "IC801") (pin "3") (pinfunction "OUT_3") (pintype "output"))
      (node (ref "IC803") (pin "11") (pinfunction "VDD_11") (pintype "power_in"))
      (node (ref "IC803") (pin "16") (pinfunction "VDD_16") (pintype "power_in"))
      (node (ref "R803") (pin "1") (pinfunction "1_1") (pintype "passive"))
    )
    (net (code "19") (name "CAN_TRANS_1_STANDBY") (class "Default")
      (node (ref "IC802") (pin "4") (pinfunction "4_4") (pintype "bidirectional"))
      (node (ref "IC803") (pin "14") (pinfunction "STB_14") (pintype "bidirectional"))
      (node (ref "LSP804") (pin "P$1") (pinfunction "MP_P$1") (pintype "passive"))
      (node (ref "R803") (pin "2") (pinfunction "2_2") (pintype "passive"))
    )
    (net (code "20") (name "CONTACTORS_COMMON_NEG") (class "Default")
      (node (ref "D1001") (pin "A") (pinfunction "A_A") (pintype "passive"))
      (node (ref "D1002") (pin "A") (pinfunction "A_A") (pintype "passive"))
      (node (ref "D1003") (pin "A") (pinfunction "A_A") (pintype "passive"))
      (node (ref "T901") (pin "2") (pinfunction "D_2") (pintype "passive"))
      (node (ref "X1201") (pin "4") (pinfunction "4_4") (pintype "passive"))
      (node (ref "X1202") (pin "4") (pinfunction "4_4") (pintype "passive"))
      (node (ref "X1203") (pin "4") (pinfunction "4_4") (pintype "passive"))
    )
    (net (code "21") (name "CONTACTOR_6_COIL_POS") (class "Default")
      (node (ref "D1001") (pin "C") (pinfunction "C_C") (pintype "passive"))
      (node (ref "IC1001") (pin "5") (pinfunction "5_5") (pintype "bidirectional"))
      (node (ref "X1201") (pin "3") (pinfunction "3_3") (pintype "passive"))
    )
    (net (code "22") (name "CONTACTOR_6_CONTROL") (class "Default")
      (node (ref "JP2201") (pin "18") (pinfunction "18_18") (pintype "passive"))
      (node (ref "LSP1001") (pin "P$1") (pinfunction "MP_P$1") (pintype "passive"))
      (node (ref "R1001") (pin "2") (pinfunction "2_2") (pintype "passive"))
    )
    (net (code "23") (name "CONTACTOR_6_FEEDBACK") (class "Default")
      (node (ref "IC1102") (pin "14") (pinfunction "VOA_14") (pintype "bidirectional"))
      (node (ref "JP2201") (pin "17") (pinfunction "17_17") (pintype "passive"))
      (node (ref "LSP1101") (pin "P$1") (pinfunction "MP_P$1") (pintype "passive"))
    )
    (net (code "24") (name "CONTACTOR_6_FEEDBACK_EXT") (class "Default")
      (node (ref "R1101") (pin "2") (pinfunction "2_2") (pintype "passive"))
      (node (ref "X1201") (pin "2") (pinfunction "2_2") (pintype "passive"))
    )
    (net (code "25") (name "CONTACTOR_7_COIL_POS") (class "Default")
      (node (ref "D1002") (pin "C") (pinfunction "C_C") (pintype "passive"))
      (node (ref "IC1002") (pin "5") (pinfunction "5_5") (pintype "bidirectional"))
      (node (ref "X1202") (pin "3") (pinfunction "3_3") (pintype "passive"))
    )
    (net (code "26") (name "CONTACTOR_7_CONTROL") (class "Default")
      (node (ref "JP2201") (pin "16") (pinfunction "16_16") (pintype "passive"))
      (node (ref "LSP1002") (pin "P$1") (pinfunction "MP_P$1") (pintype "passive"))
      (node (ref "R1004") (pin "2") (pinfunction "2_2") (pintype "passive"))
    )
    (net (code "27") (name "CONTACTOR_7_FEEDBACK") (class "Default")
      (node (ref "IC1102") (pin "13") (pinfunction "VOB_13") (pintype "bidirectional"))
      (node (ref "JP2201") (pin "15") (pinfunction "15_15") (pintype "passive"))
      (node (ref "LSP1103") (pin "P$1") (pinfunction "MP_P$1") (pintype "passive"))
    )
    (net (code "28") (name "CONTACTOR_7_FEEDBACK_EXT") (class "Default")
      (node (ref "R1102") (pin "2") (pinfunction "2_2") (pintype "passive"))
      (node (ref "X1202") (pin "2") (pinfunction "2_2") (pintype "passive"))
    )
    (net (code "29") (name "CONTACTOR_8_COIL_POS") (class "Default")
      (node (ref "D1003") (pin "C") (pinfunction "C_C") (pintype "passive"))
      (node (ref "IC1003") (pin "5") (pinfunction "5_5") (pintype "bidirectional"))
      (node (ref "X1203") (pin "3") (pinfunction "3_3") (pintype "passive"))
    )
    (net (code "30") (name "CONTACTOR_8_CONTROL") (class "Default")
      (node (ref "JP2202") (pin "10") (pinfunction "10_10") (pintype "passive"))
      (node (ref "LSP1003") (pin "P$1") (pinfunction "MP_P$1") (pintype "passive"))
      (node (ref "R1007") (pin "2") (pinfunction "2_2") (pintype "passive"))
    )
    (net (code "31") (name "CONTACTOR_8_FEEDBACK") (class "Default")
      (node (ref "IC1102") (pin "12") (pinfunction "VOC_12") (pintype "bidirectional"))
      (node (ref "JP2202") (pin "11") (pinfunction "11_11") (pintype "passive"))
      (node (ref "LSP1102") (pin "P$1") (pinfunction "MP_P$1") (pintype "passive"))
    )
    (net (code "32") (name "CONTACTOR_8_FEEDBACK_EXT") (class "Default")
      (node (ref "R1103") (pin "2") (pinfunction "2_2") (pintype "passive"))
      (node (ref "X1203") (pin "2") (pinfunction "2_2") (pintype "passive"))
    )
    (net (code "33") (name "CONTACTOR_FEEDBACK_SUPPLY_EXT") (class "Default")
      (node (ref "C1103") (pin "1") (pinfunction "1_1") (pintype "passive"))
      (node (ref "C1104") (pin "1") (pinfunction "1_1") (pintype "passive"))
      (node (ref "IC1101") (pin "1") (pinfunction "OUT_1") (pintype "output"))
      (node (ref "IC1102") (pin "1") (pinfunction "VDD1_1") (pintype "power_in"))
      (node (ref "R1104") (pin "2") (pinfunction "2_2") (pintype "passive"))
      (node (ref "R1105") (pin "2") (pinfunction "2_2") (pintype "passive"))
      (node (ref "R1106") (pin "2") (pinfunction "2_2") (pintype "passive"))
    )
    (net (code "34") (name "DATA_STORAGE_SPI_MISO") (class "Default")
      (node (ref "JP2201") (pin "21") (pinfunction "21_21") (pintype "passive"))
      (node (ref "LSP1505") (pin "P$1") (pinfunction "MP_P$1") (pintype "passive"))
      (node (ref "R1507") (pin "1") (pinfunction "1_1") (pintype "passive"))
      (node (ref "SLOT1501") (pin "7") (pinfunction "7_7") (pintype "passive"))
    )
    (net (code "35") (name "DATA_STORAGE_SPI_MOSI") (class "Default")
      (node (ref "JP2201") (pin "19") (pinfunction "19_19") (pintype "passive"))
      (node (ref "LSP1503") (pin "P$1") (pinfunction "MP_P$1") (pintype "passive"))
      (node (ref "R1504") (pin "1") (pinfunction "1_1") (pintype "passive"))
      (node (ref "SLOT1501") (pin "3") (pinfunction "3_3") (pintype "passive"))
    )
    (net (code "36") (name "DATA_STORAGE_SPI_SCK") (class "Default")
      (node (ref "JP2201") (pin "20") (pinfunction "20_20") (pintype "passive"))
      (node (ref "LSP1504") (pin "P$1") (pinfunction "MP_P$1") (pintype "passive"))
      (node (ref "R1505") (pin "2") (pinfunction "2_2") (pintype "passive"))
      (node (ref "SLOT1501") (pin "5") (pinfunction "5_5") (pintype "passive"))
    )
    (net (code "37") (name "DATA_STORAGE_SPI_SDCARD_NSS") (class "Default")
      (node (ref "JP2201") (pin "23") (pinfunction "23_23") (pintype "passive"))
      (node (ref "LSP1502") (pin "P$1") (pinfunction "MP_P$1") (pintype "passive"))
      (node (ref "R1506") (pin "1") (pinfunction "1_1") (pintype "passive"))
      (node (ref "SLOT1501") (pin "2") (pinfunction "2_2") (pintype "passive"))
    )
    (net (code "38") (name "GND_0") (class "Default")
      (node (ref "C1105") (pin "2") (pinfunction "2_2") (pintype "passive"))
      (node (ref "C1106") (pin "2") (pinfunction "2_2") (pintype "passive"))
      (node (ref "C1306") (pin "2") (pinfunction "2_2") (pintype "passive"))
      (node (ref "C1501") (pin "1") (pinfunction "1_1") (pintype "passive"))
      (node (ref "C1502") (pin "2") (pinfunction "2_2") (pintype "passive"))
      (node (ref "C1701") (pin "2") (pinfunction "2_2") (pintype "passive"))
      (node (ref "C1702") (pin "2") (pinfunction "2_2") (pintype "passive"))
      (node (ref "C1703") (pin "2") (pinfunction "2_2") (pintype "passive"))
      (node (ref "C1704") (pin "2") (pinfunction "2_2") (pintype "passive"))
      (node (ref "C1705") (pin "2") (pinfunction "2_2") (pintype "passive"))
      (node (ref "C1706") (pin "2") (pinfunction "2_2") (pintype "passive"))
      (node (ref "C1707") (pin "2") (pinfunction "2_2") (pintype "passive"))
      (node (ref "C1708") (pin "2") (pinfunction "2_2") (pintype "passive"))
      (node (ref "C1905") (pin "2") (pinfunction "2_2") (pintype "passive"))
      (node (ref "C1907") (pin "2") (pinfunction "2_2") (pintype "passive"))
      (node (ref "C807") (pin "1") (pinfunction "1_1") (pintype "passive"))
      (node (ref "D1701") (pin "A") (pinfunction "A_A") (pintype "bidirectional"))
      (node (ref "D1702") (pin "A") (pinfunction "A_A") (pintype "bidirectional"))
      (node (ref "D1703") (pin "A") (pinfunction "A_A") (pintype "bidirectional"))
      (node (ref "D1704") (pin "A") (pinfunction "A_A") (pintype "bidirectional"))
      (node (ref "D1705") (pin "A") (pinfunction "A_A") (pintype "bidirectional"))
      (node (ref "IC1102") (pin "15") (pinfunction "GND2_15") (pintype "power_in"))
      (node (ref "IC1102") (pin "9") (pinfunction "GND2_9") (pintype "power_in"))
      (node (ref "IC1303") (pin "2") (pinfunction "GND1_2") (pintype "power_in"))
      (node (ref "IC1303") (pin "8") (pinfunction "GND1_8") (pintype "power_in"))
      (node (ref "IC1701") (pin "1") (pinfunction "GND_FORCE_1") (pintype "power_in"))
      (node (ref "IC1701") (pin "2") (pinfunction "GND_SENSE_2") (pintype "power_in"))
      (node (ref "IC1902") (pin "15") (pinfunction "GND2_15") (pintype "power_in"))
      (node (ref "IC1902") (pin "9") (pinfunction "GND2_9") (pintype "power_in"))
      (node (ref "IC1903") (pin "15") (pinfunction "GND2_15") (pintype "power_in"))
      (node (ref "IC1903") (pin "9") (pinfunction "GND2_9") (pintype "power_in"))
      (node (ref "IC803") (pin "2") (pinfunction "GND_2") (pintype "power_in"))
      (node (ref "IC803") (pin "7") (pinfunction "GND_7") (pintype "power_in"))
      (node (ref "IC803") (pin "8") (pinfunction "GND_8") (pintype "power_in"))
      (node (ref "JP2201") (pin "2") (pinfunction "2_2") (pintype "passive"))
      (node (ref "JP2201") (pin "4") (pinfunction "4_4") (pintype "passive"))
      (node (ref "JP2202") (pin "2") (pinfunction "2_2") (pintype "passive"))
      (node (ref "JP2202") (pin "4") (pinfunction "4_4") (pintype "passive"))
      (node (ref "LSP2102") (pin "P$1") (pinfunction "MP_P$1") (pintype "passive"))
      (node (ref "R1002") (pin "1") (pinfunction "1_1") (pintype "passive"))
      (node (ref "R1005") (pin "1") (pinfunction "1_1") (pintype "passive"))
      (node (ref "R1008") (pin "1") (pinfunction "1_1") (pintype "passive"))
      (node (ref "R1505") (pin "1") (pinfunction "1_1") (pintype "passive"))
      (node (ref "R1702") (pin "2") (pinfunction "2_2") (pintype "passive"))
      (node (ref "R1704") (pin "2") (pinfunction "2_2") (pintype "passive"))
      (node (ref "R1706") (pin "2") (pinfunction "2_2") (pintype "passive"))
      (node (ref "R1708") (pin "2") (pinfunction "2_2") (pintype "passive"))
      (node (ref "R1710") (pin "2") (pinfunction "2_2") (pintype "passive"))
      (node (ref "R2003") (pin "1") (pinfunction "1_1") (pintype "passive"))
      (node (ref "R2004") (pin "1") (pinfunction "1_1") (pintype "passive"))
      (node (ref "R2009") (pin "1") (pinfunction "1_1") (pintype "passive"))
      (node (ref "R2010") (pin "1") (pinfunction "1_1") (pintype "passive"))
      (node (ref "R2015") (pin "1") (pinfunction "1_1") (pintype "passive"))
      (node (ref "R2016") (pin "1") (pinfunction "1_1") (pintype "passive"))
      (node (ref "R805") (pin "2") (pinfunction "2_2") (pintype "passive"))
      (node (ref "SLOT1501") (pin "6") (pinfunction "6_6") (pintype "passive"))
      (node (ref "SLOT1501") (pin "6_1") (pinfunction "9_6_1") (pintype "passive"))
      (node (ref "SLOT1501") (pin "SH1") (pinfunction "SH_SH1") (pintype "passive"))
      (node (ref "SLOT1501") (pin "SH2") (pinfunction "SH_SH2") (pintype "passive"))
      (node (ref "SLOT1501") (pin "SH3") (pinfunction "SH_SH3") (pintype "passive"))
      (node (ref "SLOT1501") (pin "SH5") (pinfunction "SH_SH5") (pintype "passive"))
      (node (ref "SV2101") (pin "5") (pinfunction "5_5") (pintype "passive"))
      (node (ref "SV2101") (pin "6") (pinfunction "6_6") (pintype "passive"))
      (node (ref "T1001") (pin "2") (pinfunction "S_2") (pintype "passive"))
      (node (ref "T1002") (pin "2") (pinfunction "S_2") (pintype "passive"))
      (node (ref "T1003") (pin "2") (pinfunction "S_2") (pintype "passive"))
      (node (ref "T2001") (pin "2") (pinfunction "S_2") (pintype "passive"))
      (node (ref "T2002") (pin "2") (pinfunction "S_2") (pintype "passive"))
      (node (ref "T2003") (pin "2") (pinfunction "S_2") (pintype "passive"))
      (node (ref "T2004") (pin "2") (pinfunction "S_2") (pintype "passive"))
      (node (ref "T2005") (pin "2") (pinfunction "S_2") (pintype "passive"))
      (node (ref "T2006") (pin "2") (pinfunction "S_2") (pintype "passive"))
      (node (ref "T801") (pin "2") (pinfunction "S_2") (pintype "passive"))
      (node (ref "X1701") (pin "11") (pinfunction "11_11") (pintype "passive"))
      (node (ref "X1701") (pin "12") (pinfunction "12_12") (pintype "passive"))
    )
    (net (code "39") (name "GND_EXT_0") (class "Default")
      (node (ref "C1101") (pin "2") (pinfunction "2_2") (pintype "passive"))
      (node (ref "C1102") (pin "2") (pinfunction "2_2") (pintype "passive"))
      (node (ref "C1103") (pin "2") (pinfunction "2_2") (pintype "passive"))
      (node (ref "C1104") (pin "2") (pinfunction "2_2") (pintype "passive"))
      (node (ref "C1901") (pin "2") (pinfunction "2_2") (pintype "passive"))
      (node (ref "C1902") (pin "2") (pinfunction "2_2") (pintype "passive"))
      (node (ref "C1903") (pin "2") (pinfunction "2_2") (pintype "passive"))
      (node (ref "C1904") (pin "2") (pinfunction "2_2") (pintype "passive"))
      (node (ref "C1906") (pin "2") (pinfunction "2_2") (pintype "passive"))
      (node (ref "D1101") (pin "A") (pinfunction "A_A") (pintype "passive"))
      (node (ref "D1102") (pin "A") (pinfunction "A_A") (pintype "passive"))
      (node (ref "D1103") (pin "A") (pinfunction "A_A") (pintype "passive"))
      (node (ref "D1901") (pin "A") (pinfunction "A_A") (pintype "passive"))
      (node (ref "D1902") (pin "A") (pinfunction "A_A") (pintype "passive"))
      (node (ref "D1903") (pin "A") (pinfunction "A_A") (pintype "passive"))
      (node (ref "D1904") (pin "A") (pinfunction "A_A") (pintype "passive"))
      (node (ref "IC1101") (pin "2") (pinfunction "COM_2") (pintype "power_in"))
      (node (ref "IC1102") (pin "2") (pinfunction "GND1_2") (pintype "power_in"))
      (node (ref "IC1102") (pin "8") (pinfunction "GND1_8") (pintype "power_in"))
      (node (ref "IC1901") (pin "2") (pinfunction "COM_2") (pintype "power_in"))
      (node (ref "IC1902") (pin "2") (pinfunction "GND1_2") (pintype "power_in"))
      (node (ref "IC1902") (pin "8") (pinfunction "GND1_8") (pintype "power_in"))
      (node (ref "IC1903") (pin "2") (pinfunction "GND1_2") (pintype "power_in"))
      (node (ref "IC1903") (pin "8") (pinfunction "GND1_8") (pintype "power_in"))
      (node (ref "R1903") (pin "1") (pinfunction "1_1") (pintype "passive"))
      (node (ref "R1904") (pin "1") (pinfunction "1_1") (pintype "passive"))
      (node (ref "R1907") (pin "1") (pinfunction "1_1") (pintype "passive"))
      (node (ref "R1908") (pin "1") (pinfunction "1_1") (pintype "passive"))
      (node (ref "SV901") (pin "2") (pinfunction "2_2") (pintype "passive"))
      (node (ref "X1201") (pin "1") (pinfunction "1_1") (pintype "passive"))
      (node (ref "X1202") (pin "1") (pinfunction "1_1") (pintype "passive"))
      (node (ref "X1203") (pin "1") (pinfunction "1_1") (pintype "passive"))
      (node (ref "X1901") (pin "10") (pinfunction "10_10") (pintype "passive"))
      (node (ref "X1901") (pin "9") (pinfunction "9_9") (pintype "passive"))
    )
    (net (code "40") (name "GND_EXT_1") (class "Default")
      (node (ref "C801") (pin "1") (pinfunction "1_1") (pintype "passive"))
      (node (ref "C802") (pin "1") (pinfunction "1_1") (pintype "passive"))
      (node (ref "C803") (pin "1") (pinfunction "1_1") (pintype "passive"))
      (node (ref "C804") (pin "2") (pinfunction "2_2") (pintype "passive"))
      (node (ref "C805") (pin "1") (pinfunction "1_1") (pintype "passive"))
      (node (ref "C806") (pin "1") (pinfunction "1_1") (pintype "passive"))
      (node (ref "D801") (pin "3") (pinfunction "3_3") (pintype "passive"))
      (node (ref "IC801") (pin "2") (pinfunction "GND_2") (pintype "power_in"))
      (node (ref "IC802") (pin "3") (pinfunction "3_3") (pintype "bidirectional"))
      (node (ref "IC803") (pin "10") (pinfunction "GND_10") (pintype "power_in"))
      (node (ref "IC803") (pin "15") (pinfunction "GND_15") (pintype "power_in"))
      (node (ref "IC803") (pin "9") (pinfunction "GND_9") (pintype "power_in"))
      (node (ref "LSP801") (pin "P$1") (pinfunction "MP_P$1") (pintype "passive"))
      (node (ref "X801") (pin "1") (pinfunction "1_1") (pintype "passive"))
    )
    (net (code "41") (name "GND_EXT_2") (class "Default")
      (node (ref "C1301") (pin "2") (pinfunction "2_2") (pintype "passive"))
      (node (ref "C1302") (pin "2") (pinfunction "2_2") (pintype "passive"))
      (node (ref "C1303") (pin "2") (pinfunction "2_2") (pintype "passive"))
      (node (ref "C1304") (pin "2") (pinfunction "2_2") (pintype "passive"))
      (node (ref "C1305") (pin "2") (pinfunction "2_2") (pintype "passive"))
      (node (ref "IC1301") (pin "2") (pinfunction "COM_2") (pintype "power_in"))
      (node (ref "IC1302") (pin "5") (pinfunction "GND_5") (pintype "power_in"))
      (node (ref "IC1303") (pin "15") (pinfunction "GND2_15") (pintype "power_in"))
      (node (ref "IC1303") (pin "9") (pinfunction "GND2_9") (pintype "power_in"))
      (node (ref "R901") (pin "2") (pinfunction "2_2") (pintype "passive"))
      (node (ref "SV901") (pin "4") (pinfunction "4_4") (pintype "passive"))
      (node (ref "SV901") (pin "6") (pinfunction "6_6") (pintype "passive"))
      (node (ref "SV901") (pin "8") (pinfunction "8_8") (pintype "passive"))
      (node (ref "T901") (pin "3") (pinfunction "S_3") (pintype "passive"))
      (node (ref "X1301") (pin "1") (pinfunction "1_1") (pintype "passive"))
      (node (ref "X1301") (pin "6") (pinfunction "6_6") (pintype "passive"))
    )
    (net (code "42") (name "INTERLOCK_STATUS") (class "Default")
      (node (ref "LSP901") (pin "P$1") (pinfunction "MP_P$1") (pintype "passive"))
      (node (ref "R902") (pin "2") (pinfunction "2_2") (pintype "passive"))
      (node (ref "SV901") (pin "1") (pinfunction "1_1") (pintype "passive"))
    )
    (net (code "43") (name "ISONOC_0_CONTROL") (class "Default")
      (node (ref "JP2202") (pin "16") (pinfunction "16_16") (pintype "passive"))
      (node (ref "LSP2001") (pin "P$1") (pinfunction "MP_P$1") (pintype "passive"))
      (node (ref "R2001") (pin "2") (pinfunction "2_2") (pintype "passive"))
    )
    (net (code "44") (name "ISONOC_0_NEGATIVE") (class "Default")
      (node (ref "D2001") (pin "A") (pinfunction "A_A") (pintype "passive"))
      (node (ref "IC2001") (pin "5") (pinfunction "S_5") (pintype "passive"))
      (node (ref "X2001") (pin "7") (pinfunction "7_7") (pintype "passive"))
    )
    (net (code "45") (name "ISONOC_0_POSITIVE") (class "Default")
      (node (ref "D2001") (pin "C") (pinfunction "C_C") (pintype "passive"))
      (node (ref "IC2001") (pin "4") (pinfunction "D1_4") (pintype "passive"))
      (node (ref "IC2001") (pin "6") (pinfunction "D2_6") (pintype "passive"))
      (node (ref "X2001") (pin "1") (pinfunction "1_1") (pintype "passive"))
    )
    (net (code "46") (name "ISONOC_1_CONTROL") (class "Default")
      (node (ref "JP2202") (pin "17") (pinfunction "17_17") (pintype "passive"))
      (node (ref "LSP2003") (pin "P$1") (pinfunction "MP_P$1") (pintype "passive"))
      (node (ref "R2007") (pin "2") (pinfunction "2_2") (pintype "passive"))
    )
    (net (code "47") (name "ISONOC_1_NEGATIVE") (class "Default")
      (node (ref "D2003") (pin "A") (pinfunction "A_A") (pintype "passive"))
      (node (ref "IC2003") (pin "5") (pinfunction "S_5") (pintype "passive"))
      (node (ref "X2001") (pin "8") (pinfunction "8_8") (pintype "passive"))
    )
    (net (code "48") (name "ISONOC_1_POSITIVE") (class "Default")
      (node (ref "D2003") (pin "C") (pinfunction "C_C") (pintype "passive"))
      (node (ref "IC2003") (pin "4") (pinfunction "D1_4") (pintype "passive"))
      (node (ref "IC2003") (pin "6") (pinfunction "D2_6") (pintype "passive"))
      (node (ref "X2001") (pin "2") (pinfunction "2_2") (pintype "passive"))
    )
    (net (code "49") (name "ISONOC_2_CONTROL") (class "Default")
      (node (ref "JP2202") (pin "18") (pinfunction "18_18") (pintype "passive"))
      (node (ref "LSP2005") (pin "P$1") (pinfunction "MP_P$1") (pintype "passive"))
      (node (ref "R2013") (pin "2") (pinfunction "2_2") (pintype "passive"))
    )
    (net (code "50") (name "ISONOC_2_NEGATIVE") (class "Default")
      (node (ref "D2005") (pin "A") (pinfunction "A_A") (pintype "passive"))
      (node (ref "IC2005") (pin "5") (pinfunction "S_5") (pintype "passive"))
      (node (ref "X2001") (pin "9") (pinfunction "9_9") (pintype "passive"))
    )
    (net (code "51") (name "ISONOC_2_POSITIVE") (class "Default")
      (node (ref "D2005") (pin "C") (pinfunction "C_C") (pintype "passive"))
      (node (ref "IC2005") (pin "4") (pinfunction "D1_4") (pintype "passive"))
      (node (ref "IC2005") (pin "6") (pinfunction "D2_6") (pintype "passive"))
      (node (ref "X2001") (pin "3") (pinfunction "3_3") (pintype "passive"))
    )
    (net (code "52") (name "ISONOC_3_CONTROL") (class "Default")
      (node (ref "JP2202") (pin "19") (pinfunction "19_19") (pintype "passive"))
      (node (ref "LSP2002") (pin "P$1") (pinfunction "MP_P$1") (pintype "passive"))
      (node (ref "R2002") (pin "2") (pinfunction "2_2") (pintype "passive"))
    )
    (net (code "53") (name "ISONOC_3_NEGATIVE") (class "Default")
      (node (ref "D2002") (pin "A") (pinfunction "A_A") (pintype "passive"))
      (node (ref "IC2002") (pin "5") (pinfunction "S_5") (pintype "passive"))
      (node (ref "X2001") (pin "10") (pinfunction "10_10") (pintype "passive"))
    )
    (net (code "54") (name "ISONOC_3_POSITIVE") (class "Default")
      (node (ref "D2002") (pin "C") (pinfunction "C_C") (pintype "passive"))
      (node (ref "IC2002") (pin "4") (pinfunction "D1_4") (pintype "passive"))
      (node (ref "IC2002") (pin "6") (pinfunction "D2_6") (pintype "passive"))
      (node (ref "X2001") (pin "4") (pinfunction "4_4") (pintype "passive"))
    )
    (net (code "55") (name "ISONOC_4_CONTROL") (class "Default")
      (node (ref "JP2202") (pin "20") (pinfunction "20_20") (pintype "passive"))
      (node (ref "LSP2004") (pin "P$1") (pinfunction "MP_P$1") (pintype "passive"))
      (node (ref "R2008") (pin "2") (pinfunction "2_2") (pintype "passive"))
    )
    (net (code "56") (name "ISONOC_4_NEGATIVE") (class "Default")
      (node (ref "D2004") (pin "A") (pinfunction "A_A") (pintype "passive"))
      (node (ref "IC2004") (pin "5") (pinfunction "S_5") (pintype "passive"))
      (node (ref "X2001") (pin "11") (pinfunction "11_11") (pintype "passive"))
    )
    (net (code "57") (name "ISONOC_4_POSITIVE") (class "Default")
      (node (ref "D2004") (pin "C") (pinfunction "C_C") (pintype "passive"))
      (node (ref "IC2004") (pin "4") (pinfunction "D1_4") (pintype "passive"))
      (node (ref "IC2004") (pin "6") (pinfunction "D2_6") (pintype "passive"))
      (node (ref "X2001") (pin "5") (pinfunction "5_5") (pintype "passive"))
    )
    (net (code "58") (name "ISONOC_5_CONTROL") (class "Default")
      (node (ref "JP2202") (pin "21") (pinfunction "21_21") (pintype "passive"))
      (node (ref "LSP2006") (pin "P$1") (pinfunction "MP_P$1") (pintype "passive"))
      (node (ref "R2014") (pin "2") (pinfunction "2_2") (pintype "passive"))
    )
    (net (code "59") (name "ISONOC_5_NEGATIVE") (class "Default")
      (node (ref "D2006") (pin "A") (pinfunction "A_A") (pintype "passive"))
      (node (ref "IC2006") (pin "5") (pinfunction "S_5") (pintype "passive"))
      (node (ref "X2001") (pin "12") (pinfunction "12_12") (pintype "passive"))
    )
    (net (code "60") (name "ISONOC_5_POSITIVE") (class "Default")
      (node (ref "D2006") (pin "C") (pinfunction "C_C") (pintype "passive"))
      (node (ref "IC2006") (pin "4") (pinfunction "D1_4") (pintype "passive"))
      (node (ref "IC2006") (pin "6") (pinfunction "D2_6") (pintype "passive"))
      (node (ref "X2001") (pin "6") (pinfunction "6_6") (pintype "passive"))
    )
    (net (code "61") (name "ISO_GPIO_MCU_0_IN_0") (class "Default")
      (node (ref "IC1902") (pin "14") (pinfunction "VOA_14") (pintype "bidirectional"))
      (node (ref "JP2202") (pin "22") (pinfunction "22_22") (pintype "passive"))
      (node (ref "LSP1903") (pin "P$1") (pinfunction "MP_P$1") (pintype "passive"))
    )
    (net (code "62") (name "ISO_GPIO_MCU_0_IN_0_EXT") (class "Default")
      (node (ref "R1901") (pin "2") (pinfunction "2_2") (pintype "passive"))
      (node (ref "X1901") (pin "5") (pinfunction "5_5") (pintype "passive"))
    )
    (net (code "63") (name "ISO_GPIO_MCU_0_IN_1") (class "Default")
      (node (ref "IC1902") (pin "13") (pinfunction "VOB_13") (pintype "bidirectional"))
      (node (ref "JP2202") (pin "23") (pinfunction "23_23") (pintype "passive"))
      (node (ref "LSP1901") (pin "P$1") (pinfunction "MP_P$1") (pintype "passive"))
    )
    (net (code "64") (name "ISO_GPIO_MCU_0_IN_1_EXT") (class "Default")
      (node (ref "R1902") (pin "2") (pinfunction "2_2") (pintype "passive"))
      (node (ref "X1901") (pin "6") (pinfunction "6_6") (pintype "passive"))
    )
    (net (code "65") (name "ISO_GPIO_MCU_0_IN_2") (class "Default")
      (node (ref "IC1903") (pin "14") (pinfunction "VOA_14") (pintype "bidirectional"))
      (node (ref "JP2201") (pin "13") (pinfunction "13_13") (pintype "passive"))
      (node (ref "LSP1905") (pin "P$1") (pinfunction "MP_P$1") (pintype "passive"))
    )
    (net (code "66") (name "ISO_GPIO_MCU_0_IN_2_EXT") (class "Default")
      (node (ref "R1905") (pin "2") (pinfunction "2_2") (pintype "passive"))
      (node (ref "X1901") (pin "7") (pinfunction "7_7") (pintype "passive"))
    )
    (net (code "67") (name "ISO_GPIO_MCU_0_IN_3") (class "Default")
      (node (ref "IC1903") (pin "13") (pinfunction "VOB_13") (pintype "bidirectional"))
      (node (ref "JP2201") (pin "10") (pinfunction "10_10") (pintype "passive"))
      (node (ref "LSP1907") (pin "P$1") (pinfunction "MP_P$1") (pintype "passive"))
    )
    (net (code "68") (name "ISO_GPIO_MCU_0_IN_3_EXT") (class "Default")
      (node (ref "R1906") (pin "2") (pinfunction "2_2") (pintype "passive"))
      (node (ref "X1901") (pin "8") (pinfunction "8_8") (pintype "passive"))
    )
    (net (code "69") (name "ISO_GPIO_MCU_0_OUT_0") (class "Default")
      (node (ref "IC1902") (pin "12") (pinfunction "VIC_12") (pintype "bidirectional"))
      (node (ref "JP2201") (pin "9") (pinfunction "9_9") (pintype "passive"))
      (node (ref "LSP1904") (pin "P$1") (pinfunction "MP_P$1") (pintype "passive"))
    )
    (net (code "70") (name "ISO_GPIO_MCU_0_OUT_0_EXT") (class "Default")
      (node (ref "IC1902") (pin "5") (pinfunction "VOC_5") (pintype "bidirectional"))
      (node (ref "R1903") (pin "2") (pinfunction "2_2") (pintype "passive"))
      (node (ref "X1901") (pin "1") (pinfunction "1_1") (pintype "passive"))
    )
    (net (code "71") (name "ISO_GPIO_MCU_0_OUT_1") (class "Default")
      (node (ref "IC1902") (pin "11") (pinfunction "VID_11") (pintype "bidirectional"))
      (node (ref "JP2201") (pin "14") (pinfunction "14_14") (pintype "passive"))
      (node (ref "LSP1902") (pin "P$1") (pinfunction "MP_P$1") (pintype "passive"))
    )
    (net (code "72") (name "ISO_GPIO_MCU_0_OUT_1_EXT") (class "Default")
      (node (ref "IC1902") (pin "6") (pinfunction "VOD_6") (pintype "bidirectional"))
      (node (ref "R1904") (pin "2") (pinfunction "2_2") (pintype "passive"))
      (node (ref "X1901") (pin "2") (pinfunction "2_2") (pintype "passive"))
    )
    (net (code "73") (name "ISO_GPIO_MCU_0_OUT_2") (class "Default")
      (node (ref "IC1903") (pin "12") (pinfunction "VIC_12") (pintype "bidirectional"))
      (node (ref "JP2201") (pin "11") (pinfunction "11_11") (pintype "passive"))
      (node (ref "LSP1906") (pin "P$1") (pinfunction "MP_P$1") (pintype "passive"))
    )
    (net (code "74") (name "ISO_GPIO_MCU_0_OUT_2_EXT") (class "Default")
      (node (ref "IC1903") (pin "5") (pinfunction "VOC_5") (pintype "bidirectional"))
      (node (ref "R1907") (pin "2") (pinfunction "2_2") (pintype "passive"))
      (node (ref "X1901") (pin "3") (pinfunction "3_3") (pintype "passive"))
    )
    (net (code "75") (name "ISO_GPIO_MCU_0_OUT_3") (class "Default")
      (node (ref "IC1903") (pin "11") (pinfunction "VID_11") (pintype "bidirectional"))
      (node (ref "JP2201") (pin "12") (pinfunction "12_12") (pintype "passive"))
      (node (ref "LSP1908") (pin "P$1") (pinfunction "MP_P$1") (pintype "passive"))
    )
    (net (code "76") (name "ISO_GPIO_MCU_0_OUT_3_EXT") (class "Default")
      (node (ref "IC1903") (pin "6") (pinfunction "VOD_6") (pintype "bidirectional"))
      (node (ref "R1908") (pin "2") (pinfunction "2_2") (pintype "passive"))
      (node (ref "X1901") (pin "4") (pinfunction "4_4") (pintype "passive"))
    )
    (net (code "77") (name "ISO_GPIO_SUPPLY") (class "Default")
      (node (ref "C1903") (pin "1") (pinfunction "1_1") (pintype "passive"))
      (node (ref "C1904") (pin "1") (pinfunction "1_1") (pintype "passive"))
      (node (ref "C1906") (pin "1") (pinfunction "1_1") (pintype "passive"))
      (node (ref "IC1901") (pin "1") (pinfunction "OUT_1") (pintype "output"))
      (node (ref "IC1902") (pin "1") (pinfunction "VDD1_1") (pintype "power_in"))
      (node (ref "IC1902") (pin "7") (pinfunction "VE1_7") (pintype "bidirectional"))
      (node (ref "IC1903") (pin "1") (pinfunction "VDD1_1") (pintype "power_in"))
      (node (ref "IC1903") (pin "7") (pinfunction "VE1_7") (pintype "bidirectional"))
    )
    (net (code "78") (name "MCU_TO_FPGA_INTERFACE_MCU_0_CS") (class "Default")
      (node (ref "SV2101") (pin "8") (pinfunction "8_8") (pintype "passive"))
    )
    (net (code "79") (name "MCU_TO_FPGA_INTERFACE_MCU_0_MISO") (class "Default")
      (node (ref "SV2101") (pin "3") (pinfunction "3_3") (pintype "passive"))
    )
    (net (code "80") (name "MCU_TO_FPGA_INTERFACE_MCU_0_MOSI") (class "Default")
      (node (ref "SV2101") (pin "7") (pinfunction "7_7") (pintype "passive"))
    )
    (net (code "81") (name "MCU_TO_FPGA_INTERFACE_MCU_0_SCK") (class "Default")
      (node (ref "SV2101") (pin "4") (pinfunction "4_4") (pintype "passive"))
    )
    (net (code "82") (name "Net-(C804-Pad1)") (class "Default")
      (node (ref "C804") (pin "1") (pinfunction "1_1") (pintype "passive"))
      (node (ref "R801") (pin "2") (pinfunction "2_2") (pintype "passive"))
      (node (ref "R802") (pin "1") (pinfunction "1_1") (pintype "passive"))
    )
    (net (code "83") (name "Net-(F1001-Pad1)") (class "Default")
      (node (ref "F1001") (pin "1") (pinfunction "1_1") (pintype "bidirectional"))
      (node (ref "IC1001") (pin "4") (pinfunction "4_4") (pintype "bidirectional"))
      (node (ref "IC1001") (pin "6") (pinfunction "6_6") (pintype "bidirectional"))
    )
    (net (code "84") (name "Net-(F1002-Pad1)") (class "Default")
      (node (ref "F1002") (pin "1") (pinfunction "1_1") (pintype "bidirectional"))
      (node (ref "IC1002") (pin "4") (pinfunction "4_4") (pintype "bidirectional"))
      (node (ref "IC1002") (pin "6") (pinfunction "6_6") (pintype "bidirectional"))
    )
    (net (code "85") (name "Net-(F1003-Pad1)") (class "Default")
      (node (ref "F1003") (pin "1") (pinfunction "1_1") (pintype "bidirectional"))
      (node (ref "IC1003") (pin "4") (pinfunction "4_4") (pintype "bidirectional"))
      (node (ref "IC1003") (pin "6") (pinfunction "6_6") (pintype "bidirectional"))
    )
    (net (code "86") (name "Net-(IC802-CON+)") (class "Default")
      (node (ref "IC802") (pin "1") (pinfunction "CON+_1") (pintype "bidirectional"))
      (node (ref "R804") (pin "2") (pinfunction "2_2") (pintype "passive"))
    )
    (net (code "87") (name "Net-(IC802-CON-)") (class "Default")
      (node (ref "IC802") (pin "2") (pinfunction "CON-_2") (pintype "bidirectional"))
      (node (ref "T801") (pin "3") (pinfunction "D_3") (pintype "passive"))
    )
    (net (code "88") (name "Net-(IC803A-CANH)") (class "Default")
      (node (ref "IC803") (pin "13") (pinfunction "CANH_13") (pintype "bidirectional"))
      (node (ref "L801") (pin "3") (pinfunction "3_3") (pintype "passive"))
      (node (ref "R802") (pin "2") (pinfunction "2_2") (pintype "passive"))
    )
    (net (code "89") (name "Net-(IC803A-CANL)") (class "Default")
      (node (ref "IC803") (pin "12") (pinfunction "CANL_12") (pintype "bidirectional"))
      (node (ref "L801") (pin "4") (pinfunction "4_4") (pintype "passive"))
      (node (ref "R801") (pin "1") (pinfunction "1_1") (pintype "passive"))
    )
    (net (code "90") (name "Net-(IC1001-Pad2)") (class "Default")
      (node (ref "IC1001") (pin "2") (pinfunction "2_2") (pintype "bidirectional"))
      (node (ref "R1003") (pin "2") (pinfunction "2_2") (pintype "passive"))
    )
    (net (code "91") (name "Net-(IC1002-Pad2)") (class "Default")
      (node (ref "IC1002") (pin "2") (pinfunction "2_2") (pintype "bidirectional"))
      (node (ref "R1006") (pin "2") (pinfunction "2_2") (pintype "passive"))
    )
    (net (code "92") (name "Net-(IC1003-Pad2)") (class "Default")
      (node (ref "IC1003") (pin "2") (pinfunction "2_2") (pintype "bidirectional"))
      (node (ref "R1009") (pin "2") (pinfunction "2_2") (pintype "passive"))
    )
    (net (code "93") (name "Net-(IC1102A-VIA)") (class "Default")
      (node (ref "D1101") (pin "C") (pinfunction "C_C") (pintype "passive"))
      (node (ref "IC1102") (pin "3") (pinfunction "VIA_3") (pintype "bidirectional"))
      (node (ref "R1101") (pin "1") (pinfunction "1_1") (pintype "passive"))
      (node (ref "R1104") (pin "1") (pinfunction "1_1") (pintype "passive"))
    )
    (net (code "94") (name "Net-(IC1102A-VIB)") (class "Default")
      (node (ref "D1102") (pin "C") (pinfunction "C_C") (pintype "passive"))
      (node (ref "IC1102") (pin "4") (pinfunction "VIB_4") (pintype "bidirectional"))
      (node (ref "R1102") (pin "1") (pinfunction "1_1") (pintype "passive"))
      (node (ref "R1105") (pin "1") (pinfunction "1_1") (pintype "passive"))
    )
    (net (code "95") (name "Net-(IC1102A-VIC)") (class "Default")
      (node (ref "D1103") (pin "C") (pinfunction "C_C") (pintype "passive"))
      (node (ref "IC1102") (pin "5") (pinfunction "VIC_5") (pintype "bidirectional"))
      (node (ref "R1103") (pin "1") (pinfunction "1_1") (pintype "passive"))
      (node (ref "R1106") (pin "1") (pinfunction "1_1") (pintype "passive"))
    )
    (net (code "96") (name "Net-(IC1301-IN)") (class "Default")
      (node (ref "C1301") (pin "1") (pinfunction "1_1") (pintype "passive"))
      (node (ref "C1302") (pin "1") (pinfunction "1_1") (pintype "passive"))
      (node (ref "IC1301") (pin "3") (pinfunction "IN_3") (pintype "input"))
      (node (ref "X1301") (pin "4") (pinfunction "4_4") (pintype "passive"))
      (node (ref "X1301") (pin "5") (pinfunction "5_5") (pintype "passive"))
    )
    (net (code "97") (name "Net-(IC1301-OUT)") (class "Default")
      (node (ref "C1303") (pin "1") (pinfunction "1_1") (pintype "passive"))
      (node (ref "C1304") (pin "1") (pinfunction "1_1") (pintype "passive"))
      (node (ref "C1305") (pin "1") (pinfunction "1_1") (pintype "passive"))
      (node (ref "IC1301") (pin "1") (pinfunction "OUT_1") (pintype "output"))
      (node (ref "IC1302") (pin "8") (pinfunction "VCC_8") (pintype "power_in"))
      (node (ref "IC1303") (pin "10") (pinfunction "VE2_10") (pintype "bidirectional"))
      (node (ref "IC1303") (pin "16") (pinfunction "VDD2_16") (pintype "power_in"))
    )
    (net (code "98") (name "Net-(IC1302A-DE)") (class "Default")
      (node (ref "IC1302") (pin "3") (pinfunction "DE_3") (pintype "bidirectional"))
      (node (ref "IC1303") (pin "12") (pinfunction "VOC_12") (pintype "bidirectional"))
    )
    (net (code "99") (name "Net-(IC1302A-DI)") (class "Default")
      (node (ref "IC1302") (pin "4") (pinfunction "DI_4") (pintype "bidirectional"))
      (node (ref "IC1303") (pin "14") (pinfunction "VOA_14") (pintype "bidirectional"))
    )
    (net (code "100") (name "Net-(IC1302A-RO)") (class "Default")
      (node (ref "IC1302") (pin "1") (pinfunction "RO_1") (pintype "bidirectional"))
      (node (ref "IC1303") (pin "11") (pinfunction "VID_11") (pintype "bidirectional"))
    )
    (net (code "101") (name "Net-(IC1302A-~{RE})") (class "Default")
      (node (ref "IC1302") (pin "2") (pinfunction "~{RE}_2") (pintype "bidirectional"))
      (node (ref "IC1303") (pin "13") (pinfunction "VOB_13") (pintype "bidirectional"))
    )
    (net (code "102") (name "Net-(IC1701-VOUT_FORCE)") (class "Default")
      (node (ref "C1707") (pin "1") (pinfunction "1_1") (pintype "passive"))
      (node (ref "IC1701") (pin "5") (pinfunction "VOUT_SENSE_5") (pintype "output"))
      (node (ref "IC1701") (pin "6") (pinfunction "VOUT_FORCE_6") (pintype "output"))
      (node (ref "X1701") (pin "1") (pinfunction "1_1") (pintype "passive"))
      (node (ref "X1701") (pin "3") (pinfunction "3_3") (pintype "passive"))
      (node (ref "X1701") (pin "5") (pinfunction "5_5") (pintype "passive"))
      (node (ref "X1701") (pin "7") (pinfunction "7_7") (pintype "passive"))
      (node (ref "X1701") (pin "9") (pinfunction "9_9") (pintype "passive"))
    )
    (net (code "103") (name "Net-(IC1902A-VIA)") (class "Default")
      (node (ref "D1901") (pin "C") (pinfunction "C_C") (pintype "passive"))
      (node (ref "IC1902") (pin "3") (pinfunction "VIA_3") (pintype "bidirectional"))
      (node (ref "R1901") (pin "1") (pinfunction "1_1") (pintype "passive"))
    )
    (net (code "104") (name "Net-(IC1902A-VIB)") (class "Default")
      (node (ref "D1902") (pin "C") (pinfunction "C_C") (pintype "passive"))
      (node (ref "IC1902") (pin "4") (pinfunction "VIB_4") (pintype "bidirectional"))
      (node (ref "R1902") (pin "1") (pinfunction "1_1") (pintype "passive"))
    )
    (net (code "105") (name "Net-(IC1903A-VIA)") (class "Default")
      (node (ref "D1903") (pin "C") (pinfunction "C_C") (pintype "passive"))
      (node (ref "IC1903") (pin "3") (pinfunction "VIA_3") (pintype "bidirectional"))
      (node (ref "R1905") (pin "1") (pinfunction "1_1") (pintype "passive"))
    )
    (net (code "106") (name "Net-(IC1903A-VIB)") (class "Default")
      (node (ref "D1904") (pin "C") (pinfunction "C_C") (pintype "passive"))
      (node (ref "IC1903") (pin "4") (pinfunction "VIB_4") (pintype "bidirectional"))
      (node (ref "R1906") (pin "1") (pinfunction "1_1") (pintype "passive"))
    )
    (net (code "107") (name "Net-(IC2001-K)") (class "Default")
      (node (ref "IC2001") (pin "2") (pinfunction "K_2") (pintype "passive"))
      (node (ref "R2005") (pin "2") (pinfunction "2_2") (pintype "passive"))
    )
    (net (code "108") (name "Net-(IC2002-K)") (class "Default")
      (node (ref "IC2002") (pin "2") (pinfunction "K_2") (pintype "passive"))
      (node (ref "R2006") (pin "2") (pinfunction "2_2") (pintype "passive"))
    )
    (net (code "109") (name "Net-(IC2003-K)") (class "Default")
      (node (ref "IC2003") (pin "2") (pinfunction "K_2") (pintype "passive"))
      (node (ref "R2011") (pin "2") (pinfunction "2_2") (pintype "passive"))
    )
    (net (code "110") (name "Net-(IC2004-K)") (class "Default")
      (node (ref "IC2004") (pin "2") (pinfunction "K_2") (pintype "passive"))
      (node (ref "R2012") (pin "2") (pinfunction "2_2") (pintype "passive"))
    )
    (net (code "111") (name "Net-(IC2005-K)") (class "Default")
      (node (ref "IC2005") (pin "2") (pinfunction "K_2") (pintype "passive"))
      (node (ref "R2017") (pin "2") (pinfunction "2_2") (pintype "passive"))
    )
    (net (code "112") (name "Net-(IC2006-K)") (class "Default")
      (node (ref "IC2006") (pin "2") (pinfunction "K_2") (pintype "passive"))
      (node (ref "R2018") (pin "2") (pinfunction "2_2") (pintype "passive"))
    )
    (net (code "113") (name "Net-(LSP807-MP)") (class "Default")
      (node (ref "LSP807") (pin "P$1") (pinfunction "MP_P$1") (pintype "passive"))
      (node (ref "R805") (pin "1") (pinfunction "1_1") (pintype "passive"))
      (node (ref "R806") (pin "1") (pinfunction "1_1") (pintype "passive"))
      (node (ref "T801") (pin "1") (pinfunction "G_1") (pintype "passive"))
    )
    (net (code "114") (name "Net-(R1502-Pad1)") (class "Default")
      (node (ref "R1502") (pin "1") (pinfunction "1_1") (pintype "passive"))
      (node (ref "SLOT1501") (pin "1") (pinfunction "1_1") (pintype "passive"))
    )
    (net (code "115") (name "Net-(R1503-Pad1)") (class "Default")
      (node (ref "R1503") (pin "1") (pinfunction "1_1") (pintype "passive"))
      (node (ref "SLOT1501") (pin "8") (pinfunction "8_8") (pintype "passive"))
    )
    (net (code "116") (name "Net-(T901-G)") (class "Default")
      (node (ref "R901") (pin "1") (pinfunction "1_1") (pintype "passive"))
      (node (ref "R902") (pin "1") (pinfunction "1_1") (pintype "passive"))
      (node (ref "T901") (pin "1") (pinfunction "G_1") (pintype "passive"))
    )
    (net (code "117") (name "Net-(T1001-D)") (class "Default")
      (node (ref "R1003") (pin "1") (pinfunction "1_1") (pintype "passive"))
      (node (ref "T1001") (pin "3") (pinfunction "D_3") (pintype "passive"))
    )
    (net (code "118") (name "Net-(T1001-G)") (class "Default")
      (node (ref "R1001") (pin "1") (pinfunction "1_1") (pintype "passive"))
      (node (ref "R1002") (pin "2") (pinfunction "2_2") (pintype "passive"))
      (node (ref "T1001") (pin "1") (pinfunction "G_1") (pintype "passive"))
    )
    (net (code "119") (name "Net-(T1002-D)") (class "Default")
      (node (ref "R1006") (pin "1") (pinfunction "1_1") (pintype "passive"))
      (node (ref "T1002") (pin "3") (pinfunction "D_3") (pintype "passive"))
    )
    (net (code "120") (name "Net-(T1002-G)") (class "Default")
      (node (ref "R1004") (pin "1") (pinfunction "1_1") (pintype "passive"))
      (node (ref "R1005") (pin "2") (pinfunction "2_2") (pintype "passive"))
      (node (ref "T1002") (pin "1") (pinfunction "G_1") (pintype "passive"))
    )
    (net (code "121") (name "Net-(T1003-D)") (class "Default")
      (node (ref "R1009") (pin "1") (pinfunction "1_1") (pintype "passive"))
      (node (ref "T1003") (pin "3") (pinfunction "D_3") (pintype "passive"))
    )
    (net (code "122") (name "Net-(T1003-G)") (class "Default")
      (node (ref "R1007") (pin "1") (pinfunction "1_1") (pintype "passive"))
      (node (ref "R1008") (pin "2") (pinfunction "2_2") (pintype "passive"))
      (node (ref "T1003") (pin "1") (pinfunction "G_1") (pintype "passive"))
    )
    (net (code "123") (name "Net-(T1501-D)") (class "Default")
      (node (ref "L1501") (pin "2") (pinfunction "2_2") (pintype "passive"))
      (node (ref "T1501") (pin "3") (pinfunction "D_3") (pintype "passive"))
    )
    (net (code "124") (name "Net-(T2001-D)") (class "Default")
      (node (ref "R2005") (pin "1") (pinfunction "1_1") (pintype "passive"))
      (node (ref "T2001") (pin "3") (pinfunction "D_3") (pintype "passive"))
    )
    (net (code "125") (name "Net-(T2001-G)") (class "Default")
      (node (ref "R2001") (pin "1") (pinfunction "1_1") (pintype "passive"))
      (node (ref "R2003") (pin "2") (pinfunction "2_2") (pintype "passive"))
      (node (ref "T2001") (pin "1") (pinfunction "G_1") (pintype "passive"))
    )
    (net (code "126") (name "Net-(T2002-D)") (class "Default")
      (node (ref "R2006") (pin "1") (pinfunction "1_1") (pintype "passive"))
      (node (ref "T2002") (pin "3") (pinfunction "D_3") (pintype "passive"))
    )
    (net (code "127") (name "Net-(T2002-G)") (class "Default")
      (node (ref "R2002") (pin "1") (pinfunction "1_1") (pintype "passive"))
      (node (ref "R2004") (pin "2") (pinfunction "2_2") (pintype "passive"))
      (node (ref "T2002") (pin "1") (pinfunction "G_1") (pintype "passive"))
    )
    (net (code "128") (name "Net-(T2003-D)") (class "Default")
      (node (ref "R2011") (pin "1") (pinfunction "1_1") (pintype "passive"))
      (node (ref "T2003") (pin "3") (pinfunction "D_3") (pintype "passive"))
    )
    (net (code "129") (name "Net-(T2003-G)") (class "Default")
      (node (ref "R2007") (pin "1") (pinfunction "1_1") (pintype "passive"))
      (node (ref "R2009") (pin "2") (pinfunction "2_2") (pintype "passive"))
      (node (ref "T2003") (pin "1") (pinfunction "G_1") (pintype "passive"))
    )
    (net (code "130") (name "Net-(T2004-D)") (class "Default")
      (node (ref "R2012") (pin "1") (pinfunction "1_1") (pintype "passive"))
      (node (ref "T2004") (pin "3") (pinfunction "D_3") (pintype "passive"))
    )
    (net (code "131") (name "Net-(T2004-G)") (class "Default")
      (node (ref "R2008") (pin "1") (pinfunction "1_1") (pintype "passive"))
      (node (ref "R2010") (pin "2") (pinfunction "2_2") (pintype "passive"))
      (node (ref "T2004") (pin "1") (pinfunction "G_1") (pintype "passive"))
    )
    (net (code "132") (name "Net-(T2005-D)") (class "Default")
      (node (ref "R2017") (pin "1") (pinfunction "1_1") (pintype "passive"))
      (node (ref "T2005") (pin "3") (pinfunction "D_3") (pintype "passive"))
    )
    (net (code "133") (name "Net-(T2005-G)") (class "Default")
      (node (ref "R2013") (pin "1") (pinfunction "1_1") (pintype "passive"))
      (node (ref "R2015") (pin "2") (pinfunction "2_2") (pintype "passive"))
      (node (ref "T2005") (pin "1") (pinfunction "G_1") (pintype "passive"))
    )
    (net (code "134") (name "Net-(T2006-D)") (class "Default")
      (node (ref "R2018") (pin "1") (pinfunction "1_1") (pintype "passive"))
      (node (ref "T2006") (pin "3") (pinfunction "D_3") (pintype "passive"))
    )
    (net (code "135") (name "Net-(T2006-G)") (class "Default")
      (node (ref "R2014") (pin "1") (pinfunction "1_1") (pintype "passive"))
      (node (ref "R2016") (pin "2") (pinfunction "2_2") (pintype "passive"))
      (node (ref "T2006") (pin "1") (pinfunction "G_1") (pintype "passive"))
    )
    (net (code "136") (name "RS485_A_EXT") (class "Default")
      (node (ref "IC1302") (pin "6") (pinfunction "A_6") (pintype "bidirectional"))
      (node (ref "X1301") (pin "3") (pinfunction "3_3") (pintype "passive"))
    )
    (net (code "137") (name "RS485_B_EXT") (class "Default")
      (node (ref "IC1302") (pin "7") (pinfunction "B_7") (pintype "bidirectional"))
      (node (ref "X1301") (pin "2") (pinfunction "2_2") (pintype "passive"))
    )
    (net (code "138") (name "RS485_MCU_0_DE") (class "Default")
      (node (ref "IC1303") (pin "5") (pinfunction "VIC_5") (pintype "bidirectional"))
      (node (ref "JP2202") (pin "15") (pinfunction "15_15") (pintype "passive"))
      (node (ref "LSP1302") (pin "P$1") (pinfunction "MP_P$1") (pintype "passive"))
    )
    (net (code "139") (name "RS485_MCU_0_NRE") (class "Default")
      (node (ref "IC1303") (pin "4") (pinfunction "VIB_4") (pintype "bidirectional"))
      (node (ref "JP2202") (pin "14") (pinfunction "14_14") (pintype "passive"))
      (node (ref "LSP1303") (pin "P$1") (pinfunction "MP_P$1") (pintype "passive"))
    )
    (net (code "140") (name "RS485_MCU_0_RX") (class "Default")
      (node (ref "IC1303") (pin "6") (pinfunction "VOD_6") (pintype "bidirectional"))
      (node (ref "JP2202") (pin "13") (pinfunction "13_13") (pintype "passive"))
      (node (ref "LSP1304") (pin "P$1") (pinfunction "MP_P$1") (pintype "passive"))
    )
    (net (code "141") (name "RS485_MCU_0_TX") (class "Default")
      (node (ref "IC1303") (pin "3") (pinfunction "VIA_3") (pintype "bidirectional"))
      (node (ref "JP2202") (pin "12") (pinfunction "12_12") (pintype "passive"))
      (node (ref "LSP1301") (pin "P$1") (pinfunction "MP_P$1") (pintype "passive"))
    )
    (net (code "142") (name "SDCARD_SUPPLY") (class "Default")
      (node (ref "C1501") (pin "2") (pinfunction "2_2") (pintype "passive"))
      (node (ref "C1502") (pin "1") (pinfunction "1_1") (pintype "passive"))
      (node (ref "L1501") (pin "1") (pinfunction "1_1") (pintype "passive"))
      (node (ref "R1502") (pin "2") (pinfunction "2_2") (pintype "passive"))
      (node (ref "R1503") (pin "2") (pinfunction "2_2") (pintype "passive"))
      (node (ref "R1504") (pin "2") (pinfunction "2_2") (pintype "passive"))
      (node (ref "R1506") (pin "2") (pinfunction "2_2") (pintype "passive"))
      (node (ref "R1507") (pin "2") (pinfunction "2_2") (pintype "passive"))
      (node (ref "SLOT1501") (pin "4") (pinfunction "4_4") (pintype "passive"))
    )
    (net (code "143") (name "SDCARD_SUPPLY_CONTROL") (class "Default")
      (node (ref "JP2201") (pin "22") (pinfunction "22_22") (pintype "passive"))
      (node (ref "LSP1501") (pin "P$1") (pinfunction "MP_P$1") (pintype "passive"))
      (node (ref "R1501") (pin "1") (pinfunction "1_1") (pintype "passive"))
      (node (ref "T1501") (pin "1") (pinfunction "G_1") (pintype "passive"))
    )
    (net (code "144") (name "SUPPLY_EXT_0") (class "Default")
      (node (ref "C1101") (pin "1") (pinfunction "1_1") (pintype "passive"))
      (node (ref "C1102") (pin "1") (pinfunction "1_1") (pintype "passive"))
      (node (ref "C1901") (pin "1") (pinfunction "1_1") (pintype "passive"))
      (node (ref "C1902") (pin "1") (pinfunction "1_1") (pintype "passive"))
      (node (ref "IC1101") (pin "3") (pinfunction "IN_3") (pintype "input"))
      (node (ref "IC1901") (pin "3") (pinfunction "IN_3") (pintype "input"))
      (node (ref "SV901") (pin "3") (pinfunction "3_3") (pintype "passive"))
    )
    (net (code "145") (name "SUPPLY_EXT_1") (class "Default")
      (node (ref "C801") (pin "2") (pinfunction "2_2") (pintype "passive"))
      (node (ref "C802") (pin "2") (pinfunction "2_2") (pintype "passive"))
      (node (ref "IC801") (pin "1") (pinfunction "IN_1") (pintype "input"))
      (node (ref "X801") (pin "2") (pinfunction "2_2") (pintype "passive"))
    )
    (net (code "146") (name "SUPPLY_EXT_2") (class "Default")
      (node (ref "F1001") (pin "2") (pinfunction "2_2") (pintype "bidirectional"))
      (node (ref "F1002") (pin "2") (pinfunction "2_2") (pintype "bidirectional"))
      (node (ref "F1003") (pin "2") (pinfunction "2_2") (pintype "bidirectional"))
      (node (ref "SV901") (pin "5") (pinfunction "5_5") (pintype "passive"))
      (node (ref "SV901") (pin "7") (pinfunction "7_7") (pintype "passive"))
    )
    (net (code "147") (name "unconnected-(JP2201-Pad8)") (class "Default")
      (node (ref "JP2201") (pin "8") (pinfunction "8_8") (pintype "passive"))
    )
    (net (code "148") (name "unconnected-(JP2201-Pad24)") (class "Default")
      (node (ref "JP2201") (pin "24") (pinfunction "24_24") (pintype "passive"))
    )
    (net (code "149") (name "unconnected-(JP2202-Pad24)") (class "Default")
      (node (ref "JP2202") (pin "24") (pinfunction "24_24") (pintype "passive"))
    )
  )
)
